# display_array.net
KiCad netlist of a schematic drawn in EAGLE
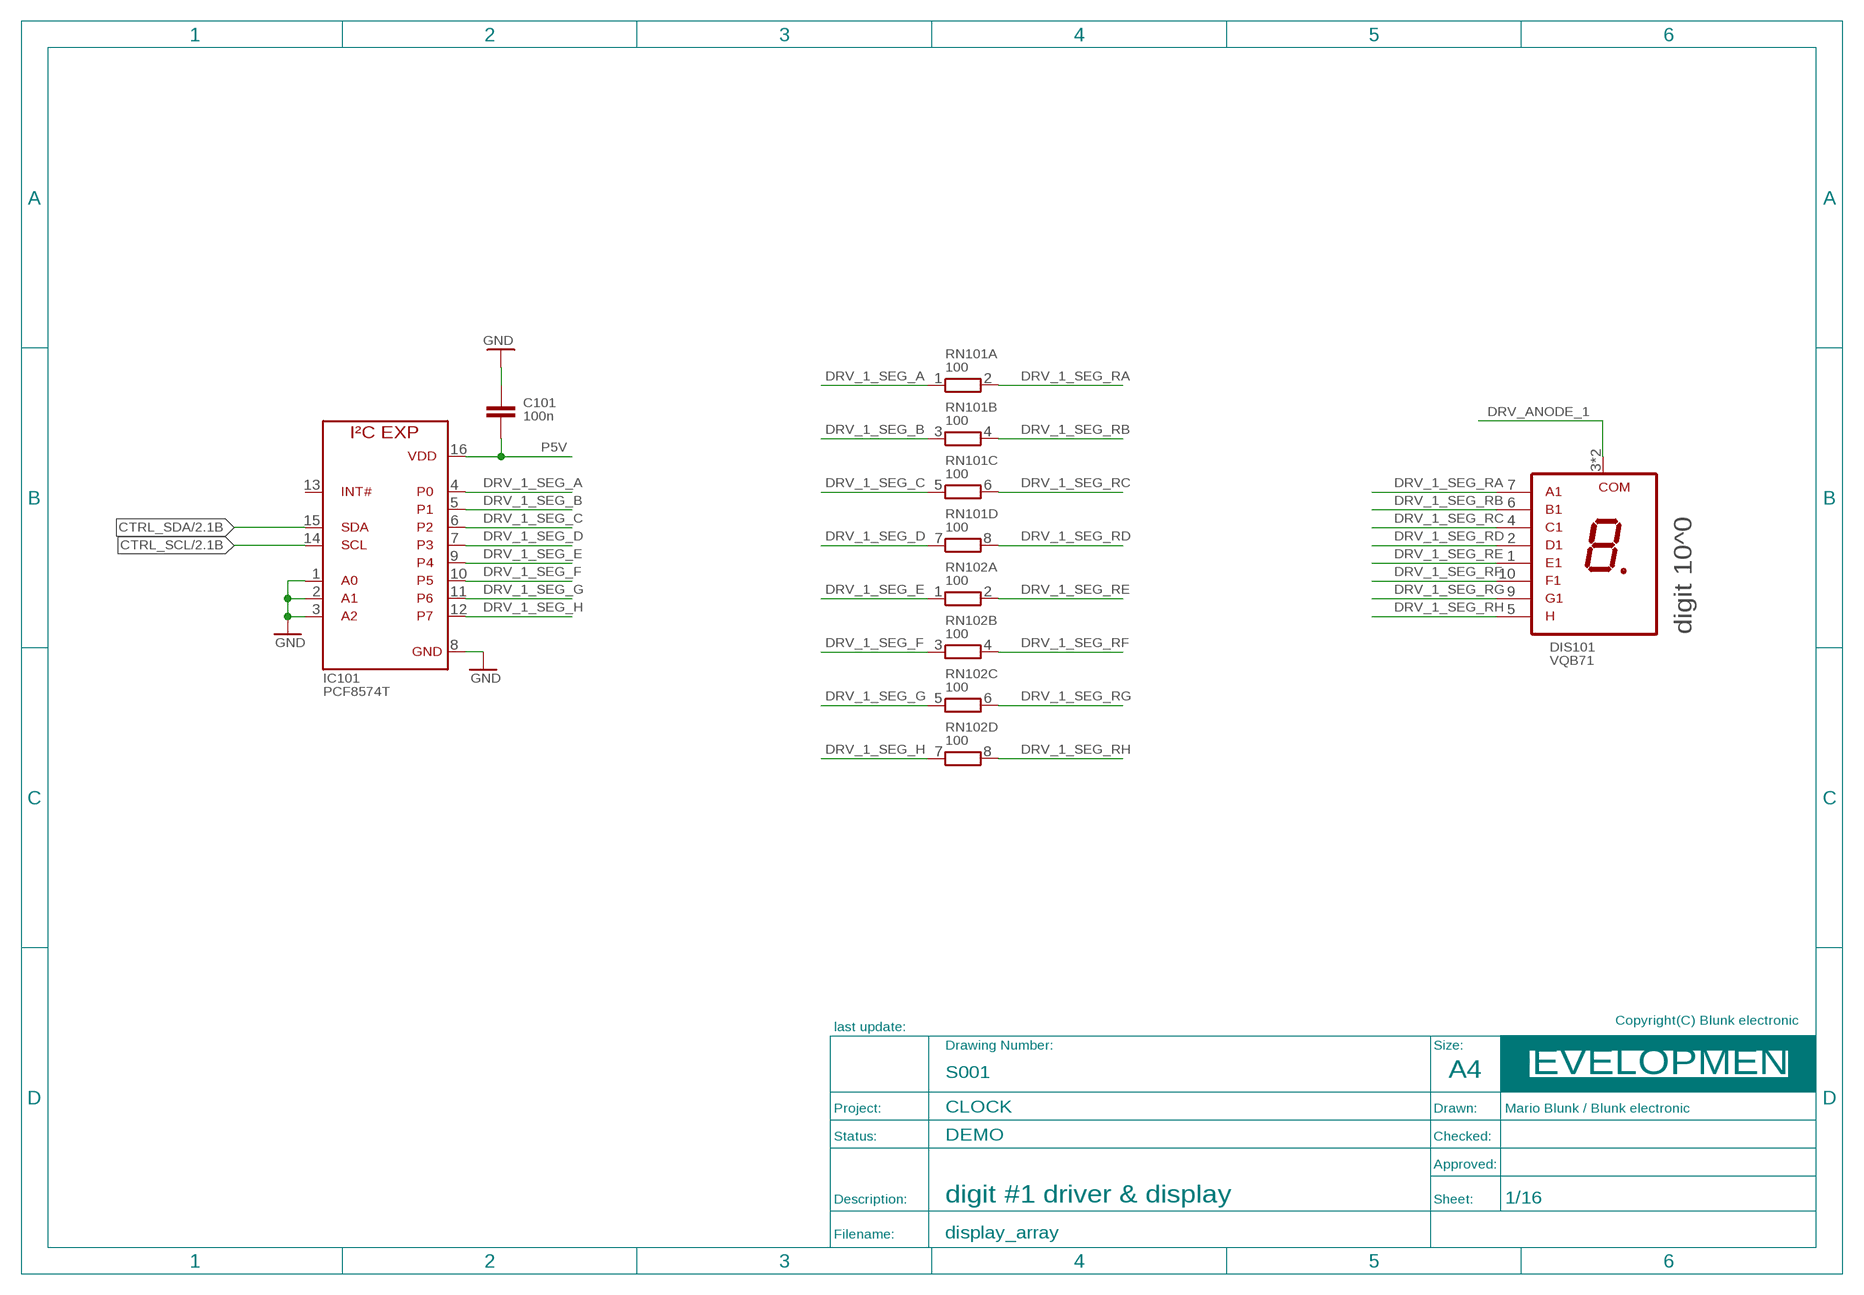
[diagram p0: schematic, sheet 1]
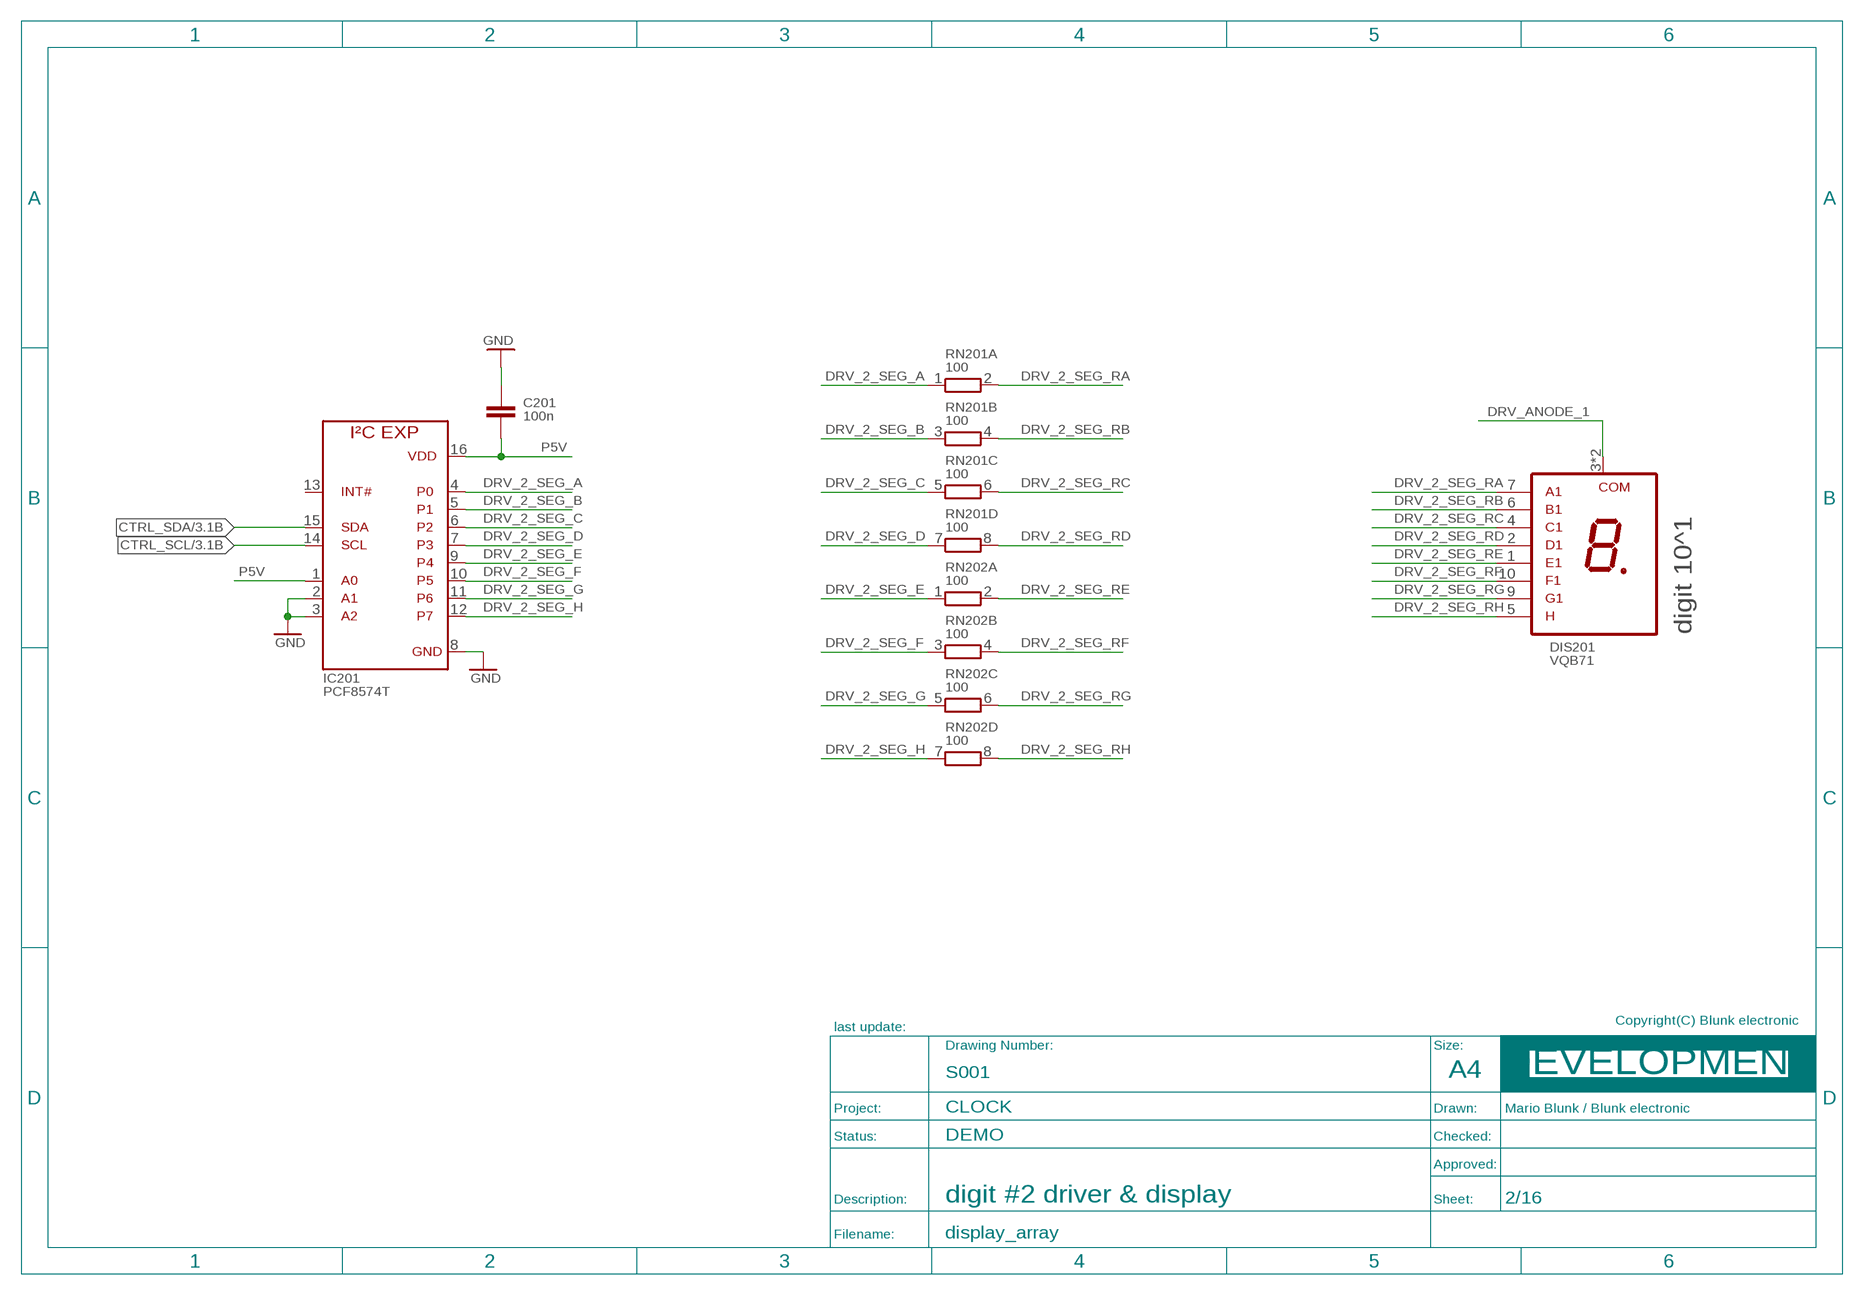
[diagram p1: schematic, sheet 2]
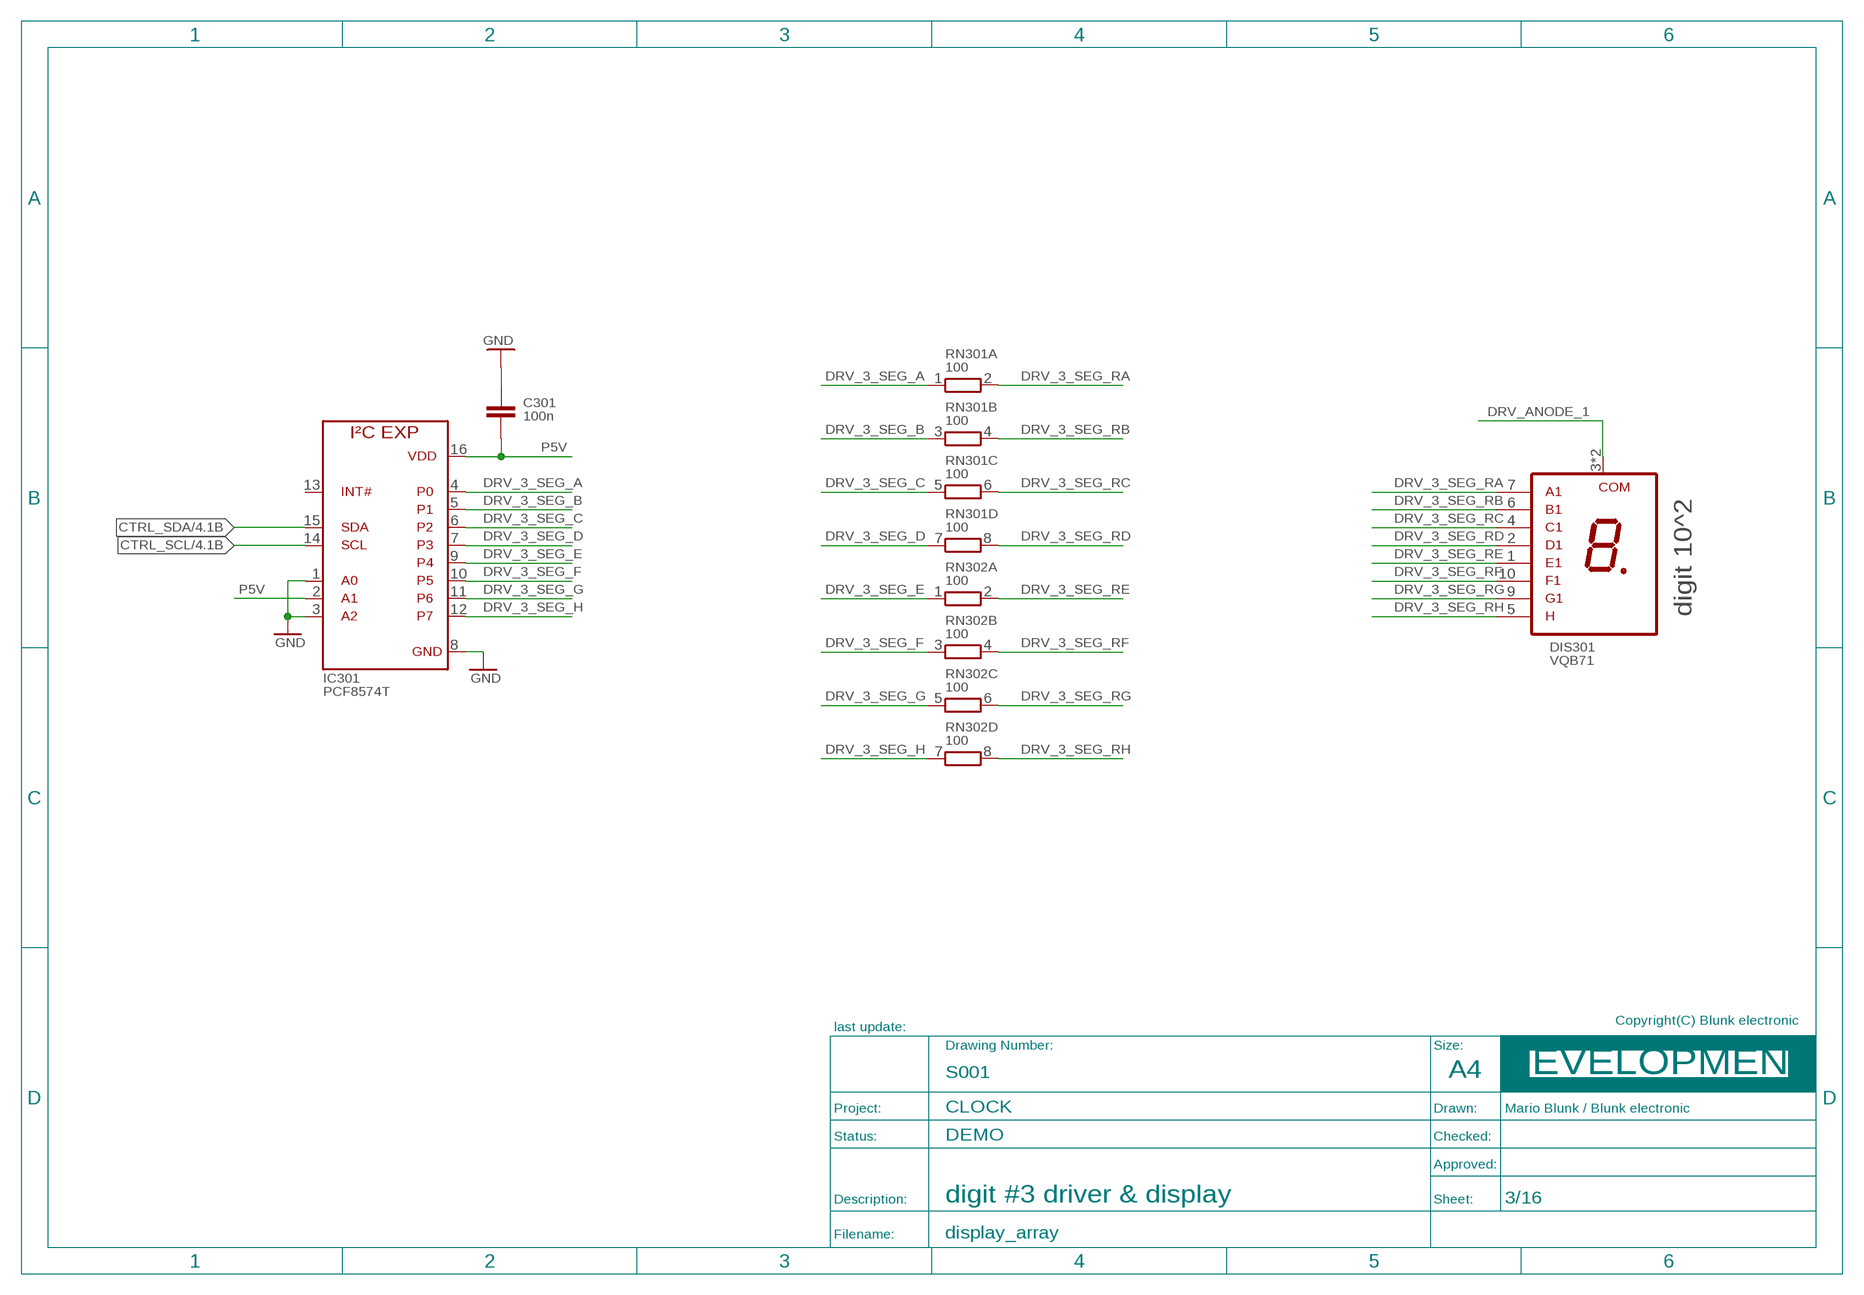
[diagram p2: schematic, sheet 3]
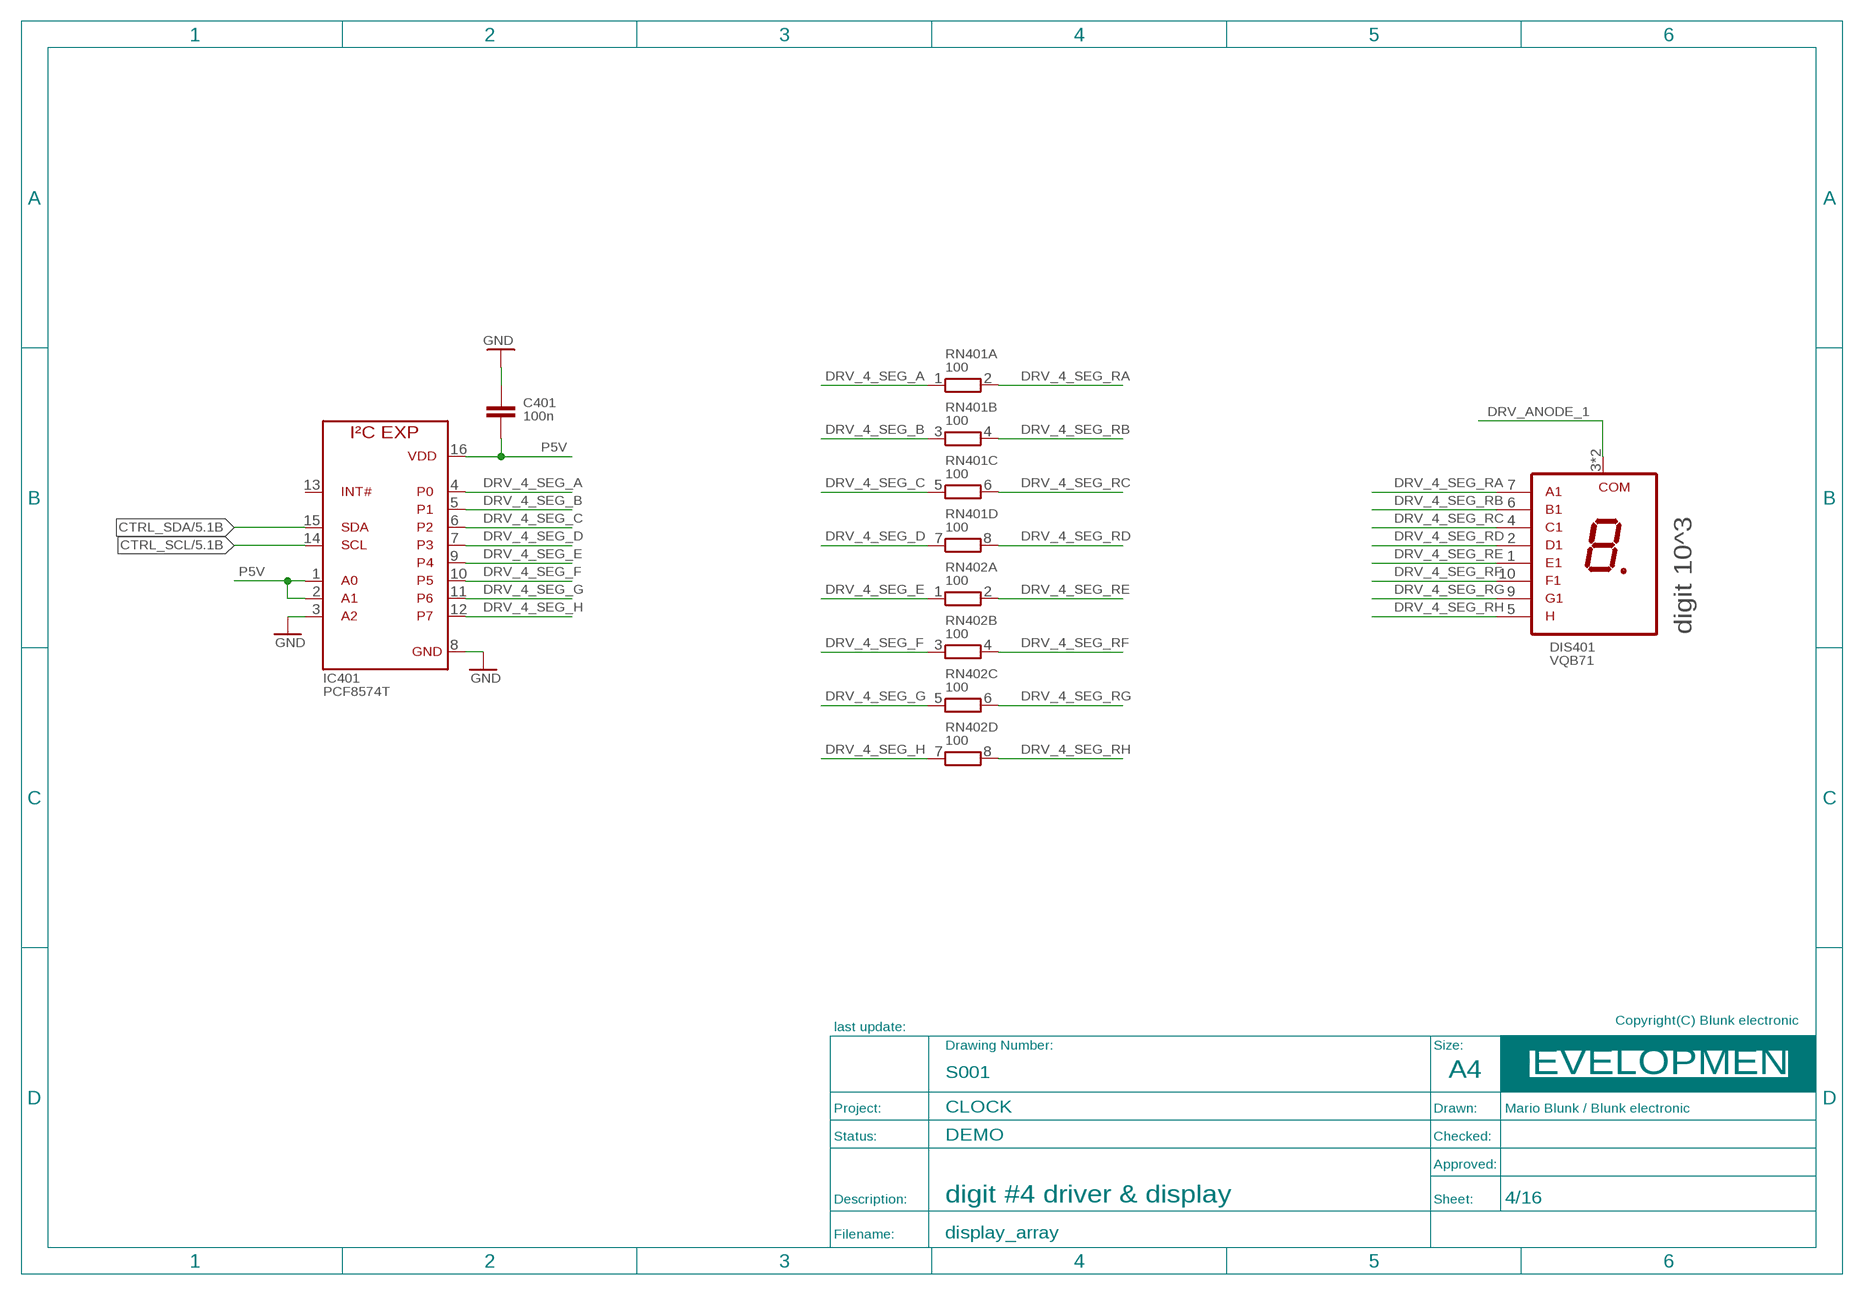
[diagram p3: schematic, sheet 4]
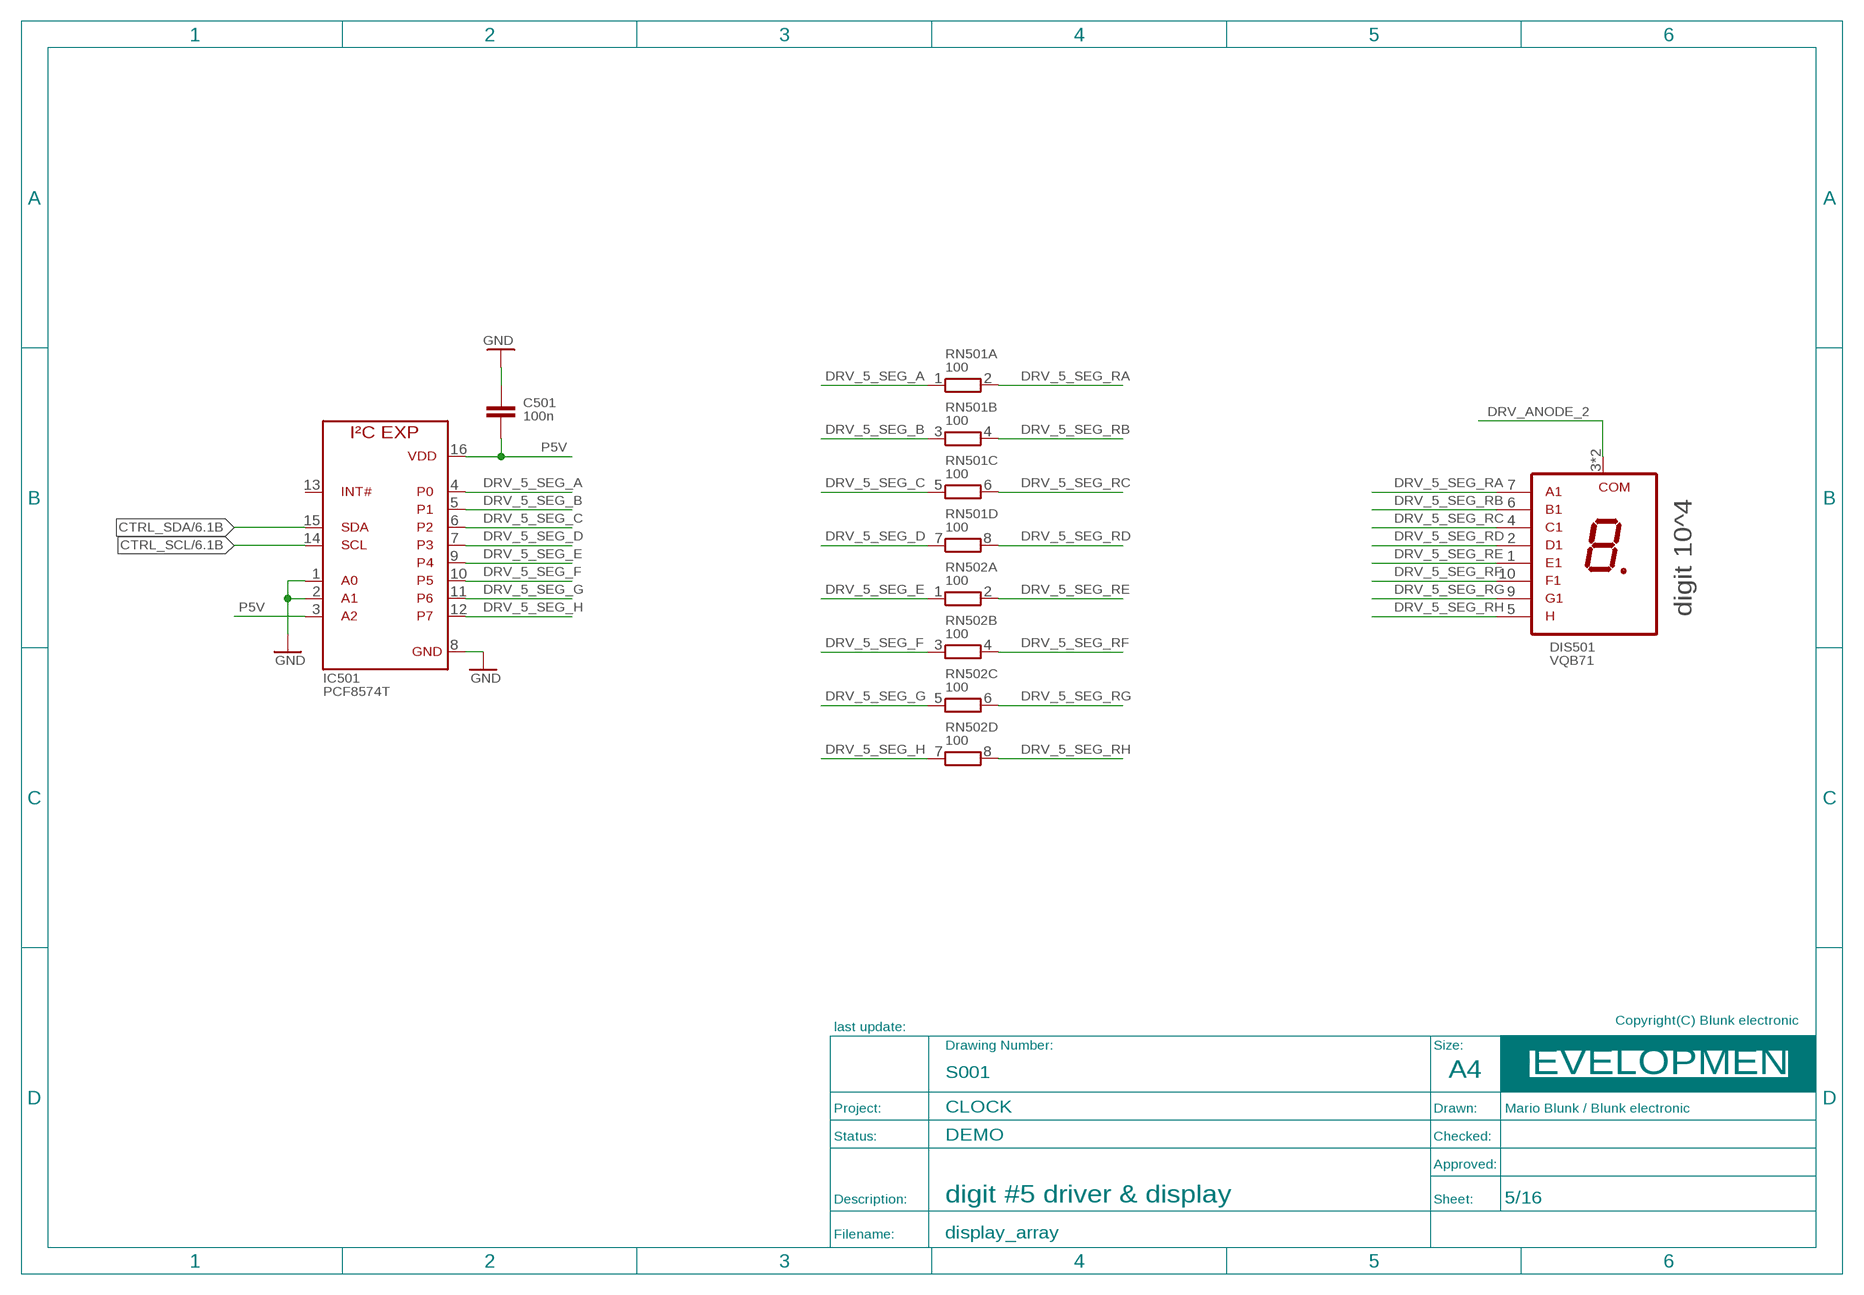
[diagram p4: schematic, sheet 5]
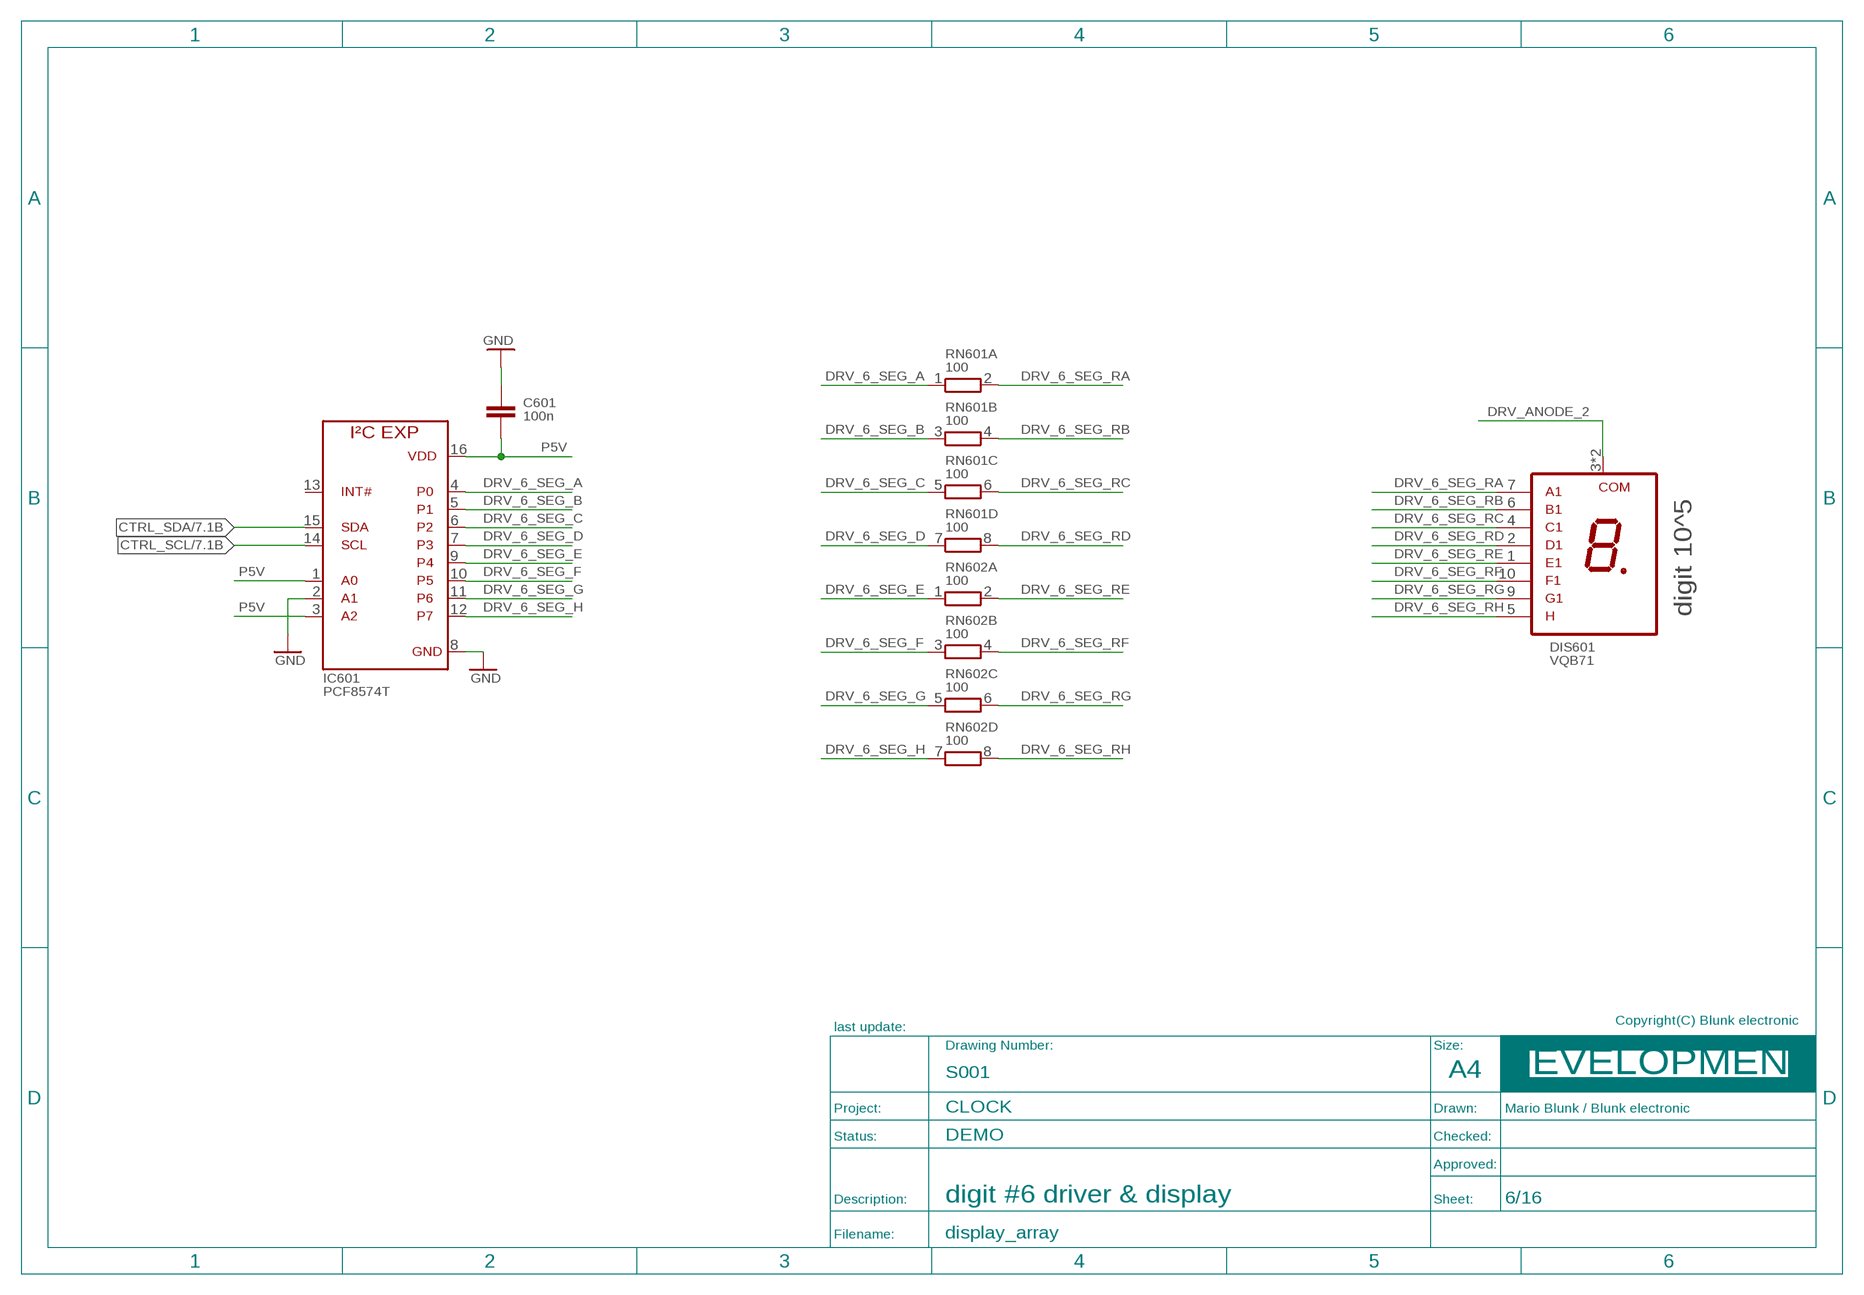
[diagram p5: schematic, sheet 6]
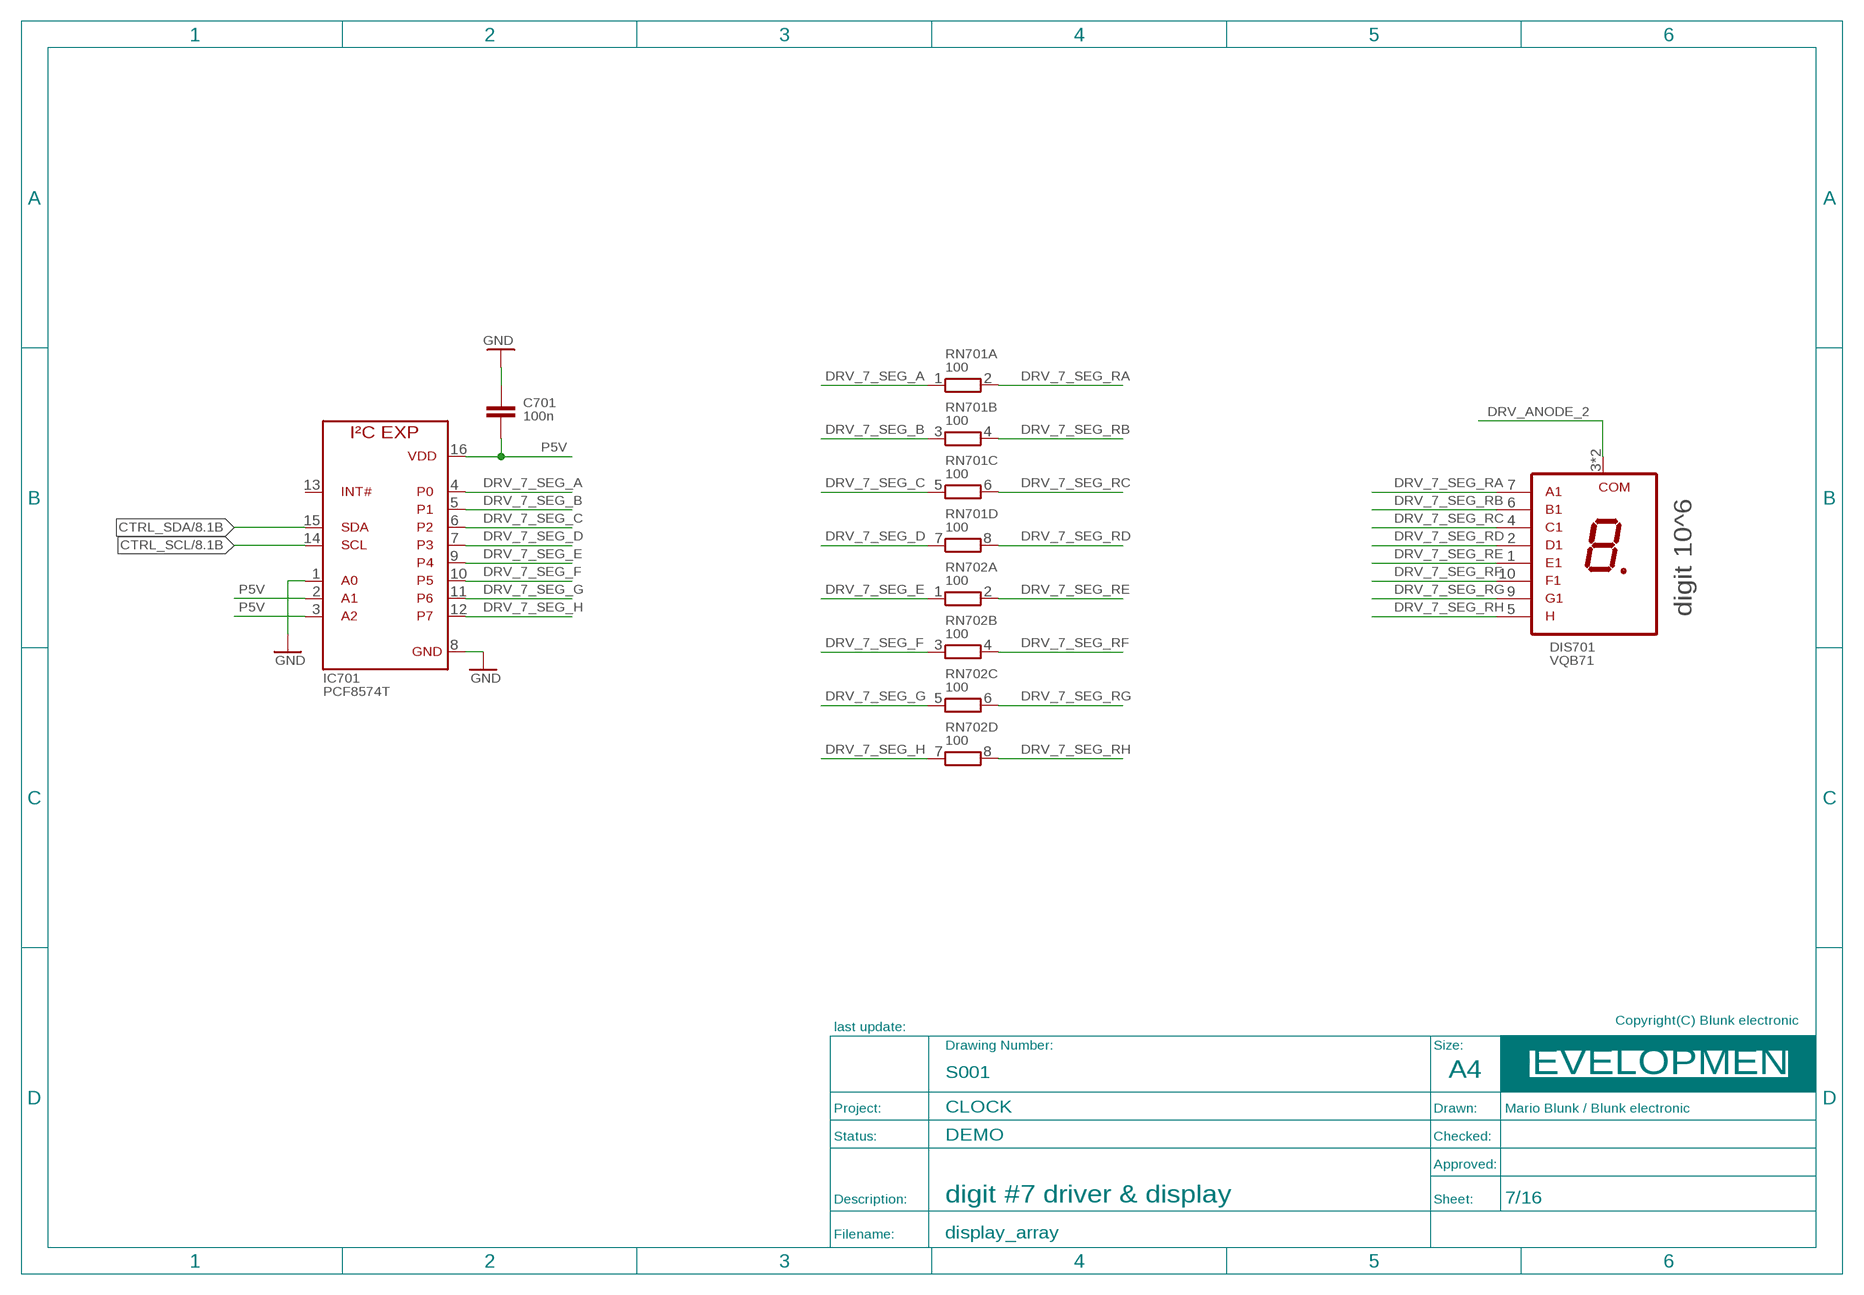
[diagram p6: schematic, sheet 7]
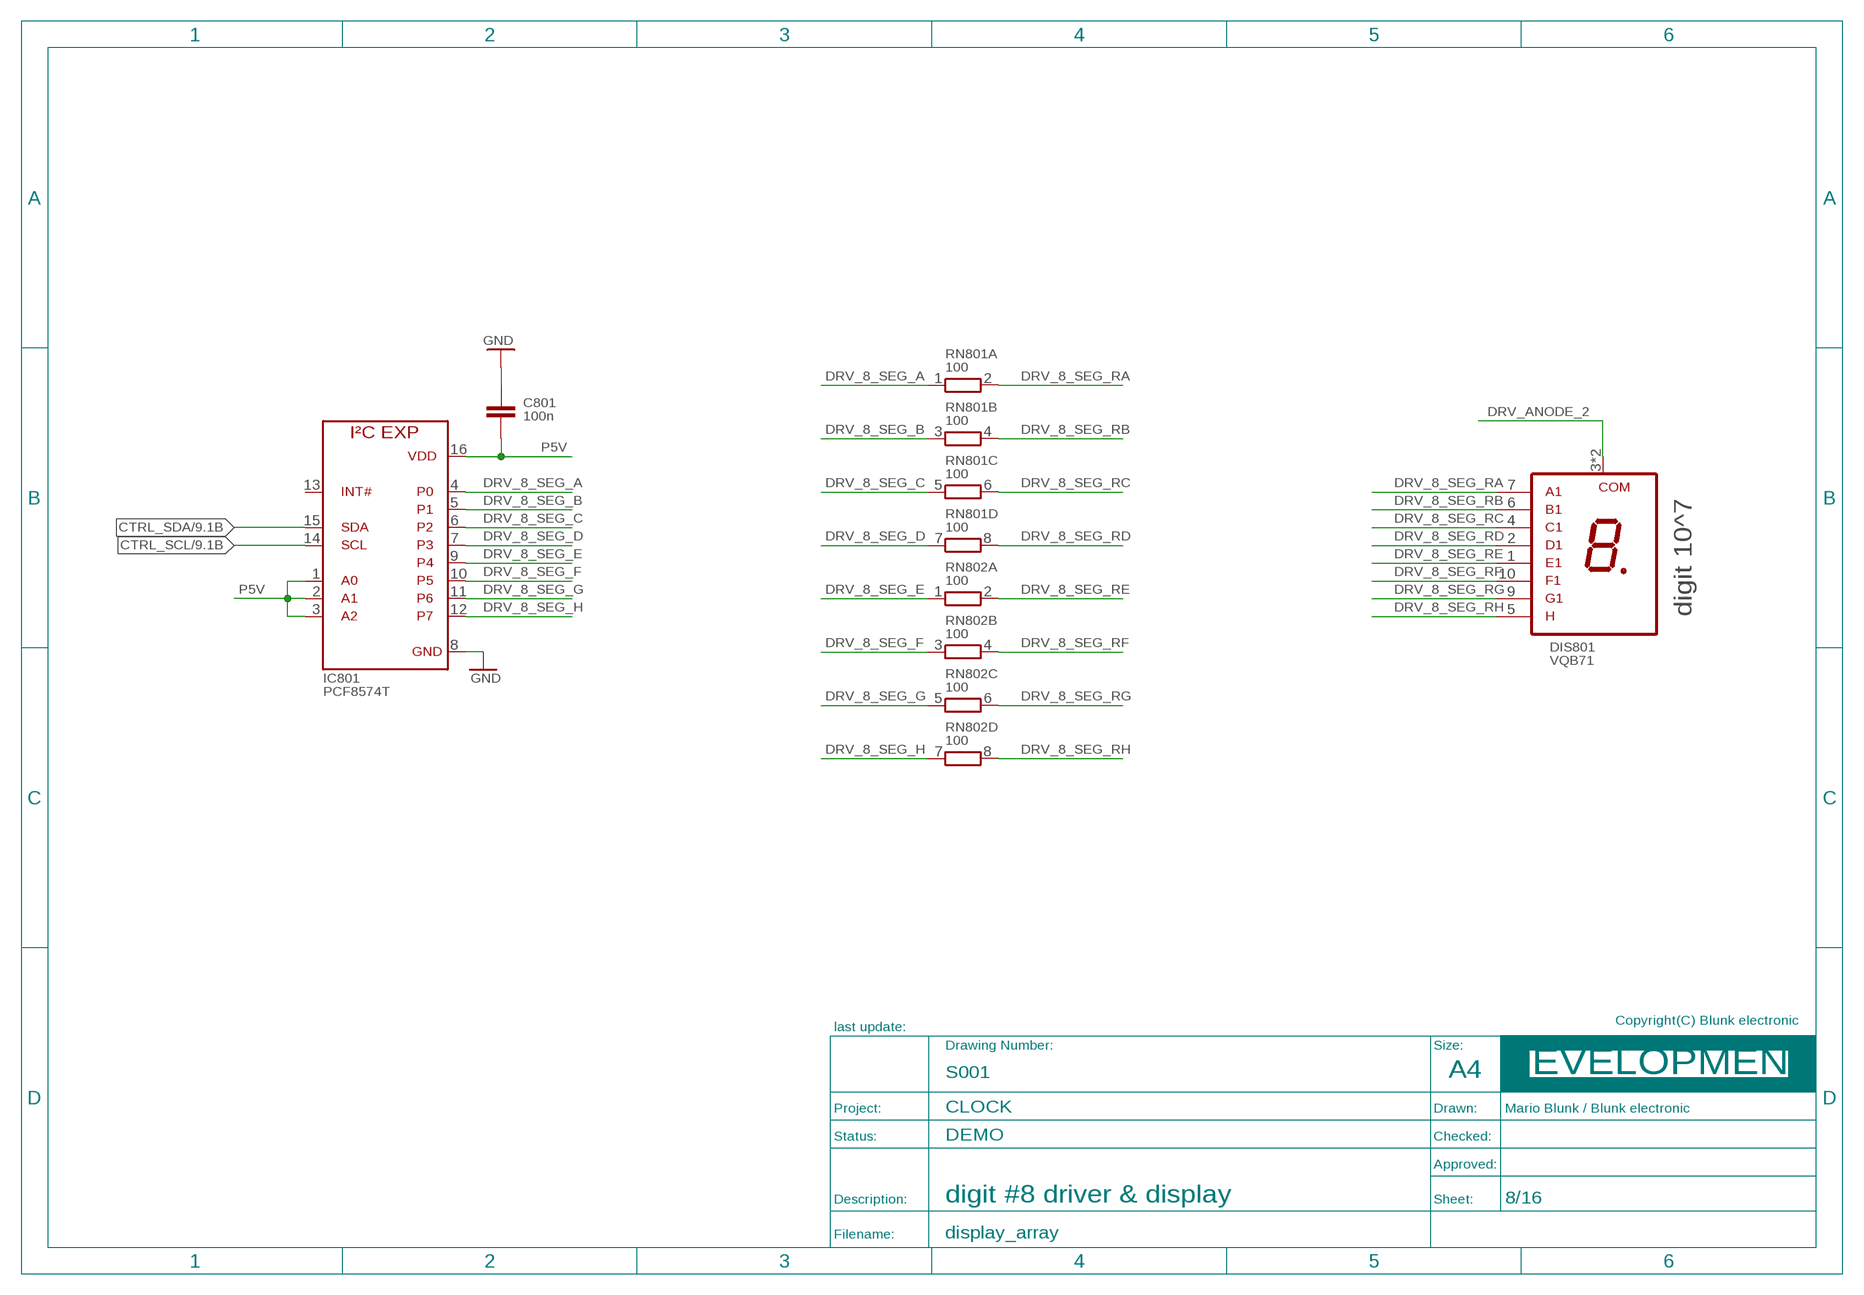
[diagram p7: schematic, sheet 8]
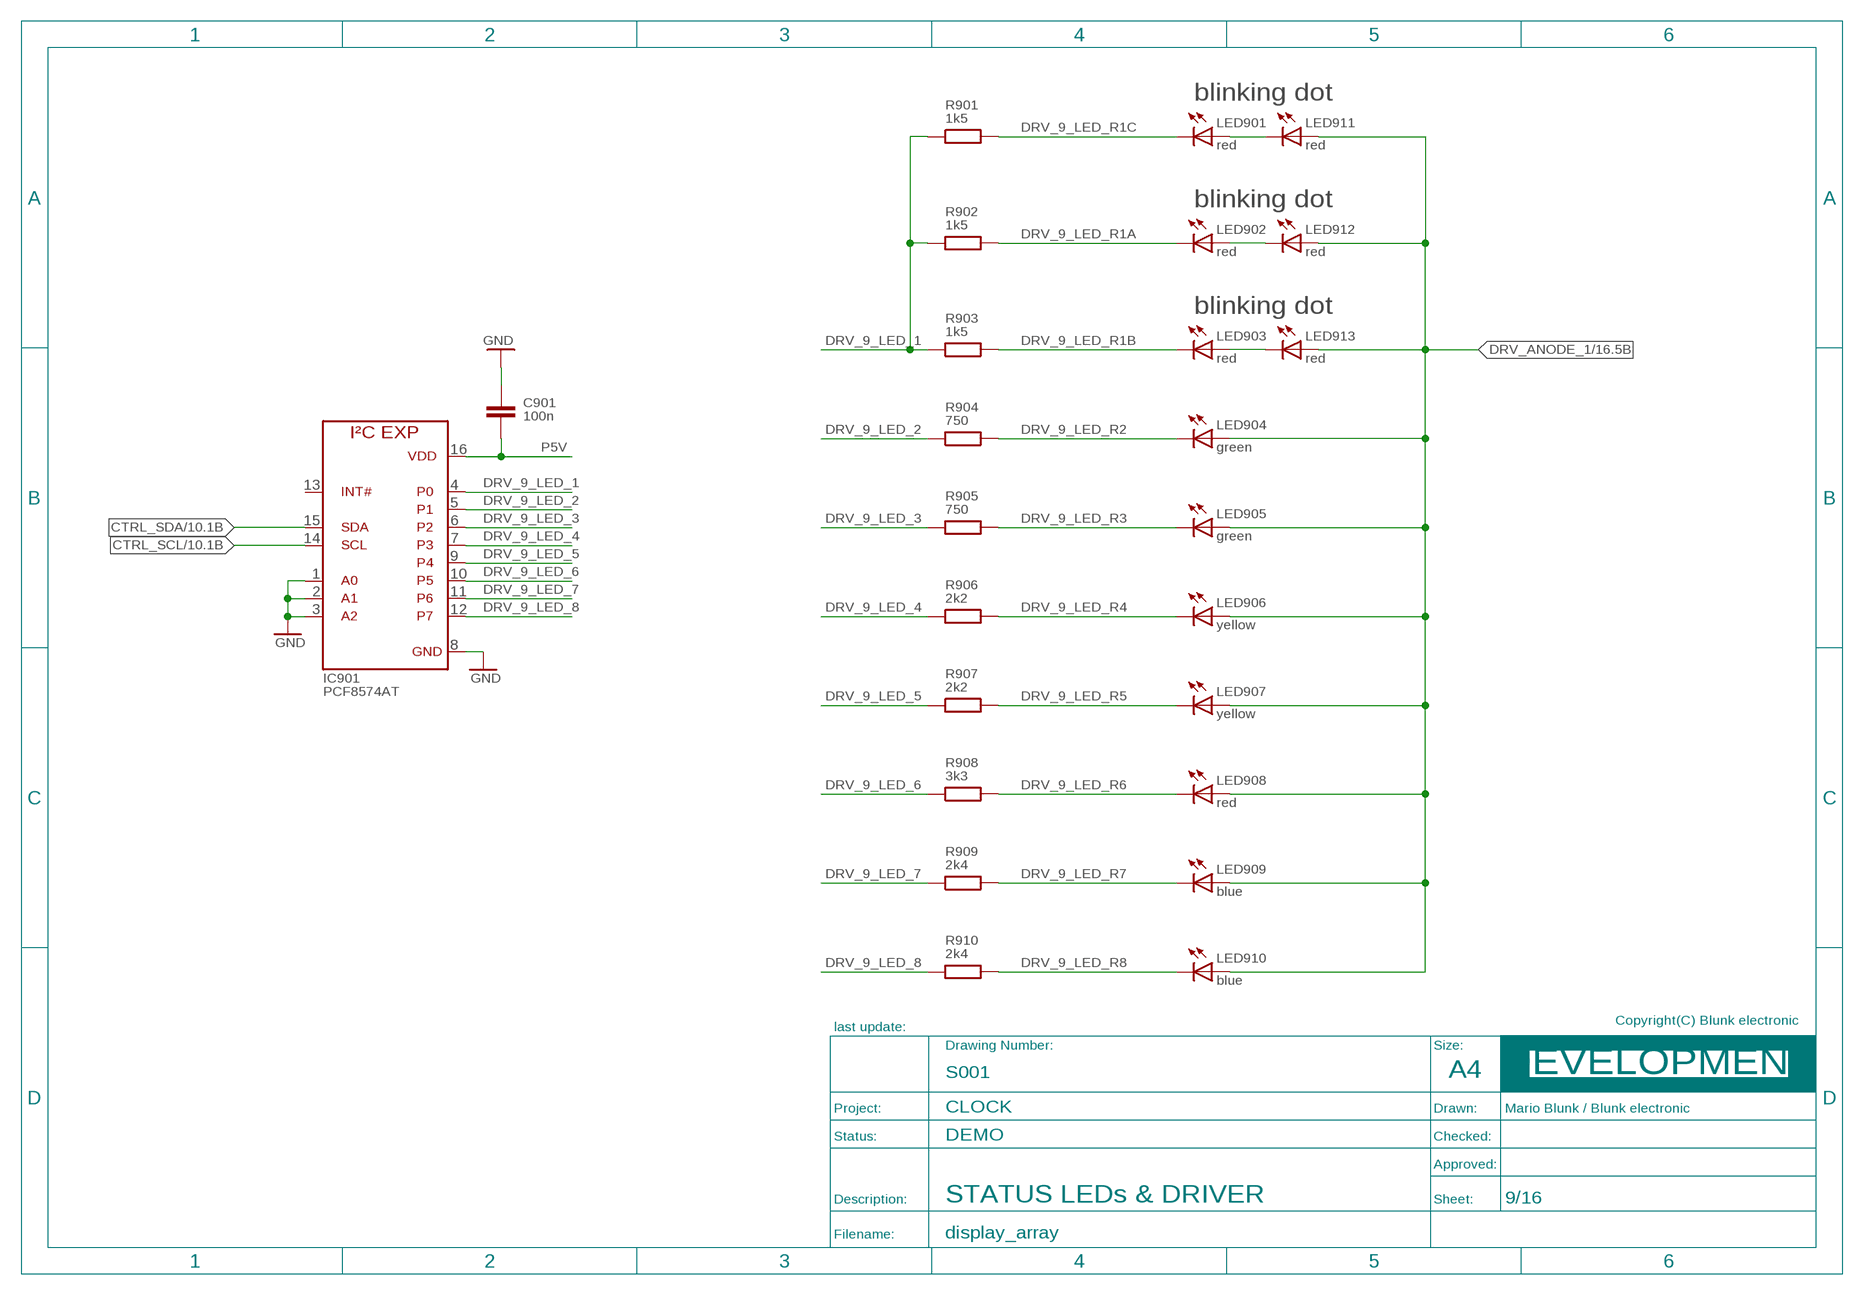
[diagram p8: schematic, sheet 9]
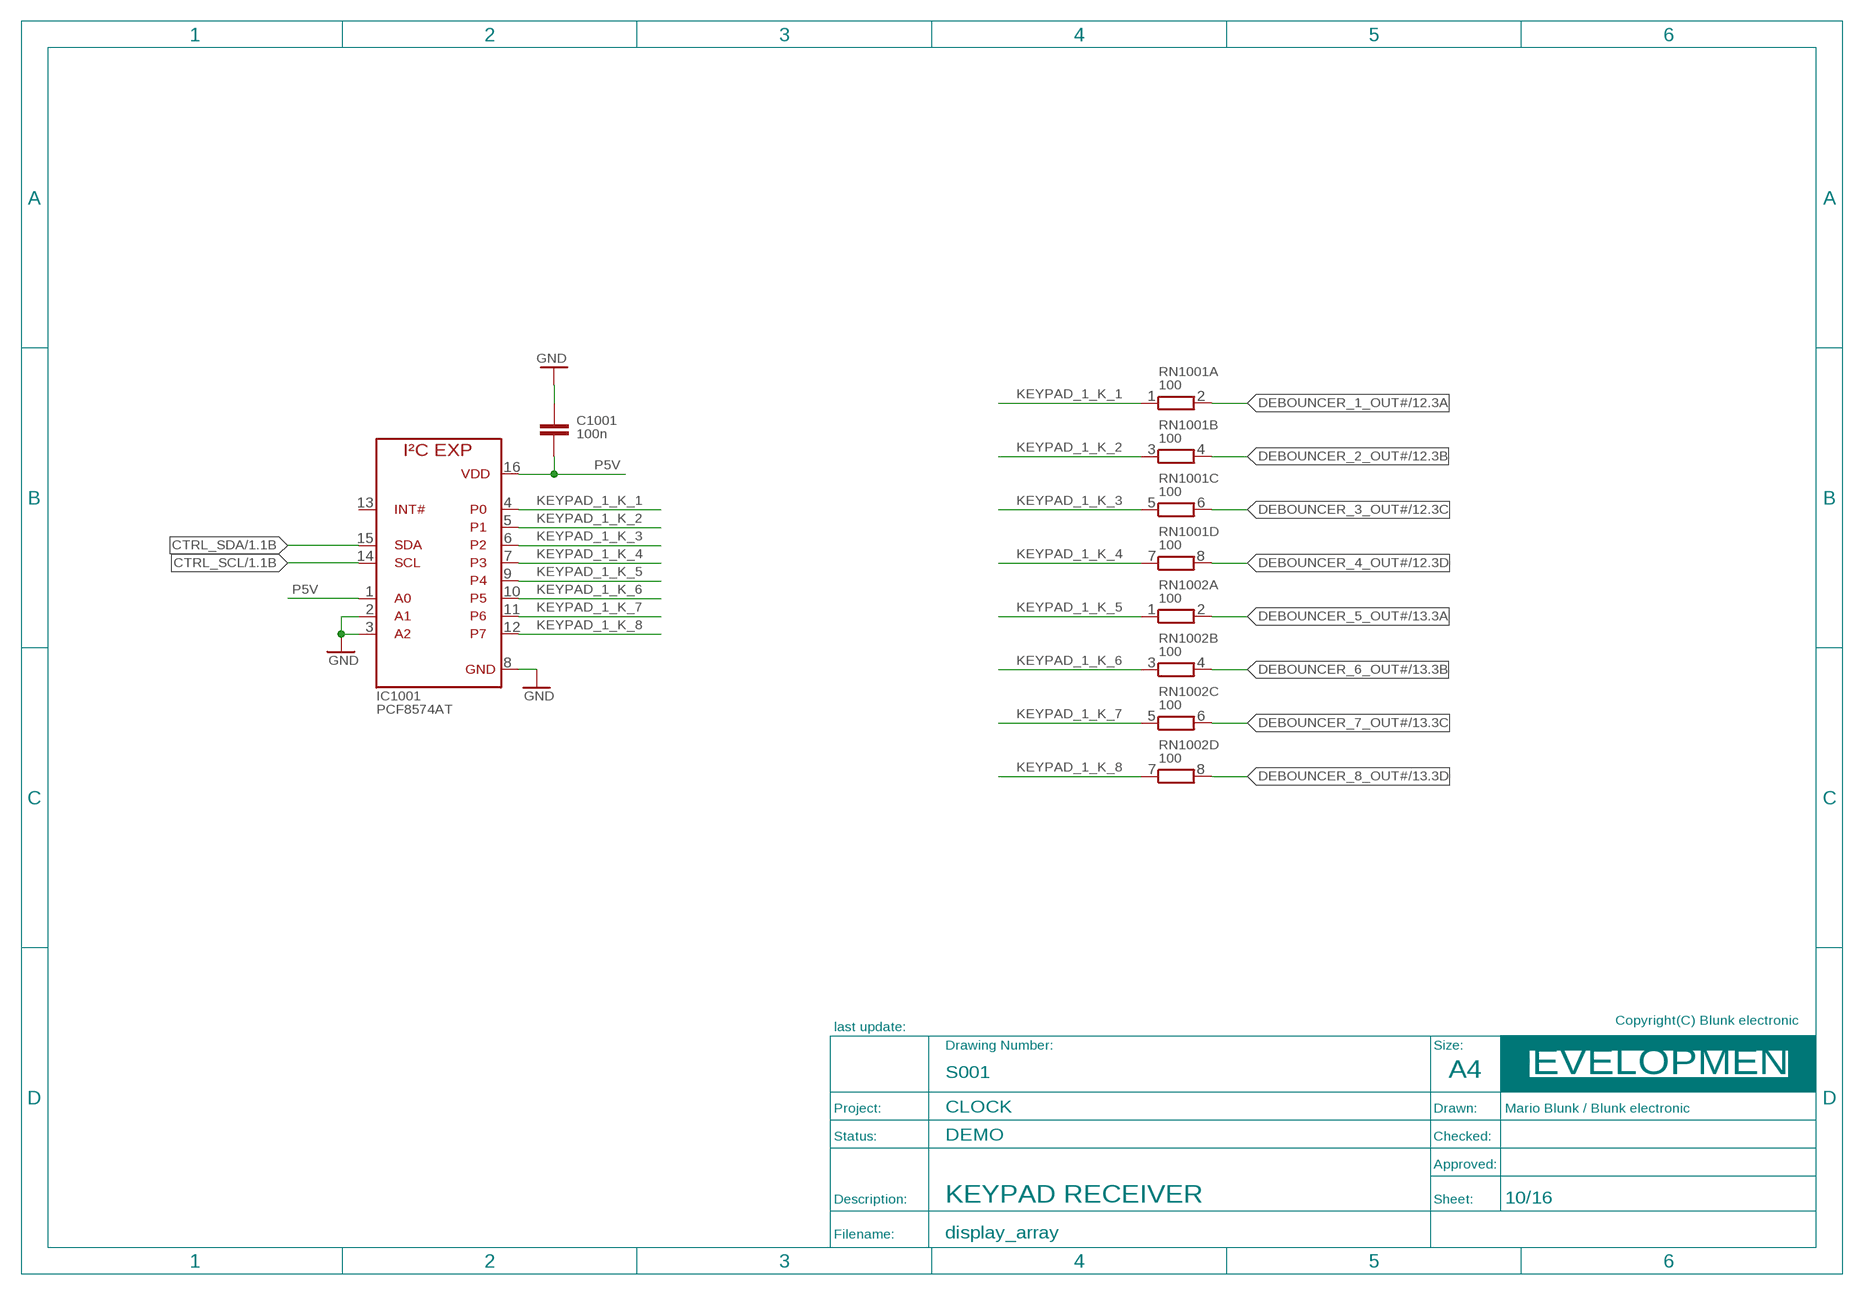
[diagram p9: schematic, sheet 10]
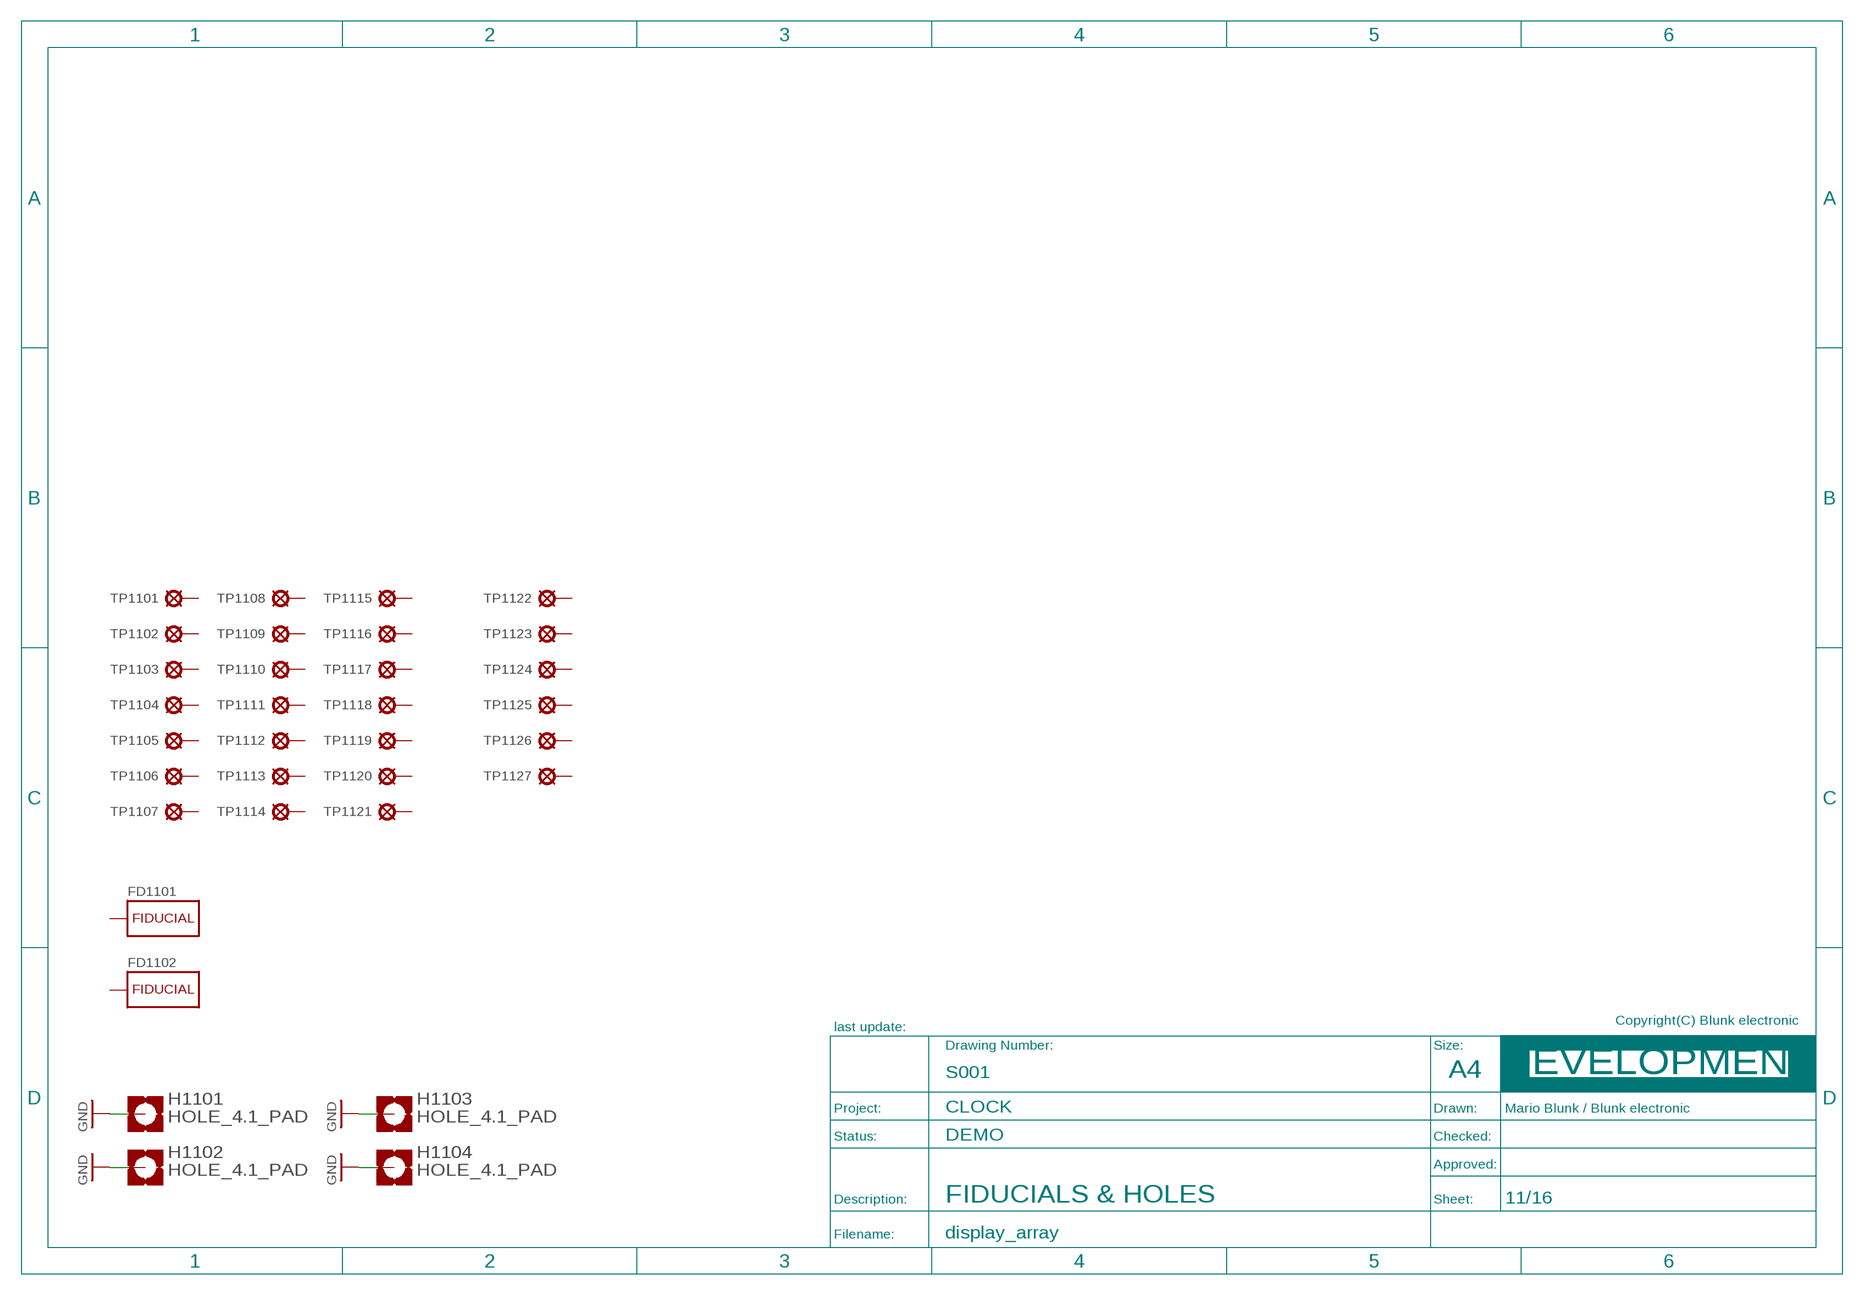
[diagram p10: schematic, sheet 11]
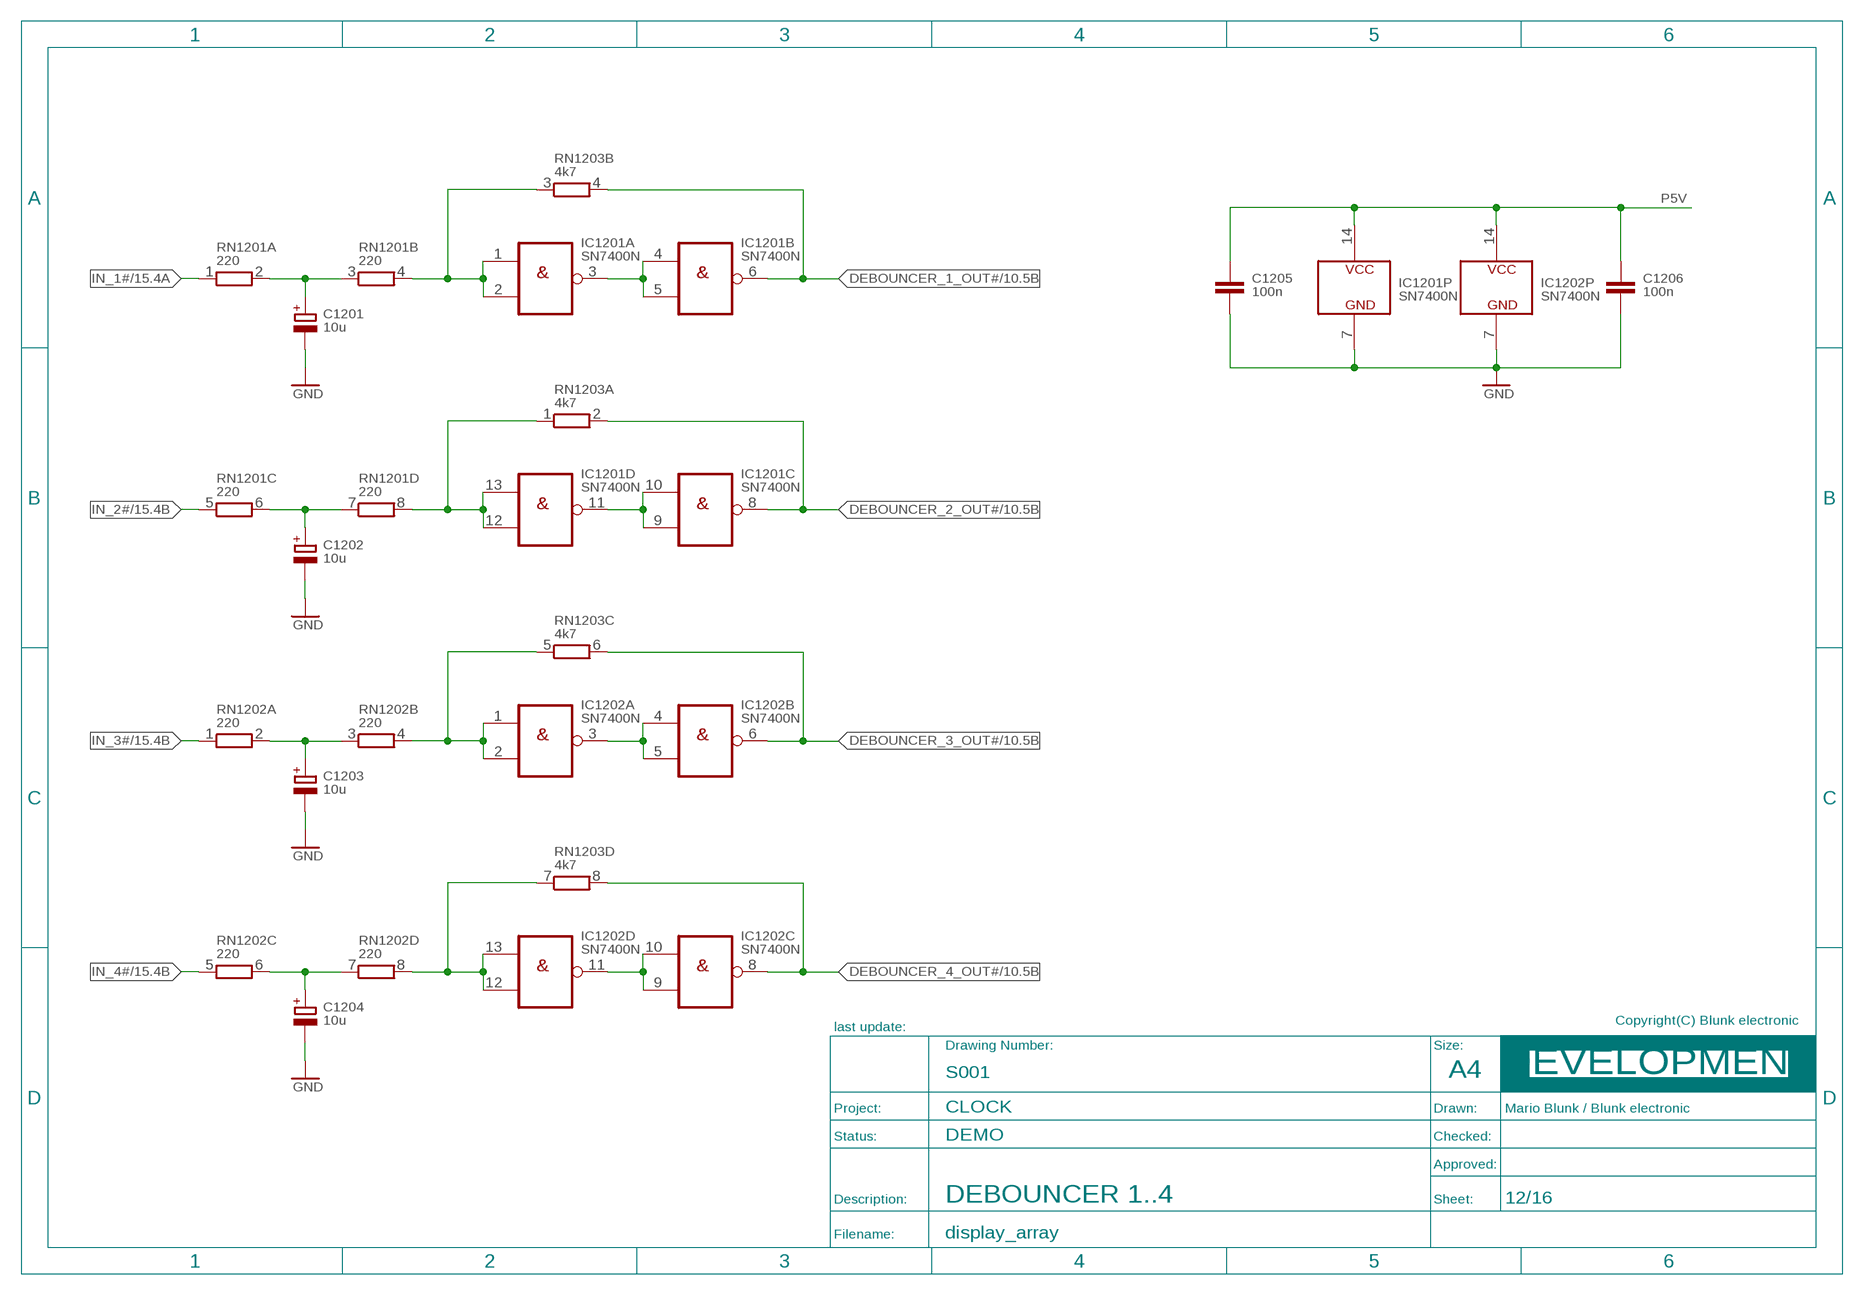
[diagram p11: schematic, sheet 12]
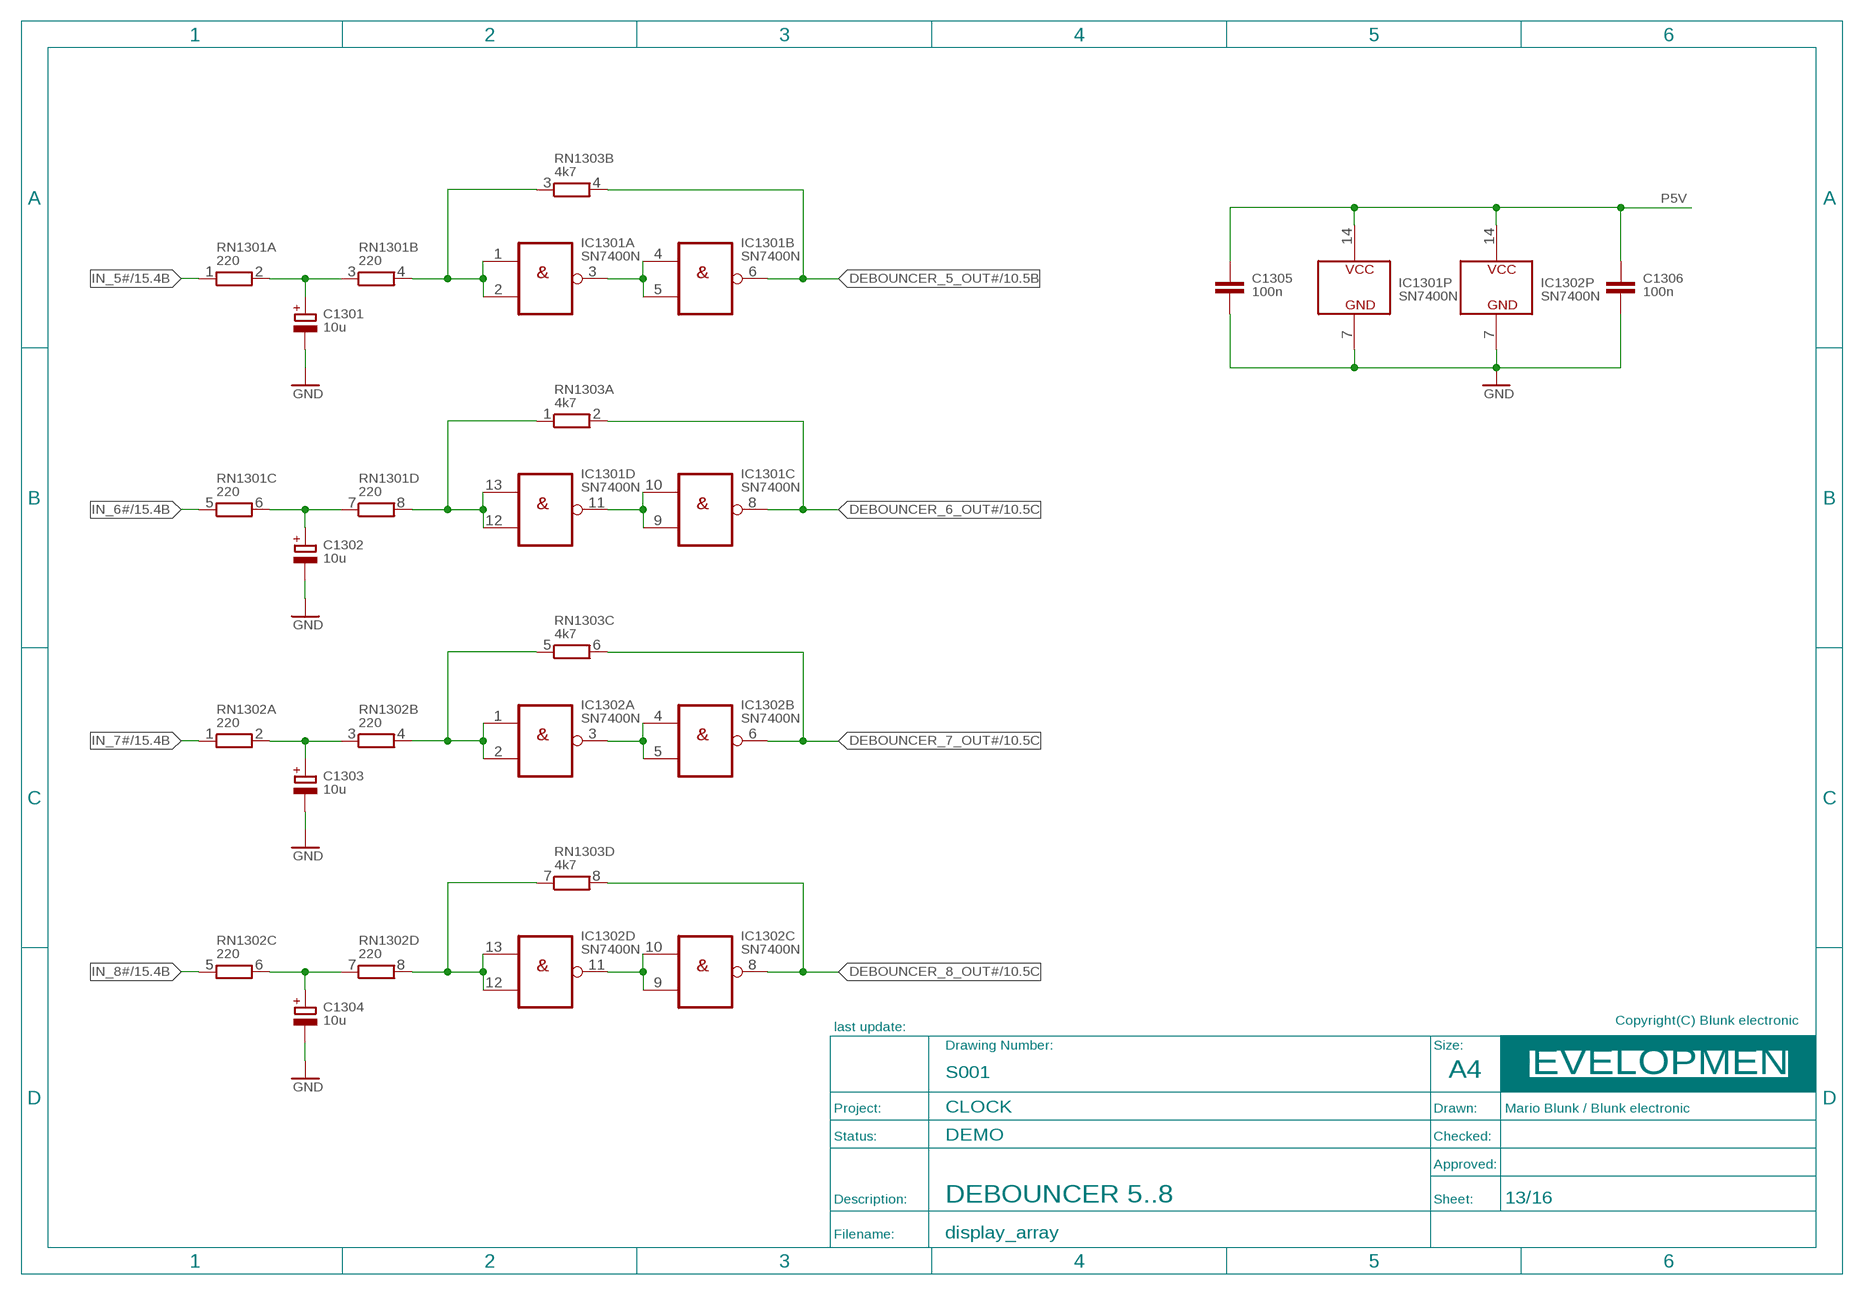
[diagram p12: schematic, sheet 13]
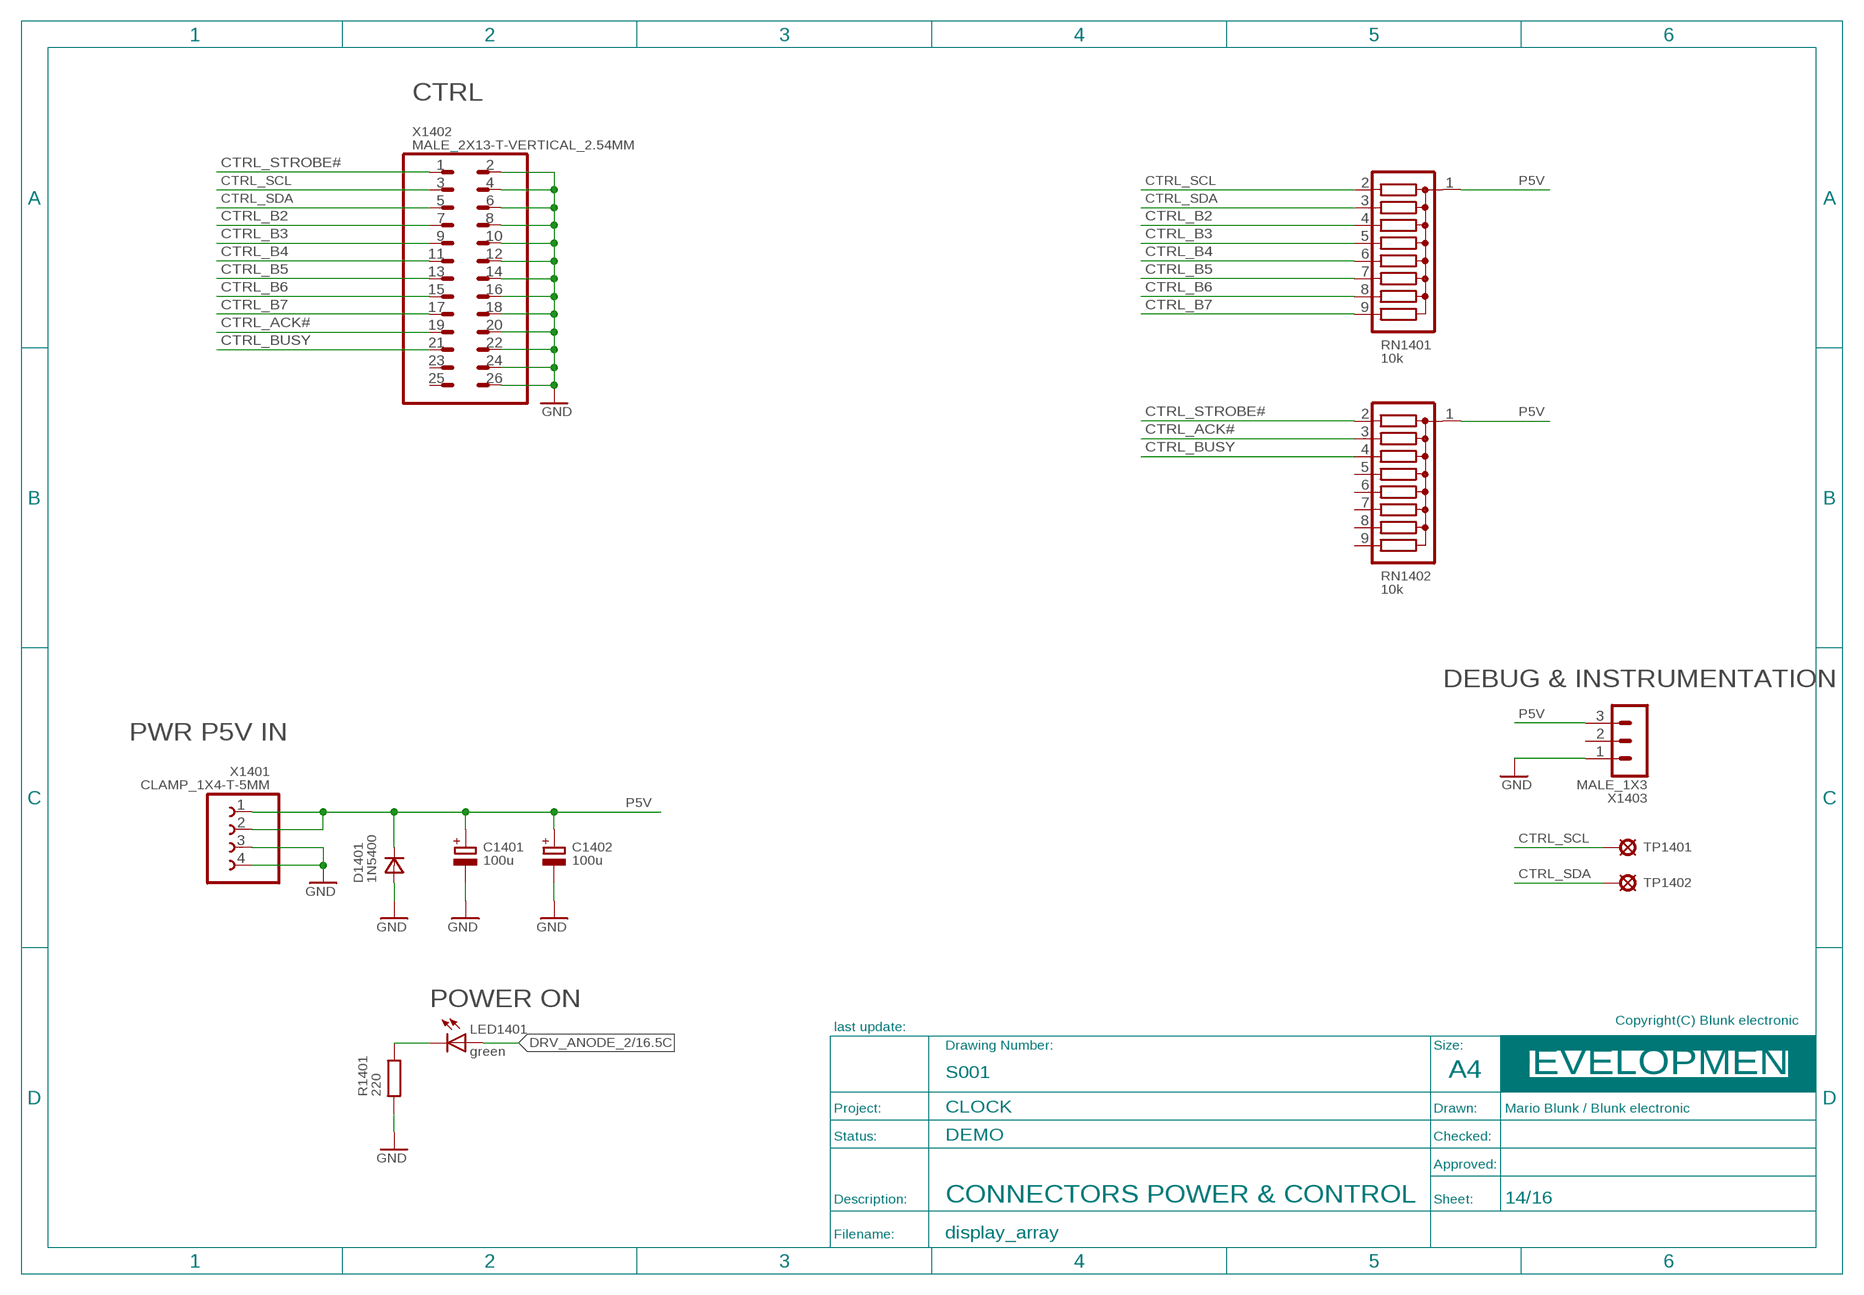
[diagram p13: schematic, sheet 14]
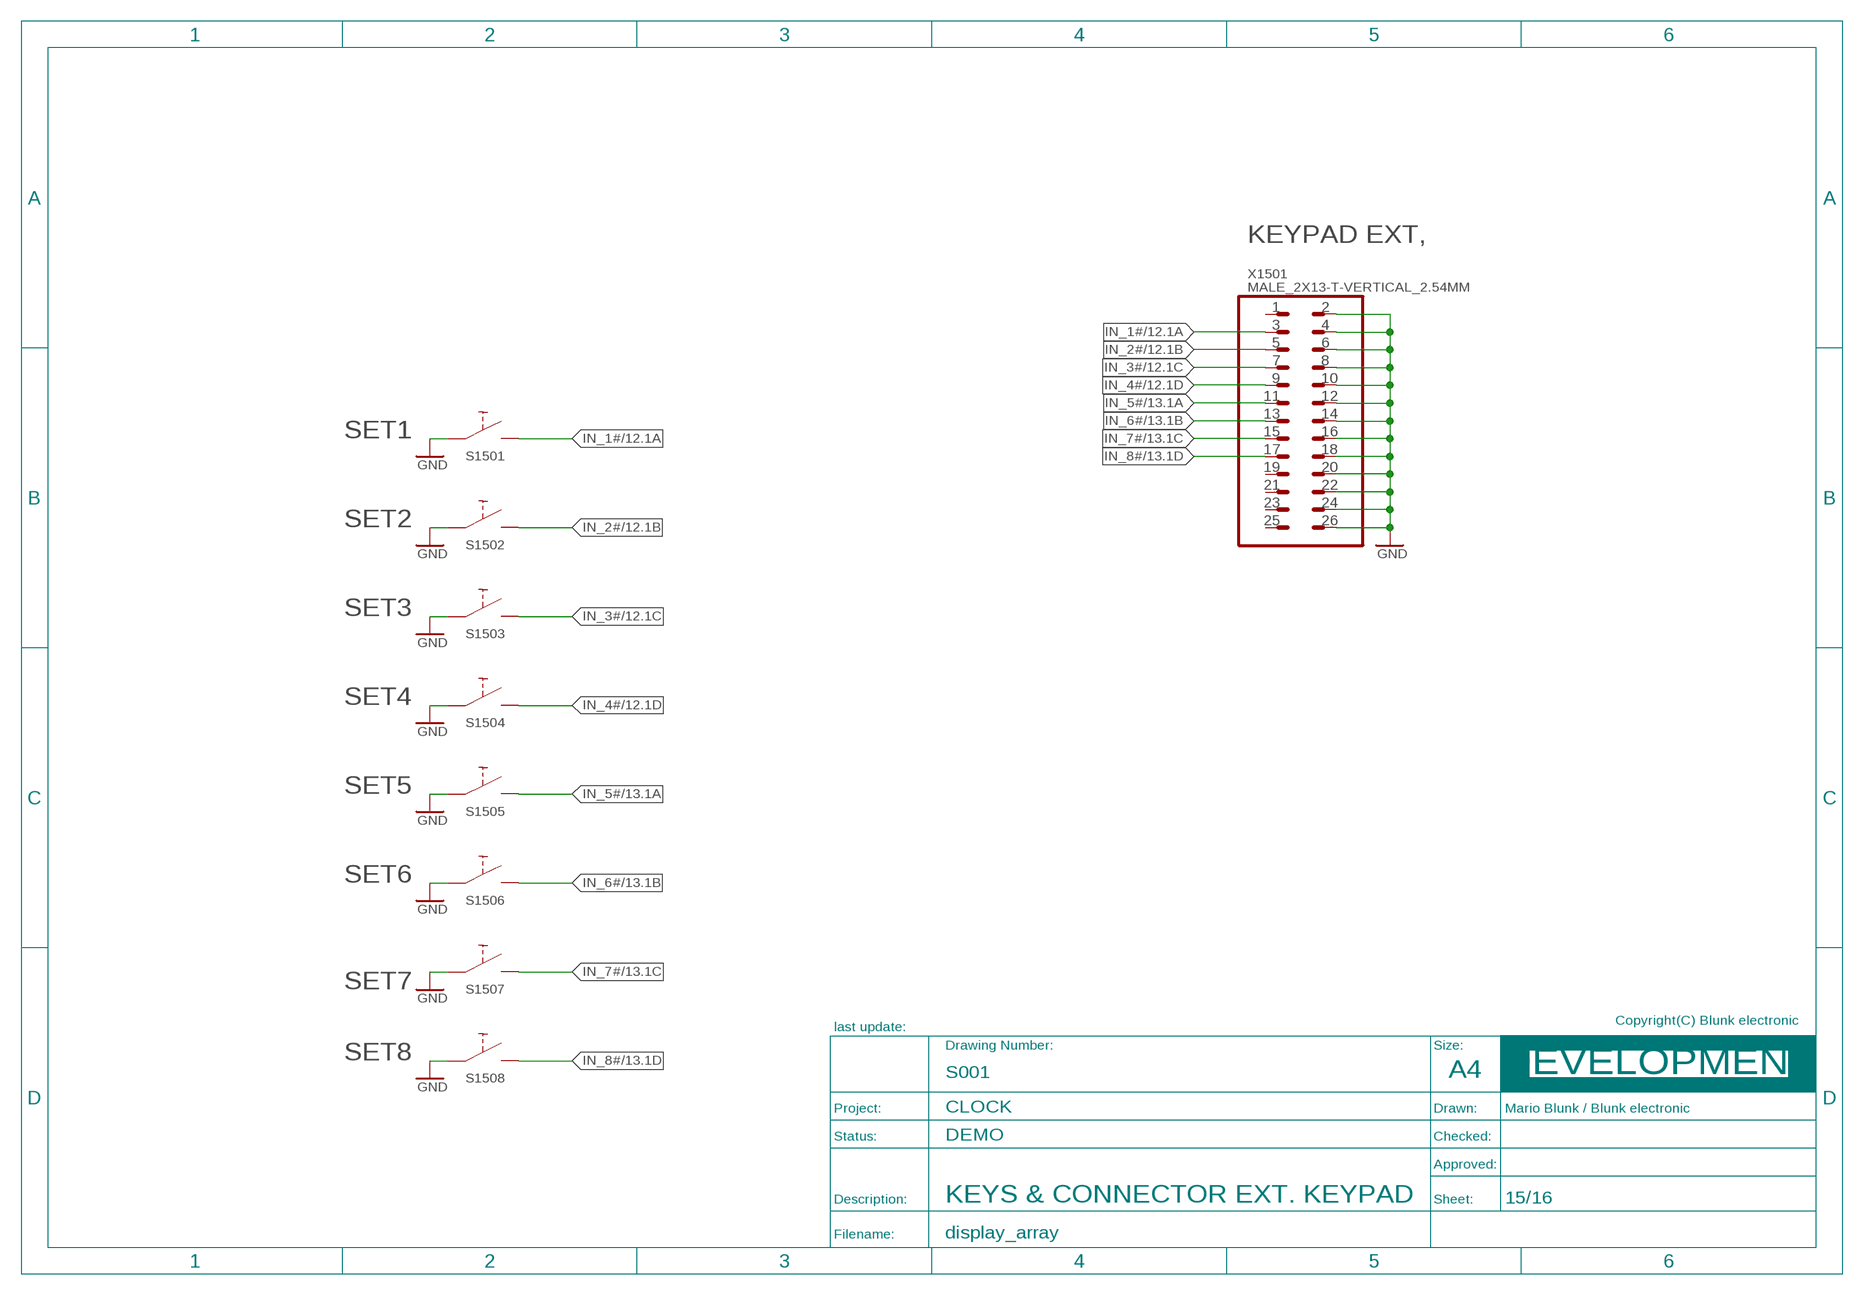
[diagram p14: schematic, sheet 15]
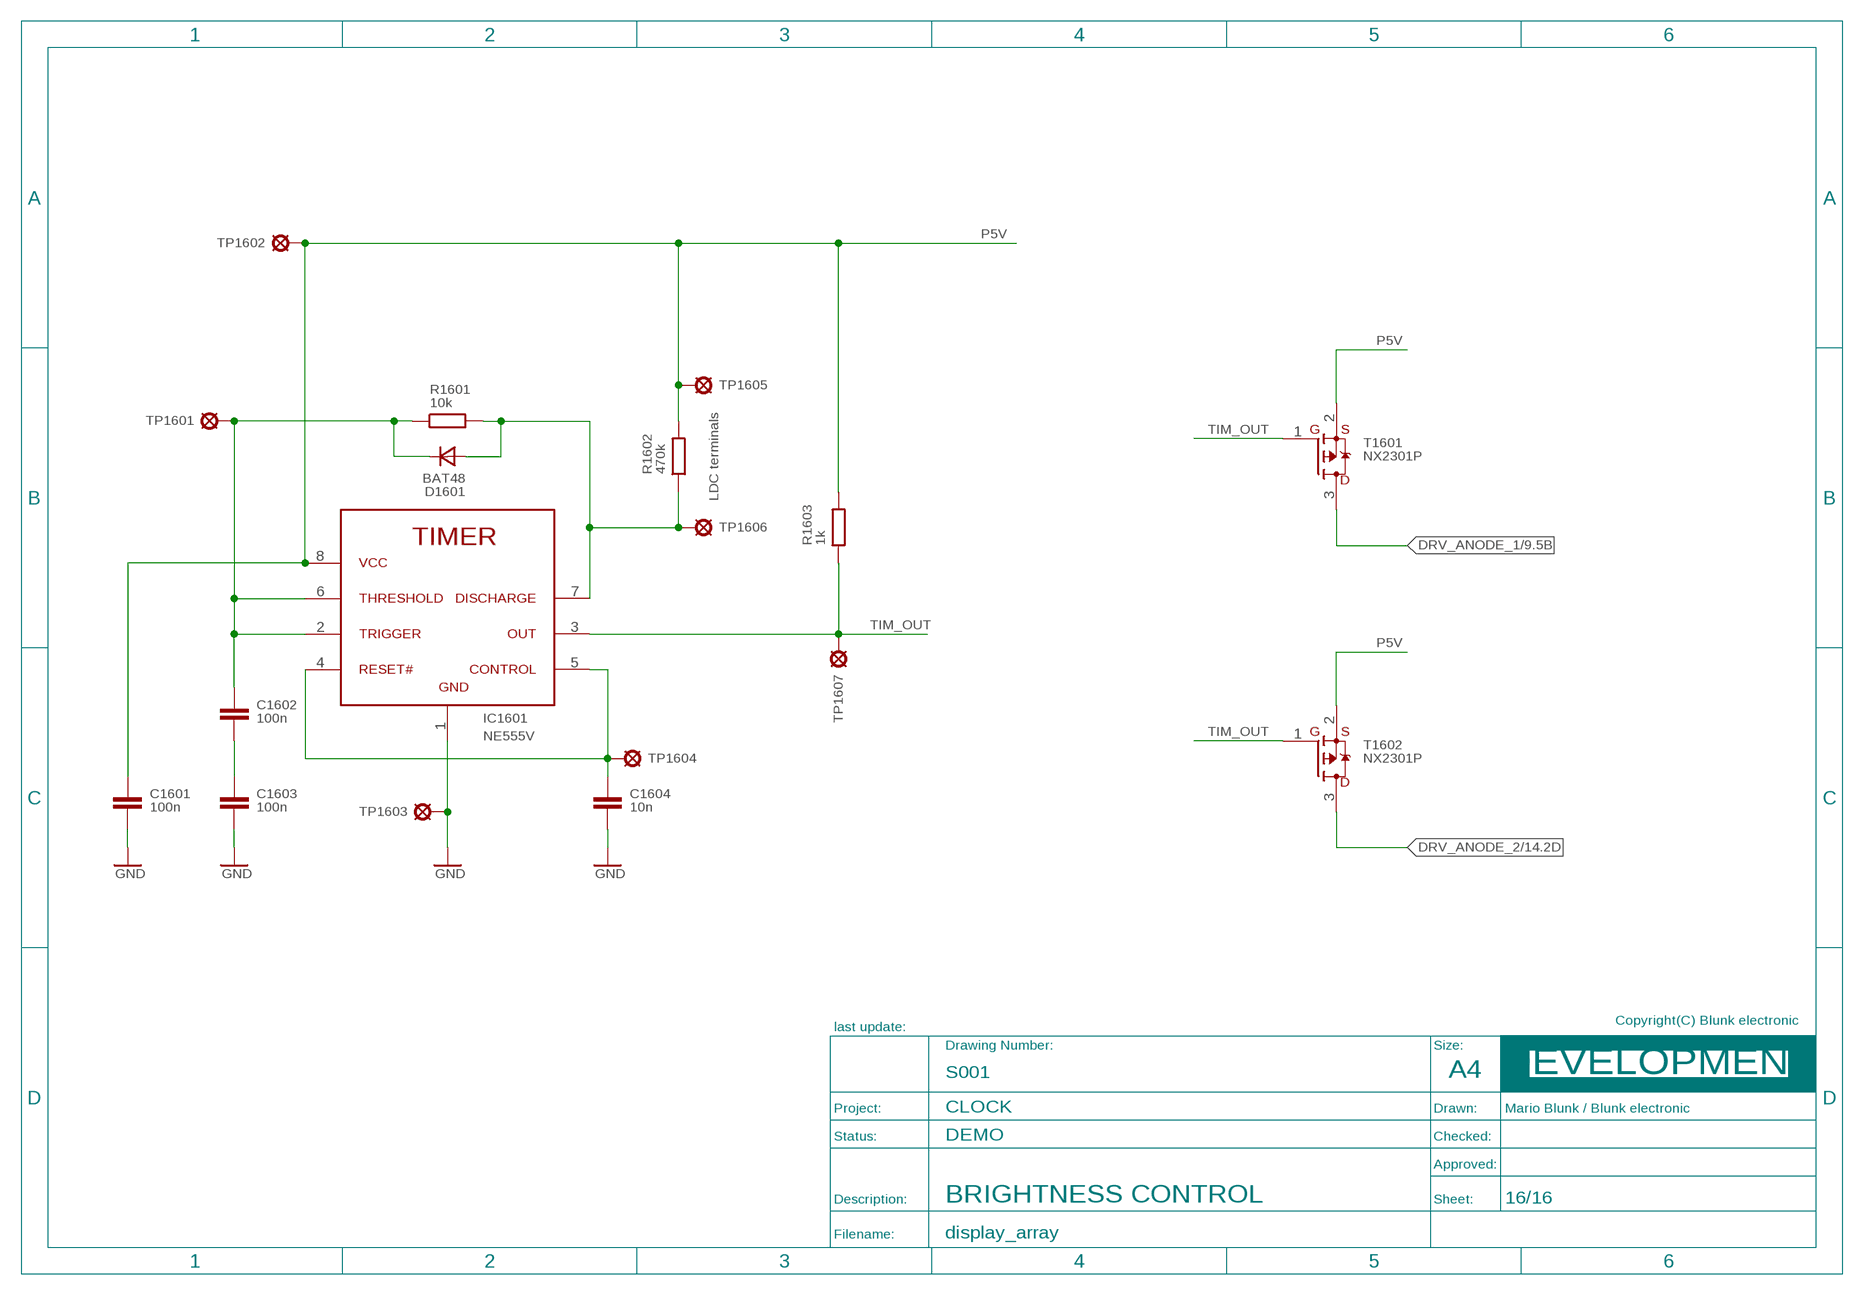
[diagram p15: schematic, sheet 16]

(export (version "E")
  (design (tool "Eeschema 10.0.6"))
  (components
    (comp (ref "C1001")
      (value "100n")
      (footprint "eagle-import:S_0805")
      (fields (field (name "PART_CODE_BEL") "C_PAC_S_0805_VAL_100n"))
      (libsource (lib "eagle-import") (part "C_EU_S_0805"))
    )
    (comp (ref "IC1001")
      (value "PCF8574AT")
      (footprint "eagle-import:S_SOIC16")
      (fields (field (name "PART_CODE_BEL") "IC_PAC_S_SOIC16_VAL_PCF8574AT"))
      (libsource (lib "eagle-import") (part "PCF8574T"))
    )
    (comp (ref "RN1001")
      (value "100")
      (footprint "eagle-import:T_SIL8")
      (fields (field (name "PART_CODE_BEL") "RN_PAC_T_SIL8_VAL_100"))
      (libsource (lib "eagle-import") (part "R_EU_ARRAY_4"))
    )
    (comp (ref "RN1002")
      (value "100")
      (footprint "eagle-import:T_SIL8")
      (fields (field (name "PART_CODE_BEL") "RN_PAC_T_SIL8_VAL_100"))
      (libsource (lib "eagle-import") (part "R_EU_ARRAY_4"))
    )
    (comp (ref "C601")
      (value "100n")
      (footprint "eagle-import:S_0805")
      (fields (field (name "PART_CODE_BEL") "C_PAC_S_0805_VAL_100n"))
      (libsource (lib "eagle-import") (part "C_EU_S_0805"))
    )
    (comp (ref "DIS601")
      (value "VQB71")
      (footprint "eagle-import:T_VQB71")
      (fields (field (name "FUNCTION") "digit 10^5"))
      (libsource (lib "eagle-import") (part "VQB71"))
    )
    (comp (ref "IC601")
      (value "PCF8574T")
      (footprint "eagle-import:S_SOIC16")
      (libsource (lib "eagle-import") (part "PCF8574T"))
    )
    (comp (ref "RN601")
      (value "100")
      (footprint "eagle-import:T_SIL8")
      (fields (field (name "PART_CODE_BEL") "RN_PAC_T_SIL8_VAL_100"))
      (libsource (lib "eagle-import") (part "R_EU_ARRAY_4"))
    )
    (comp (ref "RN602")
      (value "100")
      (footprint "eagle-import:T_SIL8")
      (fields (field (name "PART_CODE_BEL") "RN_PAC_T_SIL8_VAL_100"))
      (libsource (lib "eagle-import") (part "R_EU_ARRAY_4"))
    )
    (comp (ref "C901")
      (value "100n")
      (footprint "eagle-import:S_0805")
      (fields (field (name "PART_CODE_BEL") "C_PAC_S_0805_VAL_100n"))
      (libsource (lib "eagle-import") (part "C_EU_S_0805"))
    )
    (comp (ref "IC901")
      (value "PCF8574AT")
      (footprint "eagle-import:S_SOIC16")
      (fields (field (name "PART_CODE_BEL") "IC_PAC_S_SOIC16_VAL_PCF8574AT"))
      (libsource (lib "eagle-import") (part "PCF8574T"))
    )
    (comp (ref "LED901")
      (value "red")
      (footprint "eagle-import:S_0805")
      (fields
        (field (name "FUNCTION") "blinking dot")
        (field (name "PART_CODE_BEL") "LED_PAC_S_0805_VAL_red")
      )
      (libsource (lib "eagle-import") (part "LED_S_0805"))
    )
    (comp (ref "LED902")
      (value "red")
      (footprint "eagle-import:S_0805")
      (fields
        (field (name "FUNCTION") "blinking dot")
        (field (name "PART_CODE_BEL") "LED_PAC_S_0805_VAL_red")
      )
      (libsource (lib "eagle-import") (part "LED_S_0805"))
    )
    (comp (ref "LED903")
      (value "red")
      (footprint "eagle-import:S_0805")
      (fields
        (field (name "FUNCTION") "blinking dot")
        (field (name "PART_CODE_BEL") "LED_PAC_S_0805_VAL_red")
      )
      (libsource (lib "eagle-import") (part "LED_S_0805"))
    )
    (comp (ref "LED904")
      (value "green")
      (footprint "eagle-import:S_0805")
      (fields (field (name "FUNCTION") "status #1") (field (name "PART_CODE_BEL") "LED_PAC_S_0805_VAL_green"))
      (libsource (lib "eagle-import") (part "LED_S_0805"))
    )
    (comp (ref "LED905")
      (value "green")
      (footprint "eagle-import:S_0805")
      (fields (field (name "FUNCTION") "status #2") (field (name "PART_CODE_BEL") "LED_PAC_S_0805_VAL_green"))
      (libsource (lib "eagle-import") (part "LED_S_0805"))
    )
    (comp (ref "LED906")
      (value "yellow")
      (footprint "eagle-import:S_0805")
      (fields
        (field (name "FUNCTION") "status #3")
        (field (name "PART_CODE_BEL") "LED_PAC_S_0805_VAL_yellow")
      )
      (libsource (lib "eagle-import") (part "LED_S_0805"))
    )
    (comp (ref "LED907")
      (value "yellow")
      (footprint "eagle-import:S_0805")
      (fields
        (field (name "FUNCTION") "status #4")
        (field (name "PART_CODE_BEL") "LED_PAC_S_0805_VAL_yellow")
      )
      (libsource (lib "eagle-import") (part "LED_S_0805"))
    )
    (comp (ref "LED908")
      (value "red")
      (footprint "eagle-import:S_0805")
      (fields (field (name "FUNCTION") "status #5") (field (name "PART_CODE_BEL") "LED_PAC_S_0805_VAL_red"))
      (libsource (lib "eagle-import") (part "LED_S_0805"))
    )
    (comp (ref "LED909")
      (value "blue")
      (footprint "eagle-import:S_0805")
      (fields (field (name "FUNCTION") "status #6") (field (name "PART_CODE_BEL") "LED_PAC_S_0805_VAL_blue"))
      (libsource (lib "eagle-import") (part "LED_S_0805"))
    )
    (comp (ref "LED910")
      (value "blue")
      (footprint "eagle-import:S_0805")
      (fields (field (name "FUNCTION") "status #7") (field (name "PART_CODE_BEL") "LED_PAC_S_0805_VAL_blue"))
      (libsource (lib "eagle-import") (part "LED_S_0805"))
    )
    (comp (ref "LED911")
      (value "red")
      (footprint "eagle-import:S_0805")
      (fields
        (field (name "FUNCTION") "blinking dot")
        (field (name "PART_CODE_BEL") "LED_PAC_S_0805_VAL_red")
      )
      (libsource (lib "eagle-import") (part "LED_S_0805"))
    )
    (comp (ref "LED912")
      (value "red")
      (footprint "eagle-import:S_0805")
      (fields
        (field (name "FUNCTION") "blinking dot")
        (field (name "PART_CODE_BEL") "LED_PAC_S_0805_VAL_red")
      )
      (libsource (lib "eagle-import") (part "LED_S_0805"))
    )
    (comp (ref "LED913")
      (value "red")
      (footprint "eagle-import:S_0805")
      (fields
        (field (name "FUNCTION") "blinking dot")
        (field (name "PART_CODE_BEL") "LED_PAC_S_0805_VAL_red")
      )
      (libsource (lib "eagle-import") (part "LED_S_0805"))
    )
    (comp (ref "R901")
      (value "1k5")
      (footprint "eagle-import:S_0805")
      (fields (field (name "PART_CODE_BEL") "R_PAC_S_0805_VAL_1k5"))
      (libsource (lib "eagle-import") (part "R_EU_S_0805"))
    )
    (comp (ref "R902")
      (value "1k5")
      (footprint "eagle-import:S_0805")
      (fields (field (name "PART_CODE_BEL") "R_PAC_S_0805_VAL_1k5"))
      (libsource (lib "eagle-import") (part "R_EU_S_0805"))
    )
    (comp (ref "R903")
      (value "1k5")
      (footprint "eagle-import:S_0805")
      (fields (field (name "PART_CODE_BEL") "R_PAC_S_0805_VAL_1k5"))
      (libsource (lib "eagle-import") (part "R_EU_S_0805"))
    )
    (comp (ref "R904")
      (value "750")
      (footprint "eagle-import:S_0805")
      (fields (field (name "PART_CODE_BEL") "R_PAC_S_0805_VAL_750"))
      (libsource (lib "eagle-import") (part "R_EU_S_0805"))
    )
    (comp (ref "R905")
      (value "750")
      (footprint "eagle-import:S_0805")
      (fields (field (name "PART_CODE_BEL") "R_PAC_S_0805_VAL_750"))
      (libsource (lib "eagle-import") (part "R_EU_S_0805"))
    )
    (comp (ref "R906")
      (value "2k2")
      (footprint "eagle-import:S_0805")
      (fields (field (name "PART_CODE_BEL") "R_PAC_S_0805_VAL_2k2"))
      (libsource (lib "eagle-import") (part "R_EU_S_0805"))
    )
    (comp (ref "R907")
      (value "2k2")
      (footprint "eagle-import:S_0805")
      (fields (field (name "PART_CODE_BEL") "R_PAC_S_0805_VAL_2k2"))
      (libsource (lib "eagle-import") (part "R_EU_S_0805"))
    )
    (comp (ref "R908")
      (value "3k3")
      (footprint "eagle-import:S_0805")
      (fields (field (name "PART_CODE_BEL") "R_PAC_S_0805_VAL_3k3"))
      (libsource (lib "eagle-import") (part "R_EU_S_0805"))
    )
    (comp (ref "R909")
      (value "2k4")
      (footprint "eagle-import:S_0805")
      (fields (field (name "PART_CODE_BEL") "R_PAC_S_0805_VAL_2k4"))
      (libsource (lib "eagle-import") (part "R_EU_S_0805"))
    )
    (comp (ref "R910")
      (value "2k4")
      (footprint "eagle-import:S_0805")
      (fields (field (name "PART_CODE_BEL") "R_PAC_S_0805_VAL_2k4"))
      (libsource (lib "eagle-import") (part "R_EU_S_0805"))
    )
    (comp (ref "S1501")
      (value "set")
      (footprint "eagle-import:T_PUSH_BUTTON_6X6")
      (fields (field (name "FUNCTION") "SET1"))
      (libsource (lib "eagle-import") (part "PUSH_BUTTON_T_6X6MM"))
    )
    (comp (ref "S1502")
      (value "set")
      (footprint "eagle-import:T_PUSH_BUTTON_6X6")
      (fields (field (name "FUNCTION") "SET2"))
      (libsource (lib "eagle-import") (part "PUSH_BUTTON_T_6X6MM"))
    )
    (comp (ref "S1503")
      (value "set")
      (footprint "eagle-import:T_PUSH_BUTTON_6X6")
      (fields (field (name "FUNCTION") "SET3"))
      (libsource (lib "eagle-import") (part "PUSH_BUTTON_T_6X6MM"))
    )
    (comp (ref "S1504")
      (value "set")
      (footprint "eagle-import:T_PUSH_BUTTON_6X6")
      (fields (field (name "FUNCTION") "SET4"))
      (libsource (lib "eagle-import") (part "PUSH_BUTTON_T_6X6MM"))
    )
    (comp (ref "S1505")
      (value "set")
      (footprint "eagle-import:T_PUSH_BUTTON_6X6")
      (fields (field (name "FUNCTION") "SET5"))
      (libsource (lib "eagle-import") (part "PUSH_BUTTON_T_6X6MM"))
    )
    (comp (ref "S1506")
      (value "set")
      (footprint "eagle-import:T_PUSH_BUTTON_6X6")
      (fields (field (name "FUNCTION") "SET6"))
      (libsource (lib "eagle-import") (part "PUSH_BUTTON_T_6X6MM"))
    )
    (comp (ref "S1507")
      (value "set")
      (footprint "eagle-import:T_PUSH_BUTTON_6X6")
      (fields (field (name "FUNCTION") "SET7"))
      (libsource (lib "eagle-import") (part "PUSH_BUTTON_T_6X6MM"))
    )
    (comp (ref "S1508")
      (value "set")
      (footprint "eagle-import:T_PUSH_BUTTON_6X6")
      (fields (field (name "FUNCTION") "SET8"))
      (libsource (lib "eagle-import") (part "PUSH_BUTTON_T_6X6MM"))
    )
    (comp (ref "X1501")
      (value "MALE_2X13-T-VERTICAL_2.54MM")
      (footprint "eagle-import:T_MALE_2X13_VERTICAL_GRID_2.54MM")
      (fields (field (name "FUNCTION") "KEYPAD EXT,"))
      (libsource (lib "eagle-import") (part "MALE_2X13-T-VERTICAL_2.54MM"))
    )
    (comp (ref "C1301")
      (value "10u")
      (footprint "eagle-import:T_RADIAL_5MM_GRID_2.54MM")
      (fields (field (name "PART_CODE_BEL") "C_PAC_T_RADIAL_5mm_GRID_2.54mm_VAL_10u_Vmax_35V"))
      (libsource (lib "eagle-import") (part "C_POL_EU_T_RAD5_GRID_2.54"))
    )
    (comp (ref "C1302")
      (value "10u")
      (footprint "eagle-import:T_RADIAL_5MM_GRID_2.54MM")
      (fields (field (name "PART_CODE_BEL") "C_PAC_T_RADIAL_5mm_GRID_2.54mm_VAL_10u_Vmax_35V"))
      (libsource (lib "eagle-import") (part "C_POL_EU_T_RAD5_GRID_2.54"))
    )
    (comp (ref "C1303")
      (value "10u")
      (footprint "eagle-import:T_RADIAL_5MM_GRID_2.54MM")
      (fields (field (name "PART_CODE_BEL") "C_PAC_T_RADIAL_5mm_GRID_2.54mm_VAL_10u_Vmax_35V"))
      (libsource (lib "eagle-import") (part "C_POL_EU_T_RAD5_GRID_2.54"))
    )
    (comp (ref "C1304")
      (value "10u")
      (footprint "eagle-import:T_RADIAL_5MM_GRID_2.54MM")
      (fields (field (name "PART_CODE_BEL") "C_PAC_T_RADIAL_5mm_GRID_2.54mm_VAL_10u_Vmax_35V"))
      (libsource (lib "eagle-import") (part "C_POL_EU_T_RAD5_GRID_2.54"))
    )
    (comp (ref "C1305")
      (value "100n")
      (footprint "eagle-import:S_0805")
      (fields (field (name "PART_CODE_BEL") "C_PAC_S_0805_VAL_100n"))
      (libsource (lib "eagle-import") (part "C_EU_S_0805"))
    )
    (comp (ref "C1306")
      (value "100n")
      (footprint "eagle-import:S_0805")
      (fields (field (name "PART_CODE_BEL") "C_PAC_S_0805_VAL_100n"))
      (libsource (lib "eagle-import") (part "C_EU_S_0805"))
    )
    (comp (ref "IC1301")
      (value "SN7400N")
      (footprint "eagle-import:T_NDIP14")
      (fields (field (name "PART_CODE_BEL") "IC_PAC_T_NDIP14_VAL_SN7400N"))
      (libsource (lib "eagle-import") (part "7400N"))
    )
    (comp (ref "IC1302")
      (value "SN7400N")
      (footprint "eagle-import:T_NDIP14")
      (fields (field (name "PART_CODE_BEL") "IC_PAC_T_NDIP14_VAL_SN7400N"))
      (libsource (lib "eagle-import") (part "7400N"))
    )
    (comp (ref "RN1301")
      (value "220")
      (footprint "eagle-import:T_SIL8")
      (fields (field (name "PART_CODE_BEL") "RN_PAC_T_SIL8_VAL_220"))
      (libsource (lib "eagle-import") (part "R_EU_ARRAY_4"))
    )
    (comp (ref "RN1302")
      (value "220")
      (footprint "eagle-import:T_SIL8")
      (fields (field (name "PART_CODE_BEL") "RN_PAC_T_SIL8_VAL_220"))
      (libsource (lib "eagle-import") (part "R_EU_ARRAY_4"))
    )
    (comp (ref "RN1303")
      (value "4k7")
      (footprint "eagle-import:T_SIL8")
      (fields (field (name "PART_CODE_BEL") "RN_PAC_T_SIL8_VAL_4k7"))
      (libsource (lib "eagle-import") (part "R_EU_ARRAY_4"))
    )
    (comp (ref "C501")
      (value "100n")
      (footprint "eagle-import:S_0805")
      (fields (field (name "PART_CODE_BEL") "C_PAC_S_0805_VAL_100n"))
      (libsource (lib "eagle-import") (part "C_EU_S_0805"))
    )
    (comp (ref "DIS501")
      (value "VQB71")
      (footprint "eagle-import:T_VQB71")
      (fields (field (name "FUNCTION") "digit 10^4"))
      (libsource (lib "eagle-import") (part "VQB71"))
    )
    (comp (ref "IC501")
      (value "PCF8574T")
      (footprint "eagle-import:S_SOIC16")
      (libsource (lib "eagle-import") (part "PCF8574T"))
    )
    (comp (ref "RN501")
      (value "100")
      (footprint "eagle-import:T_SIL8")
      (fields (field (name "PART_CODE_BEL") "RN_PAC_T_SIL8_VAL_100"))
      (libsource (lib "eagle-import") (part "R_EU_ARRAY_4"))
    )
    (comp (ref "RN502")
      (value "100")
      (footprint "eagle-import:T_SIL8")
      (fields (field (name "PART_CODE_BEL") "RN_PAC_T_SIL8_VAL_100"))
      (libsource (lib "eagle-import") (part "R_EU_ARRAY_4"))
    )
    (comp (ref "C301")
      (value "100n")
      (footprint "eagle-import:S_0805")
      (fields (field (name "PART_CODE_BEL") "C_PAC_S_0805_VAL_100n"))
      (libsource (lib "eagle-import") (part "C_EU_S_0805"))
    )
    (comp (ref "DIS301")
      (value "VQB71")
      (footprint "eagle-import:T_VQB71")
      (fields (field (name "FUNCTION") "digit 10^2"))
      (libsource (lib "eagle-import") (part "VQB71"))
    )
    (comp (ref "IC301")
      (value "PCF8574T")
      (footprint "eagle-import:S_SOIC16")
      (libsource (lib "eagle-import") (part "PCF8574T"))
    )
    (comp (ref "RN301")
      (value "100")
      (footprint "eagle-import:T_SIL8")
      (fields (field (name "PART_CODE_BEL") "RN_PAC_T_SIL8_VAL_100"))
      (libsource (lib "eagle-import") (part "R_EU_ARRAY_4"))
    )
    (comp (ref "RN302")
      (value "100")
      (footprint "eagle-import:T_SIL8")
      (fields (field (name "PART_CODE_BEL") "RN_PAC_T_SIL8_VAL_100"))
      (libsource (lib "eagle-import") (part "R_EU_ARRAY_4"))
    )
    (comp (ref "C1201")
      (value "10u")
      (footprint "eagle-import:T_RADIAL_5MM_GRID_2.54MM")
      (fields (field (name "PART_CODE_BEL") "C_PAC_T_RADIAL_5mm_GRID_2.54mm_VAL_10u_Vmax_35V"))
      (libsource (lib "eagle-import") (part "C_POL_EU_T_RAD5_GRID_2.54"))
    )
    (comp (ref "C1202")
      (value "10u")
      (footprint "eagle-import:T_RADIAL_5MM_GRID_2.54MM")
      (fields (field (name "PART_CODE_BEL") "C_PAC_T_RADIAL_5mm_GRID_2.54mm_VAL_10u_Vmax_35V"))
      (libsource (lib "eagle-import") (part "C_POL_EU_T_RAD5_GRID_2.54"))
    )
    (comp (ref "C1203")
      (value "10u")
      (footprint "eagle-import:T_RADIAL_5MM_GRID_2.54MM")
      (fields (field (name "PART_CODE_BEL") "C_PAC_T_RADIAL_5mm_GRID_2.54mm_VAL_10u_Vmax_35V"))
      (libsource (lib "eagle-import") (part "C_POL_EU_T_RAD5_GRID_2.54"))
    )
    (comp (ref "C1204")
      (value "10u")
      (footprint "eagle-import:T_RADIAL_5MM_GRID_2.54MM")
      (fields (field (name "PART_CODE_BEL") "C_PAC_T_RADIAL_5mm_GRID_2.54mm_VAL_10u_Vmax_35V"))
      (libsource (lib "eagle-import") (part "C_POL_EU_T_RAD5_GRID_2.54"))
    )
    (comp (ref "C1205")
      (value "100n")
      (footprint "eagle-import:S_0805")
      (fields (field (name "PART_CODE_BEL") "C_PAC_S_0805_VAL_100n"))
      (libsource (lib "eagle-import") (part "C_EU_S_0805"))
    )
    (comp (ref "C1206")
      (value "100n")
      (footprint "eagle-import:S_0805")
      (fields (field (name "PART_CODE_BEL") "C_PAC_S_0805_VAL_100n"))
      (libsource (lib "eagle-import") (part "C_EU_S_0805"))
    )
    (comp (ref "IC1201")
      (value "SN7400N")
      (footprint "eagle-import:T_NDIP14")
      (fields (field (name "PART_CODE_BEL") "IC_PAC_T_NDIP14_VAL_SN7400N"))
      (libsource (lib "eagle-import") (part "7400N"))
    )
    (comp (ref "IC1202")
      (value "SN7400N")
      (footprint "eagle-import:T_NDIP14")
      (fields (field (name "PART_CODE_BEL") "IC_PAC_T_NDIP14_VAL_SN7400N"))
      (libsource (lib "eagle-import") (part "7400N"))
    )
    (comp (ref "RN1201")
      (value "220")
      (footprint "eagle-import:T_SIL8")
      (fields (field (name "PART_CODE_BEL") "RN_PAC_T_SIL8_VAL_220"))
      (libsource (lib "eagle-import") (part "R_EU_ARRAY_4"))
    )
    (comp (ref "RN1202")
      (value "220")
      (footprint "eagle-import:T_SIL8")
      (fields (field (name "PART_CODE_BEL") "RN_PAC_T_SIL8_VAL_220"))
      (libsource (lib "eagle-import") (part "R_EU_ARRAY_4"))
    )
    (comp (ref "RN1203")
      (value "4k7")
      (footprint "eagle-import:T_SIL8")
      (fields (field (name "PART_CODE_BEL") "RN_PAC_T_SIL8_VAL_4k7"))
      (libsource (lib "eagle-import") (part "R_EU_ARRAY_4"))
    )
    (comp (ref "FD1101")
      (value "FIDUCIAL_CROSSHAIR")
      (footprint "eagle-import:CROSSHAIR")
      (libsource (lib "eagle-import") (part "FIDUCIAL_CROSSHAIR"))
    )
    (comp (ref "FD1102")
      (value "FIDUCIAL_CROSSHAIR")
      (footprint "eagle-import:CROSSHAIR")
      (libsource (lib "eagle-import") (part "FIDUCIAL_CROSSHAIR"))
    )
    (comp (ref "H1101")
      (value "HOLE_4.1_PAD")
      (footprint "eagle-import:4.1_PAD")
      (libsource (lib "eagle-import") (part "HOLE_4.1_PAD"))
    )
    (comp (ref "H1102")
      (value "HOLE_4.1_PAD")
      (footprint "eagle-import:4.1_PAD")
      (libsource (lib "eagle-import") (part "HOLE_4.1_PAD"))
    )
    (comp (ref "H1103")
      (value "HOLE_4.1_PAD")
      (footprint "eagle-import:4.1_PAD")
      (libsource (lib "eagle-import") (part "HOLE_4.1_PAD"))
    )
    (comp (ref "H1104")
      (value "HOLE_4.1_PAD")
      (footprint "eagle-import:4.1_PAD")
      (libsource (lib "eagle-import") (part "HOLE_4.1_PAD"))
    )
    (comp (ref "TP1101")
      (value "TEST_POINT_T_SMALL")
      (footprint "eagle-import:T_TEST_POINT_SMALL")
      (libsource (lib "eagle-import") (part "TEST_POINT_T_SMALL"))
    )
    (comp (ref "TP1102")
      (value "TEST_POINT_T_SMALL")
      (footprint "eagle-import:T_TEST_POINT_SMALL")
      (libsource (lib "eagle-import") (part "TEST_POINT_T_SMALL"))
    )
    (comp (ref "TP1103")
      (value "TEST_POINT_T_SMALL")
      (footprint "eagle-import:T_TEST_POINT_SMALL")
      (libsource (lib "eagle-import") (part "TEST_POINT_T_SMALL"))
    )
    (comp (ref "TP1104")
      (value "TEST_POINT_T_SMALL")
      (footprint "eagle-import:T_TEST_POINT_SMALL")
      (libsource (lib "eagle-import") (part "TEST_POINT_T_SMALL"))
    )
    (comp (ref "TP1105")
      (value "TEST_POINT_T_SMALL")
      (footprint "eagle-import:T_TEST_POINT_SMALL")
      (libsource (lib "eagle-import") (part "TEST_POINT_T_SMALL"))
    )
    (comp (ref "TP1106")
      (value "TEST_POINT_T_SMALL")
      (footprint "eagle-import:T_TEST_POINT_SMALL")
      (libsource (lib "eagle-import") (part "TEST_POINT_T_SMALL"))
    )
    (comp (ref "TP1107")
      (value "TEST_POINT_T_SMALL")
      (footprint "eagle-import:T_TEST_POINT_SMALL")
      (libsource (lib "eagle-import") (part "TEST_POINT_T_SMALL"))
    )
    (comp (ref "TP1108")
      (value "TEST_POINT_T_SMALL")
      (footprint "eagle-import:T_TEST_POINT_SMALL")
      (libsource (lib "eagle-import") (part "TEST_POINT_T_SMALL"))
    )
    (comp (ref "TP1109")
      (value "TEST_POINT_T_SMALL")
      (footprint "eagle-import:T_TEST_POINT_SMALL")
      (libsource (lib "eagle-import") (part "TEST_POINT_T_SMALL"))
    )
    (comp (ref "TP1110")
      (value "TEST_POINT_T_SMALL")
      (footprint "eagle-import:T_TEST_POINT_SMALL")
      (libsource (lib "eagle-import") (part "TEST_POINT_T_SMALL"))
    )
    (comp (ref "TP1111")
      (value "TEST_POINT_T_SMALL")
      (footprint "eagle-import:T_TEST_POINT_SMALL")
      (libsource (lib "eagle-import") (part "TEST_POINT_T_SMALL"))
    )
    (comp (ref "TP1112")
      (value "TEST_POINT_T_SMALL")
      (footprint "eagle-import:T_TEST_POINT_SMALL")
      (libsource (lib "eagle-import") (part "TEST_POINT_T_SMALL"))
    )
    (comp (ref "TP1113")
      (value "TEST_POINT_T_SMALL")
      (footprint "eagle-import:T_TEST_POINT_SMALL")
      (libsource (lib "eagle-import") (part "TEST_POINT_T_SMALL"))
    )
    (comp (ref "TP1114")
      (value "TEST_POINT_T_SMALL")
      (footprint "eagle-import:T_TEST_POINT_SMALL")
      (libsource (lib "eagle-import") (part "TEST_POINT_T_SMALL"))
    )
    (comp (ref "TP1115")
      (value "TEST_POINT_T_SMALL")
      (footprint "eagle-import:T_TEST_POINT_SMALL")
      (libsource (lib "eagle-import") (part "TEST_POINT_T_SMALL"))
    )
    (comp (ref "TP1116")
      (value "TEST_POINT_T_SMALL")
      (footprint "eagle-import:T_TEST_POINT_SMALL")
      (libsource (lib "eagle-import") (part "TEST_POINT_T_SMALL"))
    )
    (comp (ref "TP1117")
      (value "TEST_POINT_T_SMALL")
      (footprint "eagle-import:T_TEST_POINT_SMALL")
      (libsource (lib "eagle-import") (part "TEST_POINT_T_SMALL"))
    )
    (comp (ref "TP1118")
      (value "TEST_POINT_T_SMALL")
      (footprint "eagle-import:T_TEST_POINT_SMALL")
      (libsource (lib "eagle-import") (part "TEST_POINT_T_SMALL"))
    )
    (comp (ref "TP1119")
      (value "TEST_POINT_T_SMALL")
      (footprint "eagle-import:T_TEST_POINT_SMALL")
      (libsource (lib "eagle-import") (part "TEST_POINT_T_SMALL"))
    )
    (comp (ref "TP1120")
      (value "TEST_POINT_T_SMALL")
      (footprint "eagle-import:T_TEST_POINT_SMALL")
      (libsource (lib "eagle-import") (part "TEST_POINT_T_SMALL"))
    )
    (comp (ref "TP1121")
      (value "TEST_POINT_T_SMALL")
      (footprint "eagle-import:T_TEST_POINT_SMALL")
      (libsource (lib "eagle-import") (part "TEST_POINT_T_SMALL"))
    )
    (comp (ref "TP1122")
      (value "TEST_POINT_T_SMALL")
      (footprint "eagle-import:T_TEST_POINT_SMALL")
      (libsource (lib "eagle-import") (part "TEST_POINT_T_SMALL"))
    )
    (comp (ref "TP1123")
      (value "TEST_POINT_T_SMALL")
      (footprint "eagle-import:T_TEST_POINT_SMALL")
      (libsource (lib "eagle-import") (part "TEST_POINT_T_SMALL"))
    )
    (comp (ref "TP1124")
      (value "TEST_POINT_T_SMALL")
      (footprint "eagle-import:T_TEST_POINT_SMALL")
      (libsource (lib "eagle-import") (part "TEST_POINT_T_SMALL"))
    )
    (comp (ref "TP1125")
      (value "TEST_POINT_T_SMALL")
      (footprint "eagle-import:T_TEST_POINT_SMALL")
      (libsource (lib "eagle-import") (part "TEST_POINT_T_SMALL"))
    )
    (comp (ref "TP1126")
      (value "TEST_POINT_T_SMALL")
      (footprint "eagle-import:T_TEST_POINT_SMALL")
      (libsource (lib "eagle-import") (part "TEST_POINT_T_SMALL"))
    )
    (comp (ref "TP1127")
      (value "TEST_POINT_T_SMALL")
      (footprint "eagle-import:T_TEST_POINT_SMALL")
      (libsource (lib "eagle-import") (part "TEST_POINT_T_SMALL"))
    )
    (comp (ref "C1401")
      (value "100u")
      (footprint "eagle-import:T_RADIAL_7MM_GRID_2.54MM")
      (fields (field (name "PART_CODE_BEL") "C_PAC_T_RADIAL_7mm_GRID_2.54mm_VAL_100u_Vmax_35V"))
      (libsource (lib "eagle-import") (part "C_POL_EU_T_RAD7_GRID_2.54"))
    )
    (comp (ref "C1402")
      (value "100u")
      (footprint "eagle-import:T_RADIAL_7MM_GRID_2.54MM")
      (fields (field (name "PART_CODE_BEL") "C_PAC_T_RADIAL_7mm_GRID_2.54mm_VAL_100u_Vmax_35V"))
      (libsource (lib "eagle-import") (part "C_POL_EU_T_RAD7_GRID_2.54"))
    )
    (comp (ref "D1401")
      (value "1N5400")
      (footprint "eagle-import:T_DO201_GRID_18MM")
      (fields (field (name "PART_CODE_BEL") "D_PAC_T_DO201_GRID_18MM_VAL_1N5400"))
      (libsource (lib "eagle-import") (part "SINGLE_T_DO201_GRID_18MM"))
    )
    (comp (ref "LED1401")
      (value "green")
      (footprint "eagle-import:S_0805")
      (fields (field (name "FUNCTION") "POWER ON") (field (name "PART_CODE_BEL") "LED_PAC_S_0805_VAL_green"))
      (libsource (lib "eagle-import") (part "LED_S_0805"))
    )
    (comp (ref "R1401")
      (value "220")
      (footprint "eagle-import:S_0805")
      (fields (field (name "PART_CODE_BEL") "R_PAC_S_0805_VAL_220"))
      (libsource (lib "eagle-import") (part "R_EU_S_0805"))
    )
    (comp (ref "RN1401")
      (value "10k")
      (footprint "eagle-import:T_SIL9")
      (fields (field (name "BOM") "NO"))
      (libsource (lib "eagle-import") (part "R_EU_ARRAY_1C_8_T_SIL9"))
    )
    (comp (ref "RN1402")
      (value "10k")
      (footprint "eagle-import:T_SIL9")
      (fields (field (name "BOM") "NO"))
      (libsource (lib "eagle-import") (part "R_EU_ARRAY_1C_8_T_SIL9"))
    )
    (comp (ref "TP1401")
      (value "TEST_POINT_T_SMALL")
      (footprint "eagle-import:T_TEST_POINT_SMALL")
      (fields (field (name "FUNCTION") "SCL"))
      (libsource (lib "eagle-import") (part "TEST_POINT_T_SMALL"))
    )
    (comp (ref "TP1402")
      (value "TEST_POINT_T_SMALL")
      (footprint "eagle-import:T_TEST_POINT_SMALL")
      (fields (field (name "FUNCTION") "SDA"))
      (libsource (lib "eagle-import") (part "TEST_POINT_T_SMALL"))
    )
    (comp (ref "X1401")
      (value "CLAMP_1X4-T-5MM")
      (footprint "eagle-import:T_WIRE_CLAMP_1X4_5MM")
      (fields (field (name "FUNCTION") "PWR P5V IN"))
      (libsource (lib "eagle-import") (part "CLAMP_1X4-T-5MM"))
    )
    (comp (ref "X1402")
      (value "MALE_2X13-T-VERTICAL_2.54MM")
      (footprint "eagle-import:T_MALE_2X13_VERTICAL_GRID_2.54MM")
      (fields (field (name "FUNCTION") "CTRL"))
      (libsource (lib "eagle-import") (part "MALE_2X13-T-VERTICAL_2.54MM"))
    )
    (comp (ref "X1403")
      (value "MALE_1X3")
      (footprint "eagle-import:T_MALE_3X1_VERTICAL")
      (fields (field (name "FUNCTION") "DEBUG & INSTRUMENTATION"))
      (libsource (lib "eagle-import") (part "MALE_1X3"))
    )
    (comp (ref "C1601")
      (value "100n")
      (footprint "eagle-import:S_0805")
      (fields (field (name "PART_CODE_BEL") "C_PAC_S_0805_VAL_100n"))
      (libsource (lib "eagle-import") (part "C_EU_S_0805"))
    )
    (comp (ref "C1602")
      (value "100n")
      (footprint "eagle-import:S_0805")
      (fields (field (name "PART_CODE_BEL") "C_PAC_S_0805_VAL_100n"))
      (libsource (lib "eagle-import") (part "C_EU_S_0805"))
    )
    (comp (ref "C1603")
      (value "100n")
      (footprint "eagle-import:S_0805")
      (fields (field (name "PART_CODE_BEL") "C_PAC_S_0805_VAL_100n"))
      (libsource (lib "eagle-import") (part "C_EU_S_0805"))
    )
    (comp (ref "C1604")
      (value "10n")
      (footprint "eagle-import:S_0805")
      (fields (field (name "PART_CODE_BEL") "C_PAC_S_0805_VAL_10n"))
      (libsource (lib "eagle-import") (part "C_EU_S_0805"))
    )
    (comp (ref "D1601")
      (value "BAT48")
      (footprint "eagle-import:T_DO204_GRID_10MM")
      (fields (field (name "PART_CODE_BEL") "D_PAC_T_DO204_GRID_10mm_VAL_BAT48"))
      (libsource (lib "eagle-import") (part "SINGLE_T_DO204_GRID_10MM"))
    )
    (comp (ref "IC1601")
      (value "NE555V")
      (footprint "eagle-import:T_NDIP8")
      (fields (field (name "PART_CODE_BEL") "IC_PAC_T_NDIP8_VAL_NE555V"))
      (libsource (lib "eagle-import") (part "555P"))
    )
    (comp (ref "R1601")
      (value "10k")
      (footprint "eagle-import:S_0805")
      (fields (field (name "PART_CODE_BEL") "R_PAC_S_0805_VAL_10k"))
      (libsource (lib "eagle-import") (part "R_EU_S_0805"))
    )
    (comp (ref "R1602")
      (value "470k")
      (footprint "eagle-import:S_0805")
      (fields (field (name "PART_CODE_BEL") "R_PAC_S_0805_VAL_470k"))
      (libsource (lib "eagle-import") (part "R_EU_S_0805"))
    )
    (comp (ref "R1603")
      (value "1k")
      (footprint "eagle-import:S_0805")
      (fields (field (name "PART_CODE_BEL") "R_PAC_S_0805_VAL_1k"))
      (libsource (lib "eagle-import") (part "R_EU_S_0805"))
    )
    (comp (ref "T1601")
      (value "NX2301P")
      (footprint "eagle-import:S_SOT23")
      (fields (field (name "PART_CODE_BEL") "T_PAC_S_SOT23_VAL_NX2301P"))
      (libsource (lib "eagle-import") (part "P-MOSFET"))
    )
    (comp (ref "T1602")
      (value "NX2301P")
      (footprint "eagle-import:S_SOT23")
      (fields (field (name "PART_CODE_BEL") "T_PAC_S_SOT23_VAL_NX2301P"))
      (libsource (lib "eagle-import") (part "P-MOSFET"))
    )
    (comp (ref "TP1601")
      (value "TEST_POINT_T_SMALL")
      (footprint "eagle-import:T_TEST_POINT_SMALL")
      (libsource (lib "eagle-import") (part "TEST_POINT_T_SMALL"))
    )
    (comp (ref "TP1602")
      (value "TEST_POINT_T_SMALL")
      (footprint "eagle-import:T_TEST_POINT_SMALL")
      (libsource (lib "eagle-import") (part "TEST_POINT_T_SMALL"))
    )
    (comp (ref "TP1603")
      (value "TEST_POINT_T_SMALL")
      (footprint "eagle-import:T_TEST_POINT_SMALL")
      (libsource (lib "eagle-import") (part "TEST_POINT_T_SMALL"))
    )
    (comp (ref "TP1604")
      (value "TEST_POINT_T_SMALL")
      (footprint "eagle-import:T_TEST_POINT_SMALL")
      (libsource (lib "eagle-import") (part "TEST_POINT_T_SMALL"))
    )
    (comp (ref "TP1605")
      (value "TEST_POINT_T_LARGE")
      (footprint "eagle-import:T_TEST_POINT_LARGE")
      (libsource (lib "eagle-import") (part "TEST_POINT_T_LARGE"))
    )
    (comp (ref "TP1606")
      (value "TEST_POINT_T_LARGE")
      (footprint "eagle-import:T_TEST_POINT_LARGE")
      (libsource (lib "eagle-import") (part "TEST_POINT_T_LARGE"))
    )
    (comp (ref "TP1607")
      (value "TEST_POINT_T_SMALL")
      (footprint "eagle-import:T_TEST_POINT_SMALL")
      (libsource (lib "eagle-import") (part "TEST_POINT_T_SMALL"))
    )
    (comp (ref "C401")
      (value "100n")
      (footprint "eagle-import:S_0805")
      (fields (field (name "PART_CODE_BEL") "C_PAC_S_0805_VAL_100n"))
      (libsource (lib "eagle-import") (part "C_EU_S_0805"))
    )
    (comp (ref "DIS401")
      (value "VQB71")
      (footprint "eagle-import:T_VQB71")
      (fields (field (name "FUNCTION") "digit 10^3"))
      (libsource (lib "eagle-import") (part "VQB71"))
    )
    (comp (ref "IC401")
      (value "PCF8574T")
      (footprint "eagle-import:S_SOIC16")
      (libsource (lib "eagle-import") (part "PCF8574T"))
    )
    (comp (ref "RN401")
      (value "100")
      (footprint "eagle-import:T_SIL8")
      (fields (field (name "PART_CODE_BEL") "RN_PAC_T_SIL8_VAL_100"))
      (libsource (lib "eagle-import") (part "R_EU_ARRAY_4"))
    )
    (comp (ref "RN402")
      (value "100")
      (footprint "eagle-import:T_SIL8")
      (fields (field (name "PART_CODE_BEL") "RN_PAC_T_SIL8_VAL_100"))
      (libsource (lib "eagle-import") (part "R_EU_ARRAY_4"))
    )
    (comp (ref "C701")
      (value "100n")
      (footprint "eagle-import:S_0805")
      (fields (field (name "PART_CODE_BEL") "C_PAC_S_0805_VAL_100n"))
      (libsource (lib "eagle-import") (part "C_EU_S_0805"))
    )
    (comp (ref "DIS701")
      (value "VQB71")
      (footprint "eagle-import:T_VQB71")
      (fields (field (name "FUNCTION") "digit 10^6"))
      (libsource (lib "eagle-import") (part "VQB71"))
    )
    (comp (ref "IC701")
      (value "PCF8574T")
      (footprint "eagle-import:S_SOIC16")
      (libsource (lib "eagle-import") (part "PCF8574T"))
    )
    (comp (ref "RN701")
      (value "100")
      (footprint "eagle-import:T_SIL8")
      (fields (field (name "PART_CODE_BEL") "RN_PAC_T_SIL8_VAL_100"))
      (libsource (lib "eagle-import") (part "R_EU_ARRAY_4"))
    )
    (comp (ref "RN702")
      (value "100")
      (footprint "eagle-import:T_SIL8")
      (fields (field (name "PART_CODE_BEL") "RN_PAC_T_SIL8_VAL_100"))
      (libsource (lib "eagle-import") (part "R_EU_ARRAY_4"))
    )
    (comp (ref "C101")
      (value "100n")
      (footprint "eagle-import:S_0805")
      (fields (field (name "PART_CODE_BEL") "C_PAC_S_0805_VAL_100n"))
      (libsource (lib "eagle-import") (part "C_EU_S_0805"))
    )
    (comp (ref "DIS101")
      (value "VQB71")
      (footprint "eagle-import:T_VQB71")
      (fields (field (name "FUNCTION") "digit 10^0"))
      (libsource (lib "eagle-import") (part "VQB71"))
    )
    (comp (ref "IC101")
      (value "PCF8574T")
      (footprint "eagle-import:S_SOIC16")
      (libsource (lib "eagle-import") (part "PCF8574T"))
    )
    (comp (ref "RN101")
      (value "100")
      (footprint "eagle-import:T_SIL8")
      (fields (field (name "PART_CODE_BEL") "RN_PAC_T_SIL8_VAL_100"))
      (libsource (lib "eagle-import") (part "R_EU_ARRAY_4"))
    )
    (comp (ref "RN102")
      (value "100")
      (footprint "eagle-import:T_SIL8")
      (fields (field (name "PART_CODE_BEL") "RN_PAC_T_SIL8_VAL_100"))
      (libsource (lib "eagle-import") (part "R_EU_ARRAY_4"))
    )
    (comp (ref "C801")
      (value "100n")
      (footprint "eagle-import:S_0805")
      (fields (field (name "PART_CODE_BEL") "C_PAC_S_0805_VAL_100n"))
      (libsource (lib "eagle-import") (part "C_EU_S_0805"))
    )
    (comp (ref "DIS801")
      (value "VQB71")
      (footprint "eagle-import:T_VQB71")
      (fields (field (name "FUNCTION") "digit 10^7"))
      (libsource (lib "eagle-import") (part "VQB71"))
    )
    (comp (ref "IC801")
      (value "PCF8574T")
      (footprint "eagle-import:S_SOIC16")
      (libsource (lib "eagle-import") (part "PCF8574T"))
    )
    (comp (ref "RN801")
      (value "100")
      (footprint "eagle-import:T_SIL8")
      (fields (field (name "PART_CODE_BEL") "RN_PAC_T_SIL8_VAL_100"))
      (libsource (lib "eagle-import") (part "R_EU_ARRAY_4"))
    )
    (comp (ref "RN802")
      (value "100")
      (footprint "eagle-import:T_SIL8")
      (fields (field (name "PART_CODE_BEL") "RN_PAC_T_SIL8_VAL_100"))
      (libsource (lib "eagle-import") (part "R_EU_ARRAY_4"))
    )
    (comp (ref "C201")
      (value "100n")
      (footprint "eagle-import:S_0805")
      (fields (field (name "PART_CODE_BEL") "C_PAC_S_0805_VAL_100n"))
      (libsource (lib "eagle-import") (part "C_EU_S_0805"))
    )
    (comp (ref "DIS201")
      (value "VQB71")
      (footprint "eagle-import:T_VQB71")
      (fields (field (name "FUNCTION") "digit 10^1"))
      (libsource (lib "eagle-import") (part "VQB71"))
    )
    (comp (ref "IC201")
      (value "PCF8574T")
      (footprint "eagle-import:S_SOIC16")
      (libsource (lib "eagle-import") (part "PCF8574T"))
    )
    (comp (ref "RN201")
      (value "100")
      (footprint "eagle-import:T_SIL8")
      (fields (field (name "PART_CODE_BEL") "RN_PAC_T_SIL8_VAL_100"))
      (libsource (lib "eagle-import") (part "R_EU_ARRAY_4"))
    )
    (comp (ref "RN202")
      (value "100")
      (footprint "eagle-import:T_SIL8")
      (fields (field (name "PART_CODE_BEL") "RN_PAC_T_SIL8_VAL_100"))
      (libsource (lib "eagle-import") (part "R_EU_ARRAY_4"))
    )
  )
  (nets
    (net (code "1") (name "CTRL_ACK#") (class "Default")
      (node (ref "RN1402") (pin "3") (pinfunction "3_3") (pintype "passive"))
      (node (ref "X1402") (pin "19") (pinfunction "19_19") (pintype "passive"))
    )
    (net (code "2") (name "CTRL_B2") (class "Default")
      (node (ref "RN1401") (pin "4") (pinfunction "4_4") (pintype "passive"))
      (node (ref "X1402") (pin "7") (pinfunction "7_7") (pintype "passive"))
    )
    (net (code "3") (name "CTRL_B3") (class "Default")
      (node (ref "RN1401") (pin "5") (pinfunction "5_5") (pintype "passive"))
      (node (ref "X1402") (pin "9") (pinfunction "9_9") (pintype "passive"))
    )
    (net (code "4") (name "CTRL_B4") (class "Default")
      (node (ref "RN1401") (pin "6") (pinfunction "6_6") (pintype "passive"))
      (node (ref "X1402") (pin "11") (pinfunction "11_11") (pintype "passive"))
    )
    (net (code "5") (name "CTRL_B5") (class "Default")
      (node (ref "RN1401") (pin "7") (pinfunction "7_7") (pintype "passive"))
      (node (ref "X1402") (pin "13") (pinfunction "13_13") (pintype "passive"))
    )
    (net (code "6") (name "CTRL_B6") (class "Default")
      (node (ref "RN1401") (pin "8") (pinfunction "8_8") (pintype "passive"))
      (node (ref "X1402") (pin "15") (pinfunction "15_15") (pintype "passive"))
    )
    (net (code "7") (name "CTRL_B7") (class "Default")
      (node (ref "RN1401") (pin "9") (pinfunction "9_9") (pintype "passive"))
      (node (ref "X1402") (pin "17") (pinfunction "17_17") (pintype "passive"))
    )
    (net (code "8") (name "CTRL_BUSY") (class "Default")
      (node (ref "RN1402") (pin "4") (pinfunction "4_4") (pintype "passive"))
      (node (ref "X1402") (pin "21") (pinfunction "21_21") (pintype "passive"))
    )
    (net (code "9") (name "CTRL_SCL") (class "Default")
      (node (ref "IC1001") (pin "14") (pinfunction "SCL_14") (pintype "input"))
      (node (ref "IC101") (pin "14") (pinfunction "SCL_14") (pintype "input"))
      (node (ref "IC201") (pin "14") (pinfunction "SCL_14") (pintype "input"))
      (node (ref "IC301") (pin "14") (pinfunction "SCL_14") (pintype "input"))
      (node (ref "IC401") (pin "14") (pinfunction "SCL_14") (pintype "input"))
      (node (ref "IC501") (pin "14") (pinfunction "SCL_14") (pintype "input"))
      (node (ref "IC601") (pin "14") (pinfunction "SCL_14") (pintype "input"))
      (node (ref "IC701") (pin "14") (pinfunction "SCL_14") (pintype "input"))
      (node (ref "IC801") (pin "14") (pinfunction "SCL_14") (pintype "input"))
      (node (ref "IC901") (pin "14") (pinfunction "SCL_14") (pintype "input"))
      (node (ref "RN1401") (pin "2") (pinfunction "2_2") (pintype "passive"))
      (node (ref "TP1401") (pin "1") (pinfunction "TP_1") (pintype "passive"))
      (node (ref "X1402") (pin "3") (pinfunction "3_3") (pintype "passive"))
    )
    (net (code "10") (name "CTRL_SDA") (class "Default")
      (node (ref "IC1001") (pin "15") (pinfunction "SDA_15") (pintype "bidirectional"))
      (node (ref "IC101") (pin "15") (pinfunction "SDA_15") (pintype "bidirectional"))
      (node (ref "IC201") (pin "15") (pinfunction "SDA_15") (pintype "bidirectional"))
      (node (ref "IC301") (pin "15") (pinfunction "SDA_15") (pintype "bidirectional"))
      (node (ref "IC401") (pin "15") (pinfunction "SDA_15") (pintype "bidirectional"))
      (node (ref "IC501") (pin "15") (pinfunction "SDA_15") (pintype "bidirectional"))
      (node (ref "IC601") (pin "15") (pinfunction "SDA_15") (pintype "bidirectional"))
      (node (ref "IC701") (pin "15") (pinfunction "SDA_15") (pintype "bidirectional"))
      (node (ref "IC801") (pin "15") (pinfunction "SDA_15") (pintype "bidirectional"))
      (node (ref "IC901") (pin "15") (pinfunction "SDA_15") (pintype "bidirectional"))
      (node (ref "RN1401") (pin "3") (pinfunction "3_3") (pintype "passive"))
      (node (ref "TP1402") (pin "1") (pinfunction "TP_1") (pintype "passive"))
      (node (ref "X1402") (pin "5") (pinfunction "5_5") (pintype "passive"))
    )
    (net (code "11") (name "CTRL_STROBE#") (class "Default")
      (node (ref "RN1402") (pin "2") (pinfunction "2_2") (pintype "passive"))
      (node (ref "X1402") (pin "1") (pinfunction "1_1") (pintype "passive"))
    )
    (net (code "12") (name "DEBOUNCER_1_OUT#") (class "Default")
      (node (ref "IC1201") (pin "6") (pinfunction "O_6") (pintype "output"))
      (node (ref "RN1001") (pin "2") (pinfunction "2_2") (pintype "passive"))
      (node (ref "RN1203") (pin "4") (pinfunction "2_4") (pintype "passive"))
    )
    (net (code "13") (name "DEBOUNCER_2_OUT#") (class "Default")
      (node (ref "IC1201") (pin "8") (pinfunction "O_8") (pintype "output"))
      (node (ref "RN1001") (pin "4") (pinfunction "2_4") (pintype "passive"))
      (node (ref "RN1203") (pin "2") (pinfunction "2_2") (pintype "passive"))
    )
    (net (code "14") (name "DEBOUNCER_3_OUT#") (class "Default")
      (node (ref "IC1202") (pin "6") (pinfunction "O_6") (pintype "output"))
      (node (ref "RN1001") (pin "6") (pinfunction "2_6") (pintype "passive"))
      (node (ref "RN1203") (pin "6") (pinfunction "2_6") (pintype "passive"))
    )
    (net (code "15") (name "DEBOUNCER_4_OUT#") (class "Default")
      (node (ref "IC1202") (pin "8") (pinfunction "O_8") (pintype "output"))
      (node (ref "RN1001") (pin "8") (pinfunction "2_8") (pintype "passive"))
      (node (ref "RN1203") (pin "8") (pinfunction "2_8") (pintype "passive"))
    )
    (net (code "16") (name "DEBOUNCER_5_OUT#") (class "Default")
      (node (ref "IC1301") (pin "6") (pinfunction "O_6") (pintype "output"))
      (node (ref "RN1002") (pin "2") (pinfunction "2_2") (pintype "passive"))
      (node (ref "RN1303") (pin "4") (pinfunction "2_4") (pintype "passive"))
    )
    (net (code "17") (name "DEBOUNCER_6_OUT#") (class "Default")
      (node (ref "IC1301") (pin "8") (pinfunction "O_8") (pintype "output"))
      (node (ref "RN1002") (pin "4") (pinfunction "2_4") (pintype "passive"))
      (node (ref "RN1303") (pin "2") (pinfunction "2_2") (pintype "passive"))
    )
    (net (code "18") (name "DEBOUNCER_7_OUT#") (class "Default")
      (node (ref "IC1302") (pin "6") (pinfunction "O_6") (pintype "output"))
      (node (ref "RN1002") (pin "6") (pinfunction "2_6") (pintype "passive"))
      (node (ref "RN1303") (pin "6") (pinfunction "2_6") (pintype "passive"))
    )
    (net (code "19") (name "DEBOUNCER_8_OUT#") (class "Default")
      (node (ref "IC1302") (pin "8") (pinfunction "O_8") (pintype "output"))
      (node (ref "RN1002") (pin "8") (pinfunction "2_8") (pintype "passive"))
      (node (ref "RN1303") (pin "8") (pinfunction "2_8") (pintype "passive"))
    )
    (net (code "20") (name "DRV_1_SEG_A") (class "Default")
      (node (ref "IC101") (pin "4") (pinfunction "P0_4") (pintype "bidirectional"))
      (node (ref "RN101") (pin "1") (pinfunction "1_1") (pintype "passive"))
    )
    (net (code "21") (name "DRV_1_SEG_B") (class "Default")
      (node (ref "IC101") (pin "5") (pinfunction "P1_5") (pintype "bidirectional"))
      (node (ref "RN101") (pin "3") (pinfunction "1_3") (pintype "passive"))
    )
    (net (code "22") (name "DRV_1_SEG_C") (class "Default")
      (node (ref "IC101") (pin "6") (pinfunction "P2_6") (pintype "bidirectional"))
      (node (ref "RN101") (pin "5") (pinfunction "1_5") (pintype "passive"))
    )
    (net (code "23") (name "DRV_1_SEG_D") (class "Default")
      (node (ref "IC101") (pin "7") (pinfunction "P3_7") (pintype "bidirectional"))
      (node (ref "RN101") (pin "7") (pinfunction "1_7") (pintype "passive"))
    )
    (net (code "24") (name "DRV_1_SEG_E") (class "Default")
      (node (ref "IC101") (pin "9") (pinfunction "P4_9") (pintype "bidirectional"))
      (node (ref "RN102") (pin "1") (pinfunction "1_1") (pintype "passive"))
    )
    (net (code "25") (name "DRV_1_SEG_F") (class "Default")
      (node (ref "IC101") (pin "10") (pinfunction "P5_10") (pintype "bidirectional"))
      (node (ref "RN102") (pin "3") (pinfunction "1_3") (pintype "passive"))
    )
    (net (code "26") (name "DRV_1_SEG_G") (class "Default")
      (node (ref "IC101") (pin "11") (pinfunction "P6_11") (pintype "bidirectional"))
      (node (ref "RN102") (pin "5") (pinfunction "1_5") (pintype "passive"))
    )
    (net (code "27") (name "DRV_1_SEG_H") (class "Default")
      (node (ref "IC101") (pin "12") (pinfunction "P7_12") (pintype "bidirectional"))
      (node (ref "RN102") (pin "7") (pinfunction "1_7") (pintype "passive"))
    )
    (net (code "28") (name "DRV_1_SEG_RA") (class "Default")
      (node (ref "DIS101") (pin "7") (pinfunction "A1_7") (pintype "passive"))
      (node (ref "RN101") (pin "2") (pinfunction "2_2") (pintype "passive"))
    )
    (net (code "29") (name "DRV_1_SEG_RB") (class "Default")
      (node (ref "DIS101") (pin "6") (pinfunction "B1_6") (pintype "passive"))
      (node (ref "RN101") (pin "4") (pinfunction "2_4") (pintype "passive"))
    )
    (net (code "30") (name "DRV_1_SEG_RC") (class "Default")
      (node (ref "DIS101") (pin "4") (pinfunction "C1_4") (pintype "passive"))
      (node (ref "RN101") (pin "6") (pinfunction "2_6") (pintype "passive"))
    )
    (net (code "31") (name "DRV_1_SEG_RD") (class "Default")
      (node (ref "DIS101") (pin "2") (pinfunction "D1_2") (pintype "passive"))
      (node (ref "RN101") (pin "8") (pinfunction "2_8") (pintype "passive"))
    )
    (net (code "32") (name "DRV_1_SEG_RE") (class "Default")
      (node (ref "DIS101") (pin "1") (pinfunction "E1_1") (pintype "passive"))
      (node (ref "RN102") (pin "2") (pinfunction "2_2") (pintype "passive"))
    )
    (net (code "33") (name "DRV_1_SEG_RF") (class "Default")
      (node (ref "DIS101") (pin "10") (pinfunction "F1_10") (pintype "passive"))
      (node (ref "RN102") (pin "4") (pinfunction "2_4") (pintype "passive"))
    )
    (net (code "34") (name "DRV_1_SEG_RG") (class "Default")
      (node (ref "DIS101") (pin "9") (pinfunction "G1_9") (pintype "passive"))
      (node (ref "RN102") (pin "6") (pinfunction "2_6") (pintype "passive"))
    )
    (net (code "35") (name "DRV_1_SEG_RH") (class "Default")
      (node (ref "DIS101") (pin "5") (pinfunction "DP1_5") (pintype "passive"))
      (node (ref "RN102") (pin "8") (pinfunction "2_8") (pintype "passive"))
    )
    (net (code "36") (name "DRV_2_SEG_A") (class "Default")
      (node (ref "IC201") (pin "4") (pinfunction "P0_4") (pintype "bidirectional"))
      (node (ref "RN201") (pin "1") (pinfunction "1_1") (pintype "passive"))
    )
    (net (code "37") (name "DRV_2_SEG_B") (class "Default")
      (node (ref "IC201") (pin "5") (pinfunction "P1_5") (pintype "bidirectional"))
      (node (ref "RN201") (pin "3") (pinfunction "1_3") (pintype "passive"))
    )
    (net (code "38") (name "DRV_2_SEG_C") (class "Default")
      (node (ref "IC201") (pin "6") (pinfunction "P2_6") (pintype "bidirectional"))
      (node (ref "RN201") (pin "5") (pinfunction "1_5") (pintype "passive"))
    )
    (net (code "39") (name "DRV_2_SEG_D") (class "Default")
      (node (ref "IC201") (pin "7") (pinfunction "P3_7") (pintype "bidirectional"))
      (node (ref "RN201") (pin "7") (pinfunction "1_7") (pintype "passive"))
    )
    (net (code "40") (name "DRV_2_SEG_E") (class "Default")
      (node (ref "IC201") (pin "9") (pinfunction "P4_9") (pintype "bidirectional"))
      (node (ref "RN202") (pin "1") (pinfunction "1_1") (pintype "passive"))
    )
    (net (code "41") (name "DRV_2_SEG_F") (class "Default")
      (node (ref "IC201") (pin "10") (pinfunction "P5_10") (pintype "bidirectional"))
      (node (ref "RN202") (pin "3") (pinfunction "1_3") (pintype "passive"))
    )
    (net (code "42") (name "DRV_2_SEG_G") (class "Default")
      (node (ref "IC201") (pin "11") (pinfunction "P6_11") (pintype "bidirectional"))
      (node (ref "RN202") (pin "5") (pinfunction "1_5") (pintype "passive"))
    )
    (net (code "43") (name "DRV_2_SEG_H") (class "Default")
      (node (ref "IC201") (pin "12") (pinfunction "P7_12") (pintype "bidirectional"))
      (node (ref "RN202") (pin "7") (pinfunction "1_7") (pintype "passive"))
    )
    (net (code "44") (name "DRV_2_SEG_RA") (class "Default")
      (node (ref "DIS201") (pin "7") (pinfunction "A1_7") (pintype "passive"))
      (node (ref "RN201") (pin "2") (pinfunction "2_2") (pintype "passive"))
    )
    (net (code "45") (name "DRV_2_SEG_RB") (class "Default")
      (node (ref "DIS201") (pin "6") (pinfunction "B1_6") (pintype "passive"))
      (node (ref "RN201") (pin "4") (pinfunction "2_4") (pintype "passive"))
    )
    (net (code "46") (name "DRV_2_SEG_RC") (class "Default")
      (node (ref "DIS201") (pin "4") (pinfunction "C1_4") (pintype "passive"))
      (node (ref "RN201") (pin "6") (pinfunction "2_6") (pintype "passive"))
    )
    (net (code "47") (name "DRV_2_SEG_RD") (class "Default")
      (node (ref "DIS201") (pin "2") (pinfunction "D1_2") (pintype "passive"))
      (node (ref "RN201") (pin "8") (pinfunction "2_8") (pintype "passive"))
    )
    (net (code "48") (name "DRV_2_SEG_RE") (class "Default")
      (node (ref "DIS201") (pin "1") (pinfunction "E1_1") (pintype "passive"))
      (node (ref "RN202") (pin "2") (pinfunction "2_2") (pintype "passive"))
    )
    (net (code "49") (name "DRV_2_SEG_RF") (class "Default")
      (node (ref "DIS201") (pin "10") (pinfunction "F1_10") (pintype "passive"))
      (node (ref "RN202") (pin "4") (pinfunction "2_4") (pintype "passive"))
    )
    (net (code "50") (name "DRV_2_SEG_RG") (class "Default")
      (node (ref "DIS201") (pin "9") (pinfunction "G1_9") (pintype "passive"))
      (node (ref "RN202") (pin "6") (pinfunction "2_6") (pintype "passive"))
    )
    (net (code "51") (name "DRV_2_SEG_RH") (class "Default")
      (node (ref "DIS201") (pin "5") (pinfunction "DP1_5") (pintype "passive"))
      (node (ref "RN202") (pin "8") (pinfunction "2_8") (pintype "passive"))
    )
    (net (code "52") (name "DRV_3_SEG_A") (class "Default")
      (node (ref "IC301") (pin "4") (pinfunction "P0_4") (pintype "bidirectional"))
      (node (ref "RN301") (pin "1") (pinfunction "1_1") (pintype "passive"))
    )
    (net (code "53") (name "DRV_3_SEG_B") (class "Default")
      (node (ref "IC301") (pin "5") (pinfunction "P1_5") (pintype "bidirectional"))
      (node (ref "RN301") (pin "3") (pinfunction "1_3") (pintype "passive"))
    )
    (net (code "54") (name "DRV_3_SEG_C") (class "Default")
      (node (ref "IC301") (pin "6") (pinfunction "P2_6") (pintype "bidirectional"))
      (node (ref "RN301") (pin "5") (pinfunction "1_5") (pintype "passive"))
    )
    (net (code "55") (name "DRV_3_SEG_D") (class "Default")
      (node (ref "IC301") (pin "7") (pinfunction "P3_7") (pintype "bidirectional"))
      (node (ref "RN301") (pin "7") (pinfunction "1_7") (pintype "passive"))
    )
    (net (code "56") (name "DRV_3_SEG_E") (class "Default")
      (node (ref "IC301") (pin "9") (pinfunction "P4_9") (pintype "bidirectional"))
      (node (ref "RN302") (pin "1") (pinfunction "1_1") (pintype "passive"))
    )
    (net (code "57") (name "DRV_3_SEG_F") (class "Default")
      (node (ref "IC301") (pin "10") (pinfunction "P5_10") (pintype "bidirectional"))
      (node (ref "RN302") (pin "3") (pinfunction "1_3") (pintype "passive"))
    )
    (net (code "58") (name "DRV_3_SEG_G") (class "Default")
      (node (ref "IC301") (pin "11") (pinfunction "P6_11") (pintype "bidirectional"))
      (node (ref "RN302") (pin "5") (pinfunction "1_5") (pintype "passive"))
    )
    (net (code "59") (name "DRV_3_SEG_H") (class "Default")
      (node (ref "IC301") (pin "12") (pinfunction "P7_12") (pintype "bidirectional"))
      (node (ref "RN302") (pin "7") (pinfunction "1_7") (pintype "passive"))
    )
    (net (code "60") (name "DRV_3_SEG_RA") (class "Default")
      (node (ref "DIS301") (pin "7") (pinfunction "A1_7") (pintype "passive"))
      (node (ref "RN301") (pin "2") (pinfunction "2_2") (pintype "passive"))
    )
    (net (code "61") (name "DRV_3_SEG_RB") (class "Default")
      (node (ref "DIS301") (pin "6") (pinfunction "B1_6") (pintype "passive"))
      (node (ref "RN301") (pin "4") (pinfunction "2_4") (pintype "passive"))
    )
    (net (code "62") (name "DRV_3_SEG_RC") (class "Default")
      (node (ref "DIS301") (pin "4") (pinfunction "C1_4") (pintype "passive"))
      (node (ref "RN301") (pin "6") (pinfunction "2_6") (pintype "passive"))
    )
    (net (code "63") (name "DRV_3_SEG_RD") (class "Default")
      (node (ref "DIS301") (pin "2") (pinfunction "D1_2") (pintype "passive"))
      (node (ref "RN301") (pin "8") (pinfunction "2_8") (pintype "passive"))
    )
    (net (code "64") (name "DRV_3_SEG_RE") (class "Default")
      (node (ref "DIS301") (pin "1") (pinfunction "E1_1") (pintype "passive"))
      (node (ref "RN302") (pin "2") (pinfunction "2_2") (pintype "passive"))
    )
    (net (code "65") (name "DRV_3_SEG_RF") (class "Default")
      (node (ref "DIS301") (pin "10") (pinfunction "F1_10") (pintype "passive"))
      (node (ref "RN302") (pin "4") (pinfunction "2_4") (pintype "passive"))
    )
    (net (code "66") (name "DRV_3_SEG_RG") (class "Default")
      (node (ref "DIS301") (pin "9") (pinfunction "G1_9") (pintype "passive"))
      (node (ref "RN302") (pin "6") (pinfunction "2_6") (pintype "passive"))
    )
    (net (code "67") (name "DRV_3_SEG_RH") (class "Default")
      (node (ref "DIS301") (pin "5") (pinfunction "DP1_5") (pintype "passive"))
      (node (ref "RN302") (pin "8") (pinfunction "2_8") (pintype "passive"))
    )
    (net (code "68") (name "DRV_4_SEG_A") (class "Default")
      (node (ref "IC401") (pin "4") (pinfunction "P0_4") (pintype "bidirectional"))
      (node (ref "RN401") (pin "1") (pinfunction "1_1") (pintype "passive"))
    )
    (net (code "69") (name "DRV_4_SEG_B") (class "Default")
      (node (ref "IC401") (pin "5") (pinfunction "P1_5") (pintype "bidirectional"))
      (node (ref "RN401") (pin "3") (pinfunction "1_3") (pintype "passive"))
    )
    (net (code "70") (name "DRV_4_SEG_C") (class "Default")
      (node (ref "IC401") (pin "6") (pinfunction "P2_6") (pintype "bidirectional"))
      (node (ref "RN401") (pin "5") (pinfunction "1_5") (pintype "passive"))
    )
    (net (code "71") (name "DRV_4_SEG_D") (class "Default")
      (node (ref "IC401") (pin "7") (pinfunction "P3_7") (pintype "bidirectional"))
      (node (ref "RN401") (pin "7") (pinfunction "1_7") (pintype "passive"))
    )
    (net (code "72") (name "DRV_4_SEG_E") (class "Default")
      (node (ref "IC401") (pin "9") (pinfunction "P4_9") (pintype "bidirectional"))
      (node (ref "RN402") (pin "1") (pinfunction "1_1") (pintype "passive"))
    )
    (net (code "73") (name "DRV_4_SEG_F") (class "Default")
      (node (ref "IC401") (pin "10") (pinfunction "P5_10") (pintype "bidirectional"))
      (node (ref "RN402") (pin "3") (pinfunction "1_3") (pintype "passive"))
    )
    (net (code "74") (name "DRV_4_SEG_G") (class "Default")
      (node (ref "IC401") (pin "11") (pinfunction "P6_11") (pintype "bidirectional"))
      (node (ref "RN402") (pin "5") (pinfunction "1_5") (pintype "passive"))
    )
    (net (code "75") (name "DRV_4_SEG_H") (class "Default")
      (node (ref "IC401") (pin "12") (pinfunction "P7_12") (pintype "bidirectional"))
      (node (ref "RN402") (pin "7") (pinfunction "1_7") (pintype "passive"))
    )
    (net (code "76") (name "DRV_4_SEG_RA") (class "Default")
      (node (ref "DIS401") (pin "7") (pinfunction "A1_7") (pintype "passive"))
      (node (ref "RN401") (pin "2") (pinfunction "2_2") (pintype "passive"))
    )
    (net (code "77") (name "DRV_4_SEG_RB") (class "Default")
      (node (ref "DIS401") (pin "6") (pinfunction "B1_6") (pintype "passive"))
      (node (ref "RN401") (pin "4") (pinfunction "2_4") (pintype "passive"))
    )
    (net (code "78") (name "DRV_4_SEG_RC") (class "Default")
      (node (ref "DIS401") (pin "4") (pinfunction "C1_4") (pintype "passive"))
      (node (ref "RN401") (pin "6") (pinfunction "2_6") (pintype "passive"))
    )
    (net (code "79") (name "DRV_4_SEG_RD") (class "Default")
      (node (ref "DIS401") (pin "2") (pinfunction "D1_2") (pintype "passive"))
      (node (ref "RN401") (pin "8") (pinfunction "2_8") (pintype "passive"))
    )
    (net (code "80") (name "DRV_4_SEG_RE") (class "Default")
      (node (ref "DIS401") (pin "1") (pinfunction "E1_1") (pintype "passive"))
      (node (ref "RN402") (pin "2") (pinfunction "2_2") (pintype "passive"))
    )
    (net (code "81") (name "DRV_4_SEG_RF") (class "Default")
      (node (ref "DIS401") (pin "10") (pinfunction "F1_10") (pintype "passive"))
      (node (ref "RN402") (pin "4") (pinfunction "2_4") (pintype "passive"))
    )
    (net (code "82") (name "DRV_4_SEG_RG") (class "Default")
      (node (ref "DIS401") (pin "9") (pinfunction "G1_9") (pintype "passive"))
      (node (ref "RN402") (pin "6") (pinfunction "2_6") (pintype "passive"))
    )
    (net (code "83") (name "DRV_4_SEG_RH") (class "Default")
      (node (ref "DIS401") (pin "5") (pinfunction "DP1_5") (pintype "passive"))
      (node (ref "RN402") (pin "8") (pinfunction "2_8") (pintype "passive"))
    )
    (net (code "84") (name "DRV_5_SEG_A") (class "Default")
      (node (ref "IC501") (pin "4") (pinfunction "P0_4") (pintype "bidirectional"))
      (node (ref "RN501") (pin "1") (pinfunction "1_1") (pintype "passive"))
    )
    (net (code "85") (name "DRV_5_SEG_B") (class "Default")
      (node (ref "IC501") (pin "5") (pinfunction "P1_5") (pintype "bidirectional"))
      (node (ref "RN501") (pin "3") (pinfunction "1_3") (pintype "passive"))
    )
    (net (code "86") (name "DRV_5_SEG_C") (class "Default")
      (node (ref "IC501") (pin "6") (pinfunction "P2_6") (pintype "bidirectional"))
      (node (ref "RN501") (pin "5") (pinfunction "1_5") (pintype "passive"))
    )
    (net (code "87") (name "DRV_5_SEG_D") (class "Default")
      (node (ref "IC501") (pin "7") (pinfunction "P3_7") (pintype "bidirectional"))
      (node (ref "RN501") (pin "7") (pinfunction "1_7") (pintype "passive"))
    )
    (net (code "88") (name "DRV_5_SEG_E") (class "Default")
      (node (ref "IC501") (pin "9") (pinfunction "P4_9") (pintype "bidirectional"))
      (node (ref "RN502") (pin "1") (pinfunction "1_1") (pintype "passive"))
    )
    (net (code "89") (name "DRV_5_SEG_F") (class "Default")
      (node (ref "IC501") (pin "10") (pinfunction "P5_10") (pintype "bidirectional"))
      (node (ref "RN502") (pin "3") (pinfunction "1_3") (pintype "passive"))
    )
    (net (code "90") (name "DRV_5_SEG_G") (class "Default")
      (node (ref "IC501") (pin "11") (pinfunction "P6_11") (pintype "bidirectional"))
      (node (ref "RN502") (pin "5") (pinfunction "1_5") (pintype "passive"))
    )
    (net (code "91") (name "DRV_5_SEG_H") (class "Default")
      (node (ref "IC501") (pin "12") (pinfunction "P7_12") (pintype "bidirectional"))
      (node (ref "RN502") (pin "7") (pinfunction "1_7") (pintype "passive"))
    )
    (net (code "92") (name "DRV_5_SEG_RA") (class "Default")
      (node (ref "DIS501") (pin "7") (pinfunction "A1_7") (pintype "passive"))
      (node (ref "RN501") (pin "2") (pinfunction "2_2") (pintype "passive"))
    )
    (net (code "93") (name "DRV_5_SEG_RB") (class "Default")
      (node (ref "DIS501") (pin "6") (pinfunction "B1_6") (pintype "passive"))
      (node (ref "RN501") (pin "4") (pinfunction "2_4") (pintype "passive"))
    )
    (net (code "94") (name "DRV_5_SEG_RC") (class "Default")
      (node (ref "DIS501") (pin "4") (pinfunction "C1_4") (pintype "passive"))
      (node (ref "RN501") (pin "6") (pinfunction "2_6") (pintype "passive"))
    )
    (net (code "95") (name "DRV_5_SEG_RD") (class "Default")
      (node (ref "DIS501") (pin "2") (pinfunction "D1_2") (pintype "passive"))
      (node (ref "RN501") (pin "8") (pinfunction "2_8") (pintype "passive"))
    )
    (net (code "96") (name "DRV_5_SEG_RE") (class "Default")
      (node (ref "DIS501") (pin "1") (pinfunction "E1_1") (pintype "passive"))
      (node (ref "RN502") (pin "2") (pinfunction "2_2") (pintype "passive"))
    )
    (net (code "97") (name "DRV_5_SEG_RF") (class "Default")
      (node (ref "DIS501") (pin "10") (pinfunction "F1_10") (pintype "passive"))
      (node (ref "RN502") (pin "4") (pinfunction "2_4") (pintype "passive"))
    )
    (net (code "98") (name "DRV_5_SEG_RG") (class "Default")
      (node (ref "DIS501") (pin "9") (pinfunction "G1_9") (pintype "passive"))
      (node (ref "RN502") (pin "6") (pinfunction "2_6") (pintype "passive"))
    )
    (net (code "99") (name "DRV_5_SEG_RH") (class "Default")
      (node (ref "DIS501") (pin "5") (pinfunction "DP1_5") (pintype "passive"))
      (node (ref "RN502") (pin "8") (pinfunction "2_8") (pintype "passive"))
    )
    (net (code "100") (name "DRV_6_SEG_A") (class "Default")
      (node (ref "IC601") (pin "4") (pinfunction "P0_4") (pintype "bidirectional"))
      (node (ref "RN601") (pin "1") (pinfunction "1_1") (pintype "passive"))
    )
    (net (code "101") (name "DRV_6_SEG_B") (class "Default")
      (node (ref "IC601") (pin "5") (pinfunction "P1_5") (pintype "bidirectional"))
      (node (ref "RN601") (pin "3") (pinfunction "1_3") (pintype "passive"))
    )
    (net (code "102") (name "DRV_6_SEG_C") (class "Default")
      (node (ref "IC601") (pin "6") (pinfunction "P2_6") (pintype "bidirectional"))
      (node (ref "RN601") (pin "5") (pinfunction "1_5") (pintype "passive"))
    )
    (net (code "103") (name "DRV_6_SEG_D") (class "Default")
      (node (ref "IC601") (pin "7") (pinfunction "P3_7") (pintype "bidirectional"))
      (node (ref "RN601") (pin "7") (pinfunction "1_7") (pintype "passive"))
    )
    (net (code "104") (name "DRV_6_SEG_E") (class "Default")
      (node (ref "IC601") (pin "9") (pinfunction "P4_9") (pintype "bidirectional"))
      (node (ref "RN602") (pin "1") (pinfunction "1_1") (pintype "passive"))
    )
    (net (code "105") (name "DRV_6_SEG_F") (class "Default")
      (node (ref "IC601") (pin "10") (pinfunction "P5_10") (pintype "bidirectional"))
      (node (ref "RN602") (pin "3") (pinfunction "1_3") (pintype "passive"))
    )
    (net (code "106") (name "DRV_6_SEG_G") (class "Default")
      (node (ref "IC601") (pin "11") (pinfunction "P6_11") (pintype "bidirectional"))
      (node (ref "RN602") (pin "5") (pinfunction "1_5") (pintype "passive"))
    )
    (net (code "107") (name "DRV_6_SEG_H") (class "Default")
      (node (ref "IC601") (pin "12") (pinfunction "P7_12") (pintype "bidirectional"))
      (node (ref "RN602") (pin "7") (pinfunction "1_7") (pintype "passive"))
    )
    (net (code "108") (name "DRV_6_SEG_RA") (class "Default")
      (node (ref "DIS601") (pin "7") (pinfunction "A1_7") (pintype "passive"))
      (node (ref "RN601") (pin "2") (pinfunction "2_2") (pintype "passive"))
    )
    (net (code "109") (name "DRV_6_SEG_RB") (class "Default")
      (node (ref "DIS601") (pin "6") (pinfunction "B1_6") (pintype "passive"))
      (node (ref "RN601") (pin "4") (pinfunction "2_4") (pintype "passive"))
    )
    (net (code "110") (name "DRV_6_SEG_RC") (class "Default")
      (node (ref "DIS601") (pin "4") (pinfunction "C1_4") (pintype "passive"))
      (node (ref "RN601") (pin "6") (pinfunction "2_6") (pintype "passive"))
    )
    (net (code "111") (name "DRV_6_SEG_RD") (class "Default")
      (node (ref "DIS601") (pin "2") (pinfunction "D1_2") (pintype "passive"))
      (node (ref "RN601") (pin "8") (pinfunction "2_8") (pintype "passive"))
    )
    (net (code "112") (name "DRV_6_SEG_RE") (class "Default")
      (node (ref "DIS601") (pin "1") (pinfunction "E1_1") (pintype "passive"))
      (node (ref "RN602") (pin "2") (pinfunction "2_2") (pintype "passive"))
    )
    (net (code "113") (name "DRV_6_SEG_RF") (class "Default")
      (node (ref "DIS601") (pin "10") (pinfunction "F1_10") (pintype "passive"))
      (node (ref "RN602") (pin "4") (pinfunction "2_4") (pintype "passive"))
    )
    (net (code "114") (name "DRV_6_SEG_RG") (class "Default")
      (node (ref "DIS601") (pin "9") (pinfunction "G1_9") (pintype "passive"))
      (node (ref "RN602") (pin "6") (pinfunction "2_6") (pintype "passive"))
    )
    (net (code "115") (name "DRV_6_SEG_RH") (class "Default")
      (node (ref "DIS601") (pin "5") (pinfunction "DP1_5") (pintype "passive"))
      (node (ref "RN602") (pin "8") (pinfunction "2_8") (pintype "passive"))
    )
    (net (code "116") (name "DRV_7_SEG_A") (class "Default")
      (node (ref "IC701") (pin "4") (pinfunction "P0_4") (pintype "bidirectional"))
      (node (ref "RN701") (pin "1") (pinfunction "1_1") (pintype "passive"))
    )
    (net (code "117") (name "DRV_7_SEG_B") (class "Default")
      (node (ref "IC701") (pin "5") (pinfunction "P1_5") (pintype "bidirectional"))
      (node (ref "RN701") (pin "3") (pinfunction "1_3") (pintype "passive"))
    )
    (net (code "118") (name "DRV_7_SEG_C") (class "Default")
      (node (ref "IC701") (pin "6") (pinfunction "P2_6") (pintype "bidirectional"))
      (node (ref "RN701") (pin "5") (pinfunction "1_5") (pintype "passive"))
    )
    (net (code "119") (name "DRV_7_SEG_D") (class "Default")
      (node (ref "IC701") (pin "7") (pinfunction "P3_7") (pintype "bidirectional"))
      (node (ref "RN701") (pin "7") (pinfunction "1_7") (pintype "passive"))
    )
    (net (code "120") (name "DRV_7_SEG_E") (class "Default")
      (node (ref "IC701") (pin "9") (pinfunction "P4_9") (pintype "bidirectional"))
      (node (ref "RN702") (pin "1") (pinfunction "1_1") (pintype "passive"))
    )
    (net (code "121") (name "DRV_7_SEG_F") (class "Default")
      (node (ref "IC701") (pin "10") (pinfunction "P5_10") (pintype "bidirectional"))
      (node (ref "RN702") (pin "3") (pinfunction "1_3") (pintype "passive"))
    )
    (net (code "122") (name "DRV_7_SEG_G") (class "Default")
      (node (ref "IC701") (pin "11") (pinfunction "P6_11") (pintype "bidirectional"))
      (node (ref "RN702") (pin "5") (pinfunction "1_5") (pintype "passive"))
    )
    (net (code "123") (name "DRV_7_SEG_H") (class "Default")
      (node (ref "IC701") (pin "12") (pinfunction "P7_12") (pintype "bidirectional"))
      (node (ref "RN702") (pin "7") (pinfunction "1_7") (pintype "passive"))
    )
    (net (code "124") (name "DRV_7_SEG_RA") (class "Default")
      (node (ref "DIS701") (pin "7") (pinfunction "A1_7") (pintype "passive"))
      (node (ref "RN701") (pin "2") (pinfunction "2_2") (pintype "passive"))
    )
    (net (code "125") (name "DRV_7_SEG_RB") (class "Default")
      (node (ref "DIS701") (pin "6") (pinfunction "B1_6") (pintype "passive"))
      (node (ref "RN701") (pin "4") (pinfunction "2_4") (pintype "passive"))
    )
    (net (code "126") (name "DRV_7_SEG_RC") (class "Default")
      (node (ref "DIS701") (pin "4") (pinfunction "C1_4") (pintype "passive"))
      (node (ref "RN701") (pin "6") (pinfunction "2_6") (pintype "passive"))
    )
    (net (code "127") (name "DRV_7_SEG_RD") (class "Default")
      (node (ref "DIS701") (pin "2") (pinfunction "D1_2") (pintype "passive"))
      (node (ref "RN701") (pin "8") (pinfunction "2_8") (pintype "passive"))
    )
    (net (code "128") (name "DRV_7_SEG_RE") (class "Default")
      (node (ref "DIS701") (pin "1") (pinfunction "E1_1") (pintype "passive"))
      (node (ref "RN702") (pin "2") (pinfunction "2_2") (pintype "passive"))
    )
    (net (code "129") (name "DRV_7_SEG_RF") (class "Default")
      (node (ref "DIS701") (pin "10") (pinfunction "F1_10") (pintype "passive"))
      (node (ref "RN702") (pin "4") (pinfunction "2_4") (pintype "passive"))
    )
    (net (code "130") (name "DRV_7_SEG_RG") (class "Default")
      (node (ref "DIS701") (pin "9") (pinfunction "G1_9") (pintype "passive"))
      (node (ref "RN702") (pin "6") (pinfunction "2_6") (pintype "passive"))
    )
    (net (code "131") (name "DRV_7_SEG_RH") (class "Default")
      (node (ref "DIS701") (pin "5") (pinfunction "DP1_5") (pintype "passive"))
      (node (ref "RN702") (pin "8") (pinfunction "2_8") (pintype "passive"))
    )
    (net (code "132") (name "DRV_8_SEG_A") (class "Default")
      (node (ref "IC801") (pin "4") (pinfunction "P0_4") (pintype "bidirectional"))
      (node (ref "RN801") (pin "1") (pinfunction "1_1") (pintype "passive"))
    )
    (net (code "133") (name "DRV_8_SEG_B") (class "Default")
      (node (ref "IC801") (pin "5") (pinfunction "P1_5") (pintype "bidirectional"))
      (node (ref "RN801") (pin "3") (pinfunction "1_3") (pintype "passive"))
    )
    (net (code "134") (name "DRV_8_SEG_C") (class "Default")
      (node (ref "IC801") (pin "6") (pinfunction "P2_6") (pintype "bidirectional"))
      (node (ref "RN801") (pin "5") (pinfunction "1_5") (pintype "passive"))
    )
    (net (code "135") (name "DRV_8_SEG_D") (class "Default")
      (node (ref "IC801") (pin "7") (pinfunction "P3_7") (pintype "bidirectional"))
      (node (ref "RN801") (pin "7") (pinfunction "1_7") (pintype "passive"))
    )
    (net (code "136") (name "DRV_8_SEG_E") (class "Default")
      (node (ref "IC801") (pin "9") (pinfunction "P4_9") (pintype "bidirectional"))
      (node (ref "RN802") (pin "1") (pinfunction "1_1") (pintype "passive"))
    )
    (net (code "137") (name "DRV_8_SEG_F") (class "Default")
      (node (ref "IC801") (pin "10") (pinfunction "P5_10") (pintype "bidirectional"))
      (node (ref "RN802") (pin "3") (pinfunction "1_3") (pintype "passive"))
    )
    (net (code "138") (name "DRV_8_SEG_G") (class "Default")
      (node (ref "IC801") (pin "11") (pinfunction "P6_11") (pintype "bidirectional"))
      (node (ref "RN802") (pin "5") (pinfunction "1_5") (pintype "passive"))
    )
    (net (code "139") (name "DRV_8_SEG_H") (class "Default")
      (node (ref "IC801") (pin "12") (pinfunction "P7_12") (pintype "bidirectional"))
      (node (ref "RN802") (pin "7") (pinfunction "1_7") (pintype "passive"))
    )
    (net (code "140") (name "DRV_8_SEG_RA") (class "Default")
      (node (ref "DIS801") (pin "7") (pinfunction "A1_7") (pintype "passive"))
      (node (ref "RN801") (pin "2") (pinfunction "2_2") (pintype "passive"))
    )
    (net (code "141") (name "DRV_8_SEG_RB") (class "Default")
      (node (ref "DIS801") (pin "6") (pinfunction "B1_6") (pintype "passive"))
      (node (ref "RN801") (pin "4") (pinfunction "2_4") (pintype "passive"))
    )
    (net (code "142") (name "DRV_8_SEG_RC") (class "Default")
      (node (ref "DIS801") (pin "4") (pinfunction "C1_4") (pintype "passive"))
      (node (ref "RN801") (pin "6") (pinfunction "2_6") (pintype "passive"))
    )
    (net (code "143") (name "DRV_8_SEG_RD") (class "Default")
      (node (ref "DIS801") (pin "2") (pinfunction "D1_2") (pintype "passive"))
      (node (ref "RN801") (pin "8") (pinfunction "2_8") (pintype "passive"))
    )
    (net (code "144") (name "DRV_8_SEG_RE") (class "Default")
      (node (ref "DIS801") (pin "1") (pinfunction "E1_1") (pintype "passive"))
      (node (ref "RN802") (pin "2") (pinfunction "2_2") (pintype "passive"))
    )
    (net (code "145") (name "DRV_8_SEG_RF") (class "Default")
      (node (ref "DIS801") (pin "10") (pinfunction "F1_10") (pintype "passive"))
      (node (ref "RN802") (pin "4") (pinfunction "2_4") (pintype "passive"))
    )
    (net (code "146") (name "DRV_8_SEG_RG") (class "Default")
      (node (ref "DIS801") (pin "9") (pinfunction "G1_9") (pintype "passive"))
      (node (ref "RN802") (pin "6") (pinfunction "2_6") (pintype "passive"))
    )
    (net (code "147") (name "DRV_8_SEG_RH") (class "Default")
      (node (ref "DIS801") (pin "5") (pinfunction "DP1_5") (pintype "passive"))
      (node (ref "RN802") (pin "8") (pinfunction "2_8") (pintype "passive"))
    )
    (net (code "148") (name "DRV_9_LED_1") (class "Default")
      (node (ref "IC901") (pin "4") (pinfunction "P0_4") (pintype "bidirectional"))
      (node (ref "R901") (pin "1") (pinfunction "1_1") (pintype "passive"))
      (node (ref "R902") (pin "1") (pinfunction "1_1") (pintype "passive"))
      (node (ref "R903") (pin "1") (pinfunction "1_1") (pintype "passive"))
    )
    (net (code "149") (name "DRV_9_LED_2") (class "Default")
      (node (ref "IC901") (pin "5") (pinfunction "P1_5") (pintype "bidirectional"))
      (node (ref "R904") (pin "1") (pinfunction "1_1") (pintype "passive"))
    )
    (net (code "150") (name "DRV_9_LED_3") (class "Default")
      (node (ref "IC901") (pin "6") (pinfunction "P2_6") (pintype "bidirectional"))
      (node (ref "R905") (pin "1") (pinfunction "1_1") (pintype "passive"))
    )
    (net (code "151") (name "DRV_9_LED_4") (class "Default")
      (node (ref "IC901") (pin "7") (pinfunction "P3_7") (pintype "bidirectional"))
      (node (ref "R906") (pin "1") (pinfunction "1_1") (pintype "passive"))
    )
    (net (code "152") (name "DRV_9_LED_5") (class "Default")
      (node (ref "IC901") (pin "9") (pinfunction "P4_9") (pintype "bidirectional"))
      (node (ref "R907") (pin "1") (pinfunction "1_1") (pintype "passive"))
    )
    (net (code "153") (name "DRV_9_LED_6") (class "Default")
      (node (ref "IC901") (pin "10") (pinfunction "P5_10") (pintype "bidirectional"))
      (node (ref "R908") (pin "1") (pinfunction "1_1") (pintype "passive"))
    )
    (net (code "154") (name "DRV_9_LED_7") (class "Default")
      (node (ref "IC901") (pin "11") (pinfunction "P6_11") (pintype "bidirectional"))
      (node (ref "R909") (pin "1") (pinfunction "1_1") (pintype "passive"))
    )
    (net (code "155") (name "DRV_9_LED_8") (class "Default")
      (node (ref "IC901") (pin "12") (pinfunction "P7_12") (pintype "bidirectional"))
      (node (ref "R910") (pin "1") (pinfunction "1_1") (pintype "passive"))
    )
    (net (code "156") (name "DRV_9_LED_R1A") (class "Default")
      (node (ref "LED902") (pin "C") (pinfunction "C_C") (pintype "passive"))
      (node (ref "R902") (pin "2") (pinfunction "2_2") (pintype "passive"))
    )
    (net (code "157") (name "DRV_9_LED_R1B") (class "Default")
      (node (ref "LED903") (pin "C") (pinfunction "C_C") (pintype "passive"))
      (node (ref "R903") (pin "2") (pinfunction "2_2") (pintype "passive"))
    )
    (net (code "158") (name "DRV_9_LED_R1C") (class "Default")
      (node (ref "LED901") (pin "C") (pinfunction "C_C") (pintype "passive"))
      (node (ref "R901") (pin "2") (pinfunction "2_2") (pintype "passive"))
    )
    (net (code "159") (name "DRV_9_LED_R2") (class "Default")
      (node (ref "LED904") (pin "C") (pinfunction "C_C") (pintype "passive"))
      (node (ref "R904") (pin "2") (pinfunction "2_2") (pintype "passive"))
    )
    (net (code "160") (name "DRV_9_LED_R3") (class "Default")
      (node (ref "LED905") (pin "C") (pinfunction "C_C") (pintype "passive"))
      (node (ref "R905") (pin "2") (pinfunction "2_2") (pintype "passive"))
    )
    (net (code "161") (name "DRV_9_LED_R4") (class "Default")
      (node (ref "LED906") (pin "C") (pinfunction "C_C") (pintype "passive"))
      (node (ref "R906") (pin "2") (pinfunction "2_2") (pintype "passive"))
    )
    (net (code "162") (name "DRV_9_LED_R5") (class "Default")
      (node (ref "LED907") (pin "C") (pinfunction "C_C") (pintype "passive"))
      (node (ref "R907") (pin "2") (pinfunction "2_2") (pintype "passive"))
    )
    (net (code "163") (name "DRV_9_LED_R6") (class "Default")
      (node (ref "LED908") (pin "C") (pinfunction "C_C") (pintype "passive"))
      (node (ref "R908") (pin "2") (pinfunction "2_2") (pintype "passive"))
    )
    (net (code "164") (name "DRV_9_LED_R7") (class "Default")
      (node (ref "LED909") (pin "C") (pinfunction "C_C") (pintype "passive"))
      (node (ref "R909") (pin "2") (pinfunction "2_2") (pintype "passive"))
    )
    (net (code "165") (name "DRV_9_LED_R8") (class "Default")
      (node (ref "LED910") (pin "C") (pinfunction "C_C") (pintype "passive"))
      (node (ref "R910") (pin "2") (pinfunction "2_2") (pintype "passive"))
    )
    (net (code "166") (name "DRV_ANODE_1") (class "Default")
      (node (ref "DIS101") (pin "3") (pinfunction "COM1_3") (pintype "passive"))
      (node (ref "DIS101") (pin "8") (pinfunction "COM1_8") (pintype "passive"))
      (node (ref "DIS201") (pin "3") (pinfunction "COM1_3") (pintype "passive"))
      (node (ref "DIS201") (pin "8") (pinfunction "COM1_8") (pintype "passive"))
      (node (ref "DIS301") (pin "3") (pinfunction "COM1_3") (pintype "passive"))
      (node (ref "DIS301") (pin "8") (pinfunction "COM1_8") (pintype "passive"))
      (node (ref "DIS401") (pin "3") (pinfunction "COM1_3") (pintype "passive"))
      (node (ref "DIS401") (pin "8") (pinfunction "COM1_8") (pintype "passive"))
      (node (ref "LED904") (pin "A") (pinfunction "A_A") (pintype "passive"))
      (node (ref "LED905") (pin "A") (pinfunction "A_A") (pintype "passive"))
      (node (ref "LED906") (pin "A") (pinfunction "A_A") (pintype "passive"))
      (node (ref "LED907") (pin "A") (pinfunction "A_A") (pintype "passive"))
      (node (ref "LED908") (pin "A") (pinfunction "A_A") (pintype "passive"))
      (node (ref "LED909") (pin "A") (pinfunction "A_A") (pintype "passive"))
      (node (ref "LED910") (pin "A") (pinfunction "A_A") (pintype "passive"))
      (node (ref "LED911") (pin "A") (pinfunction "A_A") (pintype "passive"))
      (node (ref "LED912") (pin "A") (pinfunction "A_A") (pintype "passive"))
      (node (ref "LED913") (pin "A") (pinfunction "A_A") (pintype "passive"))
      (node (ref "T1601") (pin "3") (pinfunction "D_3") (pintype "passive"))
    )
    (net (code "167") (name "DRV_ANODE_2") (class "Default")
      (node (ref "DIS501") (pin "3") (pinfunction "COM1_3") (pintype "passive"))
      (node (ref "DIS501") (pin "8") (pinfunction "COM1_8") (pintype "passive"))
      (node (ref "DIS601") (pin "3") (pinfunction "COM1_3") (pintype "passive"))
      (node (ref "DIS601") (pin "8") (pinfunction "COM1_8") (pintype "passive"))
      (node (ref "DIS701") (pin "3") (pinfunction "COM1_3") (pintype "passive"))
      (node (ref "DIS701") (pin "8") (pinfunction "COM1_8") (pintype "passive"))
      (node (ref "DIS801") (pin "3") (pinfunction "COM1_3") (pintype "passive"))
      (node (ref "DIS801") (pin "8") (pinfunction "COM1_8") (pintype "passive"))
      (node (ref "LED1401") (pin "A") (pinfunction "A_A") (pintype "passive"))
      (node (ref "T1602") (pin "3") (pinfunction "D_3") (pintype "passive"))
    )
    (net (code "168") (name "GND") (class "Default")
      (node (ref "C1001") (pin "1") (pinfunction "1_1") (pintype "passive"))
      (node (ref "C101") (pin "1") (pinfunction "1_1") (pintype "passive"))
      (node (ref "C1201") (pin "-") (pinfunction "-_-") (pintype "passive"))
      (node (ref "C1202") (pin "-") (pinfunction "-_-") (pintype "passive"))
      (node (ref "C1203") (pin "-") (pinfunction "-_-") (pintype "passive"))
      (node (ref "C1204") (pin "-") (pinfunction "-_-") (pintype "passive"))
      (node (ref "C1205") (pin "2") (pinfunction "2_2") (pintype "passive"))
      (node (ref "C1206") (pin "2") (pinfunction "2_2") (pintype "passive"))
      (node (ref "C1301") (pin "-") (pinfunction "-_-") (pintype "passive"))
      (node (ref "C1302") (pin "-") (pinfunction "-_-") (pintype "passive"))
      (node (ref "C1303") (pin "-") (pinfunction "-_-") (pintype "passive"))
      (node (ref "C1304") (pin "-") (pinfunction "-_-") (pintype "passive"))
      (node (ref "C1305") (pin "2") (pinfunction "2_2") (pintype "passive"))
      (node (ref "C1306") (pin "2") (pinfunction "2_2") (pintype "passive"))
      (node (ref "C1401") (pin "-") (pinfunction "-_-") (pintype "passive"))
      (node (ref "C1402") (pin "-") (pinfunction "-_-") (pintype "passive"))
      (node (ref "C1601") (pin "2") (pinfunction "2_2") (pintype "passive"))
      (node (ref "C1603") (pin "2") (pinfunction "2_2") (pintype "passive"))
      (node (ref "C1604") (pin "2") (pinfunction "2_2") (pintype "passive"))
      (node (ref "C201") (pin "1") (pinfunction "1_1") (pintype "passive"))
      (node (ref "C301") (pin "1") (pinfunction "1_1") (pintype "passive"))
      (node (ref "C401") (pin "1") (pinfunction "1_1") (pintype "passive"))
      (node (ref "C501") (pin "1") (pinfunction "1_1") (pintype "passive"))
      (node (ref "C601") (pin "1") (pinfunction "1_1") (pintype "passive"))
      (node (ref "C701") (pin "1") (pinfunction "1_1") (pintype "passive"))
      (node (ref "C801") (pin "1") (pinfunction "1_1") (pintype "passive"))
      (node (ref "C901") (pin "1") (pinfunction "1_1") (pintype "passive"))
      (node (ref "D1401") (pin "A") (pinfunction "A_A") (pintype "passive"))
      (node (ref "H1101") (pin "H1") (pinfunction "MOUNT_H1") (pintype "passive"))
      (node (ref "H1102") (pin "H1") (pinfunction "MOUNT_H1") (pintype "passive"))
      (node (ref "H1103") (pin "H1") (pinfunction "MOUNT_H1") (pintype "passive"))
      (node (ref "H1104") (pin "H1") (pinfunction "MOUNT_H1") (pintype "passive"))
      (node (ref "IC1001") (pin "2") (pinfunction "A1_2") (pintype "input"))
      (node (ref "IC1001") (pin "3") (pinfunction "A2_3") (pintype "input"))
      (node (ref "IC1001") (pin "8") (pinfunction "GND_8") (pintype "power_in"))
      (node (ref "IC101") (pin "1") (pinfunction "A0_1") (pintype "input"))
      (node (ref "IC101") (pin "2") (pinfunction "A1_2") (pintype "input"))
      (node (ref "IC101") (pin "3") (pinfunction "A2_3") (pintype "input"))
      (node (ref "IC101") (pin "8") (pinfunction "GND_8") (pintype "power_in"))
      (node (ref "IC1201") (pin "7") (pinfunction "GND_7") (pintype "power_in"))
      (node (ref "IC1202") (pin "7") (pinfunction "GND_7") (pintype "power_in"))
      (node (ref "IC1301") (pin "7") (pinfunction "GND_7") (pintype "power_in"))
      (node (ref "IC1302") (pin "7") (pinfunction "GND_7") (pintype "power_in"))
      (node (ref "IC1601") (pin "1") (pinfunction "GND_1") (pintype "power_in"))
      (node (ref "IC201") (pin "2") (pinfunction "A1_2") (pintype "input"))
      (node (ref "IC201") (pin "3") (pinfunction "A2_3") (pintype "input"))
      (node (ref "IC201") (pin "8") (pinfunction "GND_8") (pintype "power_in"))
      (node (ref "IC301") (pin "1") (pinfunction "A0_1") (pintype "input"))
      (node (ref "IC301") (pin "3") (pinfunction "A2_3") (pintype "input"))
      (node (ref "IC301") (pin "8") (pinfunction "GND_8") (pintype "power_in"))
      (node (ref "IC401") (pin "3") (pinfunction "A2_3") (pintype "input"))
      (node (ref "IC401") (pin "8") (pinfunction "GND_8") (pintype "power_in"))
      (node (ref "IC501") (pin "1") (pinfunction "A0_1") (pintype "input"))
      (node (ref "IC501") (pin "2") (pinfunction "A1_2") (pintype "input"))
      (node (ref "IC501") (pin "8") (pinfunction "GND_8") (pintype "power_in"))
      (node (ref "IC601") (pin "2") (pinfunction "A1_2") (pintype "input"))
      (node (ref "IC601") (pin "8") (pinfunction "GND_8") (pintype "power_in"))
      (node (ref "IC701") (pin "1") (pinfunction "A0_1") (pintype "input"))
      (node (ref "IC701") (pin "8") (pinfunction "GND_8") (pintype "power_in"))
      (node (ref "IC801") (pin "8") (pinfunction "GND_8") (pintype "power_in"))
      (node (ref "IC901") (pin "1") (pinfunction "A0_1") (pintype "input"))
      (node (ref "IC901") (pin "2") (pinfunction "A1_2") (pintype "input"))
      (node (ref "IC901") (pin "3") (pinfunction "A2_3") (pintype "input"))
      (node (ref "IC901") (pin "8") (pinfunction "GND_8") (pintype "power_in"))
      (node (ref "R1401") (pin "1") (pinfunction "1_1") (pintype "passive"))
      (node (ref "S1501") (pin "1") (pinfunction "A1_1") (pintype "passive"))
      (node (ref "S1501") (pin "3") (pinfunction "A1_3") (pintype "passive"))
      (node (ref "S1502") (pin "1") (pinfunction "A1_1") (pintype "passive"))
      (node (ref "S1502") (pin "3") (pinfunction "A1_3") (pintype "passive"))
      (node (ref "S1503") (pin "1") (pinfunction "A1_1") (pintype "passive"))
      (node (ref "S1503") (pin "3") (pinfunction "A1_3") (pintype "passive"))
      (node (ref "S1504") (pin "1") (pinfunction "A1_1") (pintype "passive"))
      (node (ref "S1504") (pin "3") (pinfunction "A1_3") (pintype "passive"))
      (node (ref "S1505") (pin "1") (pinfunction "A1_1") (pintype "passive"))
      (node (ref "S1505") (pin "3") (pinfunction "A1_3") (pintype "passive"))
      (node (ref "S1506") (pin "1") (pinfunction "A1_1") (pintype "passive"))
      (node (ref "S1506") (pin "3") (pinfunction "A1_3") (pintype "passive"))
      (node (ref "S1507") (pin "1") (pinfunction "A1_1") (pintype "passive"))
      (node (ref "S1507") (pin "3") (pinfunction "A1_3") (pintype "passive"))
      (node (ref "S1508") (pin "1") (pinfunction "A1_1") (pintype "passive"))
      (node (ref "S1508") (pin "3") (pinfunction "A1_3") (pintype "passive"))
      (node (ref "TP1603") (pin "1") (pinfunction "TP_1") (pintype "passive"))
      (node (ref "X1401") (pin "3") (pinfunction "3_3") (pintype "passive"))
      (node (ref "X1401") (pin "4") (pinfunction "4_4") (pintype "passive"))
      (node (ref "X1402") (pin "10") (pinfunction "10_10") (pintype "passive"))
      (node (ref "X1402") (pin "12") (pinfunction "12_12") (pintype "passive"))
      (node (ref "X1402") (pin "14") (pinfunction "14_14") (pintype "passive"))
      (node (ref "X1402") (pin "16") (pinfunction "16_16") (pintype "passive"))
      (node (ref "X1402") (pin "18") (pinfunction "18_18") (pintype "passive"))
      (node (ref "X1402") (pin "2") (pinfunction "2_2") (pintype "passive"))
      (node (ref "X1402") (pin "20") (pinfunction "20_20") (pintype "passive"))
      (node (ref "X1402") (pin "22") (pinfunction "22_22") (pintype "passive"))
      (node (ref "X1402") (pin "24") (pinfunction "24_24") (pintype "passive"))
      (node (ref "X1402") (pin "26") (pinfunction "26_26") (pintype "passive"))
      (node (ref "X1402") (pin "4") (pinfunction "4_4") (pintype "passive"))
      (node (ref "X1402") (pin "6") (pinfunction "6_6") (pintype "passive"))
      (node (ref "X1402") (pin "8") (pinfunction "8_8") (pintype "passive"))
      (node (ref "X1403") (pin "1") (pinfunction "1_1") (pintype "passive"))
      (node (ref "X1501") (pin "10") (pinfunction "10_10") (pintype "passive"))
      (node (ref "X1501") (pin "12") (pinfunction "12_12") (pintype "passive"))
      (node (ref "X1501") (pin "14") (pinfunction "14_14") (pintype "passive"))
      (node (ref "X1501") (pin "16") (pinfunction "16_16") (pintype "passive"))
      (node (ref "X1501") (pin "18") (pinfunction "18_18") (pintype "passive"))
      (node (ref "X1501") (pin "2") (pinfunction "2_2") (pintype "passive"))
      (node (ref "X1501") (pin "20") (pinfunction "20_20") (pintype "passive"))
      (node (ref "X1501") (pin "22") (pinfunction "22_22") (pintype "passive"))
      (node (ref "X1501") (pin "24") (pinfunction "24_24") (pintype "passive"))
      (node (ref "X1501") (pin "26") (pinfunction "26_26") (pintype "passive"))
      (node (ref "X1501") (pin "4") (pinfunction "4_4") (pintype "passive"))
      (node (ref "X1501") (pin "6") (pinfunction "6_6") (pintype "passive"))
      (node (ref "X1501") (pin "8") (pinfunction "8_8") (pintype "passive"))
    )
    (net (code "169") (name "IN_1#") (class "Default")
      (node (ref "RN1201") (pin "1") (pinfunction "1_1") (pintype "passive"))
      (node (ref "S1501") (pin "2") (pinfunction "B1_2") (pintype "passive"))
      (node (ref "S1501") (pin "4") (pinfunction "B1_4") (pintype "passive"))
      (node (ref "X1501") (pin "3") (pinfunction "3_3") (pintype "passive"))
    )
    (net (code "170") (name "IN_2#") (class "Default")
      (node (ref "RN1201") (pin "5") (pinfunction "1_5") (pintype "passive"))
      (node (ref "S1502") (pin "2") (pinfunction "B1_2") (pintype "passive"))
      (node (ref "S1502") (pin "4") (pinfunction "B1_4") (pintype "passive"))
      (node (ref "X1501") (pin "5") (pinfunction "5_5") (pintype "passive"))
    )
    (net (code "171") (name "IN_3#") (class "Default")
      (node (ref "RN1202") (pin "1") (pinfunction "1_1") (pintype "passive"))
      (node (ref "S1503") (pin "2") (pinfunction "B1_2") (pintype "passive"))
      (node (ref "S1503") (pin "4") (pinfunction "B1_4") (pintype "passive"))
      (node (ref "X1501") (pin "7") (pinfunction "7_7") (pintype "passive"))
    )
    (net (code "172") (name "IN_4#") (class "Default")
      (node (ref "RN1202") (pin "5") (pinfunction "1_5") (pintype "passive"))
      (node (ref "S1504") (pin "2") (pinfunction "B1_2") (pintype "passive"))
      (node (ref "S1504") (pin "4") (pinfunction "B1_4") (pintype "passive"))
      (node (ref "X1501") (pin "9") (pinfunction "9_9") (pintype "passive"))
    )
    (net (code "173") (name "IN_5#") (class "Default")
      (node (ref "RN1301") (pin "1") (pinfunction "1_1") (pintype "passive"))
      (node (ref "S1505") (pin "2") (pinfunction "B1_2") (pintype "passive"))
      (node (ref "S1505") (pin "4") (pinfunction "B1_4") (pintype "passive"))
      (node (ref "X1501") (pin "11") (pinfunction "11_11") (pintype "passive"))
    )
    (net (code "174") (name "IN_6#") (class "Default")
      (node (ref "RN1301") (pin "5") (pinfunction "1_5") (pintype "passive"))
      (node (ref "S1506") (pin "2") (pinfunction "B1_2") (pintype "passive"))
      (node (ref "S1506") (pin "4") (pinfunction "B1_4") (pintype "passive"))
      (node (ref "X1501") (pin "13") (pinfunction "13_13") (pintype "passive"))
    )
    (net (code "175") (name "IN_7#") (class "Default")
      (node (ref "RN1302") (pin "1") (pinfunction "1_1") (pintype "passive"))
      (node (ref "S1507") (pin "2") (pinfunction "B1_2") (pintype "passive"))
      (node (ref "S1507") (pin "4") (pinfunction "B1_4") (pintype "passive"))
      (node (ref "X1501") (pin "15") (pinfunction "15_15") (pintype "passive"))
    )
    (net (code "176") (name "IN_8#") (class "Default")
      (node (ref "RN1302") (pin "5") (pinfunction "1_5") (pintype "passive"))
      (node (ref "S1508") (pin "2") (pinfunction "B1_2") (pintype "passive"))
      (node (ref "S1508") (pin "4") (pinfunction "B1_4") (pintype "passive"))
      (node (ref "X1501") (pin "17") (pinfunction "17_17") (pintype "passive"))
    )
    (net (code "177") (name "KEYPAD_1_K_1") (class "Default")
      (node (ref "IC1001") (pin "4") (pinfunction "P0_4") (pintype "bidirectional"))
      (node (ref "RN1001") (pin "1") (pinfunction "1_1") (pintype "passive"))
    )
    (net (code "178") (name "KEYPAD_1_K_2") (class "Default")
      (node (ref "IC1001") (pin "5") (pinfunction "P1_5") (pintype "bidirectional"))
      (node (ref "RN1001") (pin "3") (pinfunction "1_3") (pintype "passive"))
    )
    (net (code "179") (name "KEYPAD_1_K_3") (class "Default")
      (node (ref "IC1001") (pin "6") (pinfunction "P2_6") (pintype "bidirectional"))
      (node (ref "RN1001") (pin "5") (pinfunction "1_5") (pintype "passive"))
    )
    (net (code "180") (name "KEYPAD_1_K_4") (class "Default")
      (node (ref "IC1001") (pin "7") (pinfunction "P3_7") (pintype "bidirectional"))
      (node (ref "RN1001") (pin "7") (pinfunction "1_7") (pintype "passive"))
    )
    (net (code "181") (name "KEYPAD_1_K_5") (class "Default")
      (node (ref "IC1001") (pin "9") (pinfunction "P4_9") (pintype "bidirectional"))
      (node (ref "RN1002") (pin "1") (pinfunction "1_1") (pintype "passive"))
    )
    (net (code "182") (name "KEYPAD_1_K_6") (class "Default")
      (node (ref "IC1001") (pin "10") (pinfunction "P5_10") (pintype "bidirectional"))
      (node (ref "RN1002") (pin "3") (pinfunction "1_3") (pintype "passive"))
    )
    (net (code "183") (name "KEYPAD_1_K_7") (class "Default")
      (node (ref "IC1001") (pin "11") (pinfunction "P6_11") (pintype "bidirectional"))
      (node (ref "RN1002") (pin "5") (pinfunction "1_5") (pintype "passive"))
    )
    (net (code "184") (name "KEYPAD_1_K_8") (class "Default")
      (node (ref "IC1001") (pin "12") (pinfunction "P7_12") (pintype "bidirectional"))
      (node (ref "RN1002") (pin "7") (pinfunction "1_7") (pintype "passive"))
    )
    (net (code "185") (name "Net-(C1602-Pad2)") (class "Default")
      (node (ref "C1602") (pin "2") (pinfunction "2_2") (pintype "passive"))
      (node (ref "C1603") (pin "1") (pinfunction "1_1") (pintype "passive"))
    )
    (net (code "186") (name "Net-(IC1201A-I0)") (class "Default")
      (node (ref "IC1201") (pin "1") (pinfunction "I0_1") (pintype "input"))
      (node (ref "IC1201") (pin "2") (pinfunction "I1_2") (pintype "input"))
      (node (ref "RN1201") (pin "4") (pinfunction "2_4") (pintype "passive"))
      (node (ref "RN1203") (pin "3") (pinfunction "1_3") (pintype "passive"))
    )
    (net (code "187") (name "Net-(IC1201A-O)") (class "Default")
      (node (ref "IC1201") (pin "3") (pinfunction "O_3") (pintype "output"))
      (node (ref "IC1201") (pin "4") (pinfunction "I0_4") (pintype "input"))
      (node (ref "IC1201") (pin "5") (pinfunction "I1_5") (pintype "input"))
    )
    (net (code "188") (name "Net-(IC1201C-I0)") (class "Default")
      (node (ref "IC1201") (pin "10") (pinfunction "I0_10") (pintype "input"))
      (node (ref "IC1201") (pin "11") (pinfunction "O_11") (pintype "output"))
      (node (ref "IC1201") (pin "9") (pinfunction "I1_9") (pintype "input"))
    )
    (net (code "189") (name "Net-(IC1201D-I0)") (class "Default")
      (node (ref "IC1201") (pin "12") (pinfunction "I1_12") (pintype "input"))
      (node (ref "IC1201") (pin "13") (pinfunction "I0_13") (pintype "input"))
      (node (ref "RN1201") (pin "8") (pinfunction "2_8") (pintype "passive"))
      (node (ref "RN1203") (pin "1") (pinfunction "1_1") (pintype "passive"))
    )
    (net (code "190") (name "Net-(IC1202A-I0)") (class "Default")
      (node (ref "IC1202") (pin "1") (pinfunction "I0_1") (pintype "input"))
      (node (ref "IC1202") (pin "2") (pinfunction "I1_2") (pintype "input"))
      (node (ref "RN1202") (pin "4") (pinfunction "2_4") (pintype "passive"))
      (node (ref "RN1203") (pin "5") (pinfunction "1_5") (pintype "passive"))
    )
    (net (code "191") (name "Net-(IC1202A-O)") (class "Default")
      (node (ref "IC1202") (pin "3") (pinfunction "O_3") (pintype "output"))
      (node (ref "IC1202") (pin "4") (pinfunction "I0_4") (pintype "input"))
      (node (ref "IC1202") (pin "5") (pinfunction "I1_5") (pintype "input"))
    )
    (net (code "192") (name "Net-(IC1202C-I0)") (class "Default")
      (node (ref "IC1202") (pin "10") (pinfunction "I0_10") (pintype "input"))
      (node (ref "IC1202") (pin "11") (pinfunction "O_11") (pintype "output"))
      (node (ref "IC1202") (pin "9") (pinfunction "I1_9") (pintype "input"))
    )
    (net (code "193") (name "Net-(IC1202D-I0)") (class "Default")
      (node (ref "IC1202") (pin "12") (pinfunction "I1_12") (pintype "input"))
      (node (ref "IC1202") (pin "13") (pinfunction "I0_13") (pintype "input"))
      (node (ref "RN1202") (pin "8") (pinfunction "2_8") (pintype "passive"))
      (node (ref "RN1203") (pin "7") (pinfunction "1_7") (pintype "passive"))
    )
    (net (code "194") (name "Net-(IC1301A-I0)") (class "Default")
      (node (ref "IC1301") (pin "1") (pinfunction "I0_1") (pintype "input"))
      (node (ref "IC1301") (pin "2") (pinfunction "I1_2") (pintype "input"))
      (node (ref "RN1301") (pin "4") (pinfunction "2_4") (pintype "passive"))
      (node (ref "RN1303") (pin "3") (pinfunction "1_3") (pintype "passive"))
    )
    (net (code "195") (name "Net-(IC1301A-O)") (class "Default")
      (node (ref "IC1301") (pin "3") (pinfunction "O_3") (pintype "output"))
      (node (ref "IC1301") (pin "4") (pinfunction "I0_4") (pintype "input"))
      (node (ref "IC1301") (pin "5") (pinfunction "I1_5") (pintype "input"))
    )
    (net (code "196") (name "Net-(IC1301C-I0)") (class "Default")
      (node (ref "IC1301") (pin "10") (pinfunction "I0_10") (pintype "input"))
      (node (ref "IC1301") (pin "11") (pinfunction "O_11") (pintype "output"))
      (node (ref "IC1301") (pin "9") (pinfunction "I1_9") (pintype "input"))
    )
    (net (code "197") (name "Net-(IC1301D-I0)") (class "Default")
      (node (ref "IC1301") (pin "12") (pinfunction "I1_12") (pintype "input"))
      (node (ref "IC1301") (pin "13") (pinfunction "I0_13") (pintype "input"))
      (node (ref "RN1301") (pin "8") (pinfunction "2_8") (pintype "passive"))
      (node (ref "RN1303") (pin "1") (pinfunction "1_1") (pintype "passive"))
    )
    (net (code "198") (name "Net-(IC1302A-I0)") (class "Default")
      (node (ref "IC1302") (pin "1") (pinfunction "I0_1") (pintype "input"))
      (node (ref "IC1302") (pin "2") (pinfunction "I1_2") (pintype "input"))
      (node (ref "RN1302") (pin "4") (pinfunction "2_4") (pintype "passive"))
      (node (ref "RN1303") (pin "5") (pinfunction "1_5") (pintype "passive"))
    )
    (net (code "199") (name "Net-(IC1302A-O)") (class "Default")
      (node (ref "IC1302") (pin "3") (pinfunction "O_3") (pintype "output"))
      (node (ref "IC1302") (pin "4") (pinfunction "I0_4") (pintype "input"))
      (node (ref "IC1302") (pin "5") (pinfunction "I1_5") (pintype "input"))
    )
    (net (code "200") (name "Net-(IC1302C-I0)") (class "Default")
      (node (ref "IC1302") (pin "10") (pinfunction "I0_10") (pintype "input"))
      (node (ref "IC1302") (pin "11") (pinfunction "O_11") (pintype "output"))
      (node (ref "IC1302") (pin "9") (pinfunction "I1_9") (pintype "input"))
    )
    (net (code "201") (name "Net-(IC1302D-I0)") (class "Default")
      (node (ref "IC1302") (pin "12") (pinfunction "I1_12") (pintype "input"))
      (node (ref "IC1302") (pin "13") (pinfunction "I0_13") (pintype "input"))
      (node (ref "RN1302") (pin "8") (pinfunction "2_8") (pintype "passive"))
      (node (ref "RN1303") (pin "7") (pinfunction "1_7") (pintype "passive"))
    )
    (net (code "202") (name "Net-(IC1601-DSCHRG)") (class "Default")
      (node (ref "D1601") (pin "A") (pinfunction "A_A") (pintype "passive"))
      (node (ref "IC1601") (pin "7") (pinfunction "DSCHRG_7") (pintype "output"))
      (node (ref "R1601") (pin "2") (pinfunction "2_2") (pintype "passive"))
      (node (ref "R1602") (pin "1") (pinfunction "1_1") (pintype "passive"))
      (node (ref "TP1606") (pin "1") (pinfunction "TP_1") (pintype "passive"))
    )
    (net (code "203") (name "Net-(IC1601-OC)") (class "Default")
      (node (ref "C1604") (pin "1") (pinfunction "1_1") (pintype "passive"))
      (node (ref "IC1601") (pin "4") (pinfunction "RST#_4") (pintype "input"))
      (node (ref "IC1601") (pin "5") (pinfunction "OC_5") (pintype "passive"))
      (node (ref "TP1604") (pin "1") (pinfunction "TP_1") (pintype "passive"))
    )
    (net (code "204") (name "Net-(IC1601-TRG)") (class "Default")
      (node (ref "C1602") (pin "1") (pinfunction "1_1") (pintype "passive"))
      (node (ref "D1601") (pin "C") (pinfunction "C_C") (pintype "passive"))
      (node (ref "IC1601") (pin "2") (pinfunction "TRG_2") (pintype "passive"))
      (node (ref "IC1601") (pin "6") (pinfunction "TRSHLD_6") (pintype "passive"))
      (node (ref "R1601") (pin "1") (pinfunction "1_1") (pintype "passive"))
      (node (ref "TP1601") (pin "1") (pinfunction "TP_1") (pintype "passive"))
    )
    (net (code "205") (name "Net-(LED901-PadA)") (class "Default")
      (node (ref "LED901") (pin "A") (pinfunction "A_A") (pintype "passive"))
      (node (ref "LED911") (pin "C") (pinfunction "C_C") (pintype "passive"))
    )
    (net (code "206") (name "Net-(LED902-PadA)") (class "Default")
      (node (ref "LED902") (pin "A") (pinfunction "A_A") (pintype "passive"))
      (node (ref "LED912") (pin "C") (pinfunction "C_C") (pintype "passive"))
    )
    (net (code "207") (name "Net-(LED903-PadA)") (class "Default")
      (node (ref "LED903") (pin "A") (pinfunction "A_A") (pintype "passive"))
      (node (ref "LED913") (pin "C") (pinfunction "C_C") (pintype "passive"))
    )
    (net (code "208") (name "Net-(LED1401-PadC)") (class "Default")
      (node (ref "LED1401") (pin "C") (pinfunction "C_C") (pintype "passive"))
      (node (ref "R1401") (pin "2") (pinfunction "2_2") (pintype "passive"))
    )
    (net (code "209") (name "Net-(RN1201B-1)") (class "Default")
      (node (ref "C1201") (pin "+") (pinfunction "+_+") (pintype "passive"))
      (node (ref "RN1201") (pin "2") (pinfunction "2_2") (pintype "passive"))
      (node (ref "RN1201") (pin "3") (pinfunction "1_3") (pintype "passive"))
    )
    (net (code "210") (name "Net-(RN1201C-2)") (class "Default")
      (node (ref "C1202") (pin "+") (pinfunction "+_+") (pintype "passive"))
      (node (ref "RN1201") (pin "6") (pinfunction "2_6") (pintype "passive"))
      (node (ref "RN1201") (pin "7") (pinfunction "1_7") (pintype "passive"))
    )
    (net (code "211") (name "Net-(RN1202B-1)") (class "Default")
      (node (ref "C1203") (pin "+") (pinfunction "+_+") (pintype "passive"))
      (node (ref "RN1202") (pin "2") (pinfunction "2_2") (pintype "passive"))
      (node (ref "RN1202") (pin "3") (pinfunction "1_3") (pintype "passive"))
    )
    (net (code "212") (name "Net-(RN1202C-2)") (class "Default")
      (node (ref "C1204") (pin "+") (pinfunction "+_+") (pintype "passive"))
      (node (ref "RN1202") (pin "6") (pinfunction "2_6") (pintype "passive"))
      (node (ref "RN1202") (pin "7") (pinfunction "1_7") (pintype "passive"))
    )
    (net (code "213") (name "Net-(RN1301B-1)") (class "Default")
      (node (ref "C1301") (pin "+") (pinfunction "+_+") (pintype "passive"))
      (node (ref "RN1301") (pin "2") (pinfunction "2_2") (pintype "passive"))
      (node (ref "RN1301") (pin "3") (pinfunction "1_3") (pintype "passive"))
    )
    (net (code "214") (name "Net-(RN1301C-2)") (class "Default")
      (node (ref "C1302") (pin "+") (pinfunction "+_+") (pintype "passive"))
      (node (ref "RN1301") (pin "6") (pinfunction "2_6") (pintype "passive"))
      (node (ref "RN1301") (pin "7") (pinfunction "1_7") (pintype "passive"))
    )
    (net (code "215") (name "Net-(RN1302B-1)") (class "Default")
      (node (ref "C1303") (pin "+") (pinfunction "+_+") (pintype "passive"))
      (node (ref "RN1302") (pin "2") (pinfunction "2_2") (pintype "passive"))
      (node (ref "RN1302") (pin "3") (pinfunction "1_3") (pintype "passive"))
    )
    (net (code "216") (name "Net-(RN1302C-2)") (class "Default")
      (node (ref "C1304") (pin "+") (pinfunction "+_+") (pintype "passive"))
      (node (ref "RN1302") (pin "6") (pinfunction "2_6") (pintype "passive"))
      (node (ref "RN1302") (pin "7") (pinfunction "1_7") (pintype "passive"))
    )
    (net (code "217") (name "P5V") (class "Default")
      (node (ref "C1001") (pin "2") (pinfunction "2_2") (pintype "passive"))
      (node (ref "C101") (pin "2") (pinfunction "2_2") (pintype "passive"))
      (node (ref "C1205") (pin "1") (pinfunction "1_1") (pintype "passive"))
      (node (ref "C1206") (pin "1") (pinfunction "1_1") (pintype "passive"))
      (node (ref "C1305") (pin "1") (pinfunction "1_1") (pintype "passive"))
      (node (ref "C1306") (pin "1") (pinfunction "1_1") (pintype "passive"))
      (node (ref "C1401") (pin "+") (pinfunction "+_+") (pintype "passive"))
      (node (ref "C1402") (pin "+") (pinfunction "+_+") (pintype "passive"))
      (node (ref "C1601") (pin "1") (pinfunction "1_1") (pintype "passive"))
      (node (ref "C201") (pin "2") (pinfunction "2_2") (pintype "passive"))
      (node (ref "C301") (pin "2") (pinfunction "2_2") (pintype "passive"))
      (node (ref "C401") (pin "2") (pinfunction "2_2") (pintype "passive"))
      (node (ref "C501") (pin "2") (pinfunction "2_2") (pintype "passive"))
      (node (ref "C601") (pin "2") (pinfunction "2_2") (pintype "passive"))
      (node (ref "C701") (pin "2") (pinfunction "2_2") (pintype "passive"))
      (node (ref "C801") (pin "2") (pinfunction "2_2") (pintype "passive"))
      (node (ref "C901") (pin "2") (pinfunction "2_2") (pintype "passive"))
      (node (ref "D1401") (pin "C") (pinfunction "C_C") (pintype "passive"))
      (node (ref "IC1001") (pin "1") (pinfunction "A0_1") (pintype "input"))
      (node (ref "IC1001") (pin "16") (pinfunction "VDD_16") (pintype "power_in"))
      (node (ref "IC101") (pin "16") (pinfunction "VDD_16") (pintype "power_in"))
      (node (ref "IC1201") (pin "14") (pinfunction "VCC_14") (pintype "power_in"))
      (node (ref "IC1202") (pin "14") (pinfunction "VCC_14") (pintype "power_in"))
      (node (ref "IC1301") (pin "14") (pinfunction "VCC_14") (pintype "power_in"))
      (node (ref "IC1302") (pin "14") (pinfunction "VCC_14") (pintype "power_in"))
      (node (ref "IC1601") (pin "8") (pinfunction "VCC_8") (pintype "power_in"))
      (node (ref "IC201") (pin "1") (pinfunction "A0_1") (pintype "input"))
      (node (ref "IC201") (pin "16") (pinfunction "VDD_16") (pintype "power_in"))
      (node (ref "IC301") (pin "16") (pinfunction "VDD_16") (pintype "power_in"))
      (node (ref "IC301") (pin "2") (pinfunction "A1_2") (pintype "input"))
      (node (ref "IC401") (pin "1") (pinfunction "A0_1") (pintype "input"))
      (node (ref "IC401") (pin "16") (pinfunction "VDD_16") (pintype "power_in"))
      (node (ref "IC401") (pin "2") (pinfunction "A1_2") (pintype "input"))
      (node (ref "IC501") (pin "16") (pinfunction "VDD_16") (pintype "power_in"))
      (node (ref "IC501") (pin "3") (pinfunction "A2_3") (pintype "input"))
      (node (ref "IC601") (pin "1") (pinfunction "A0_1") (pintype "input"))
      (node (ref "IC601") (pin "16") (pinfunction "VDD_16") (pintype "power_in"))
      (node (ref "IC601") (pin "3") (pinfunction "A2_3") (pintype "input"))
      (node (ref "IC701") (pin "16") (pinfunction "VDD_16") (pintype "power_in"))
      (node (ref "IC701") (pin "2") (pinfunction "A1_2") (pintype "input"))
      (node (ref "IC701") (pin "3") (pinfunction "A2_3") (pintype "input"))
      (node (ref "IC801") (pin "1") (pinfunction "A0_1") (pintype "input"))
      (node (ref "IC801") (pin "16") (pinfunction "VDD_16") (pintype "power_in"))
      (node (ref "IC801") (pin "2") (pinfunction "A1_2") (pintype "input"))
      (node (ref "IC801") (pin "3") (pinfunction "A2_3") (pintype "input"))
      (node (ref "IC901") (pin "16") (pinfunction "VDD_16") (pintype "power_in"))
      (node (ref "R1602") (pin "2") (pinfunction "2_2") (pintype "passive"))
      (node (ref "R1603") (pin "2") (pinfunction "2_2") (pintype "passive"))
      (node (ref "RN1401") (pin "1") (pinfunction "1_1") (pintype "passive"))
      (node (ref "RN1402") (pin "1") (pinfunction "1_1") (pintype "passive"))
      (node (ref "T1601") (pin "2") (pinfunction "S_2") (pintype "passive"))
      (node (ref "T1602") (pin "2") (pinfunction "S_2") (pintype "passive"))
      (node (ref "TP1602") (pin "1") (pinfunction "TP_1") (pintype "passive"))
      (node (ref "TP1605") (pin "1") (pinfunction "TP_1") (pintype "passive"))
      (node (ref "X1401") (pin "1") (pinfunction "1_1") (pintype "passive"))
      (node (ref "X1401") (pin "2") (pinfunction "2_2") (pintype "passive"))
      (node (ref "X1403") (pin "3") (pinfunction "3_3") (pintype "passive"))
    )
    (net (code "218") (name "TIM_OUT") (class "Default")
      (node (ref "IC1601") (pin "3") (pinfunction "OUT_3") (pintype "output"))
      (node (ref "R1603") (pin "1") (pinfunction "1_1") (pintype "passive"))
      (node (ref "T1601") (pin "1") (pinfunction "G_1") (pintype "passive"))
      (node (ref "T1602") (pin "1") (pinfunction "G_1") (pintype "passive"))
      (node (ref "TP1607") (pin "1") (pinfunction "TP_1") (pintype "passive"))
    )
    (net (code "219") (name "unconnected-(FD1101-NC-Pad1)") (class "Default")
      (node (ref "FD1101") (pin "1") (pinfunction "NC_1") (pintype "no_connect"))
    )
    (net (code "220") (name "unconnected-(FD1102-NC-Pad1)") (class "Default")
      (node (ref "FD1102") (pin "1") (pinfunction "NC_1") (pintype "no_connect"))
    )
    (net (code "221") (name "unconnected-(IC101-~{INT}-Pad13)") (class "Default")
      (node (ref "IC101") (pin "13") (pinfunction "~{INT}_13") (pintype "output"))
    )
    (net (code "222") (name "unconnected-(IC201-~{INT}-Pad13)") (class "Default")
      (node (ref "IC201") (pin "13") (pinfunction "~{INT}_13") (pintype "output"))
    )
    (net (code "223") (name "unconnected-(IC301-~{INT}-Pad13)") (class "Default")
      (node (ref "IC301") (pin "13") (pinfunction "~{INT}_13") (pintype "output"))
    )
    (net (code "224") (name "unconnected-(IC401-~{INT}-Pad13)") (class "Default")
      (node (ref "IC401") (pin "13") (pinfunction "~{INT}_13") (pintype "output"))
    )
    (net (code "225") (name "unconnected-(IC501-~{INT}-Pad13)") (class "Default")
      (node (ref "IC501") (pin "13") (pinfunction "~{INT}_13") (pintype "output"))
    )
    (net (code "226") (name "unconnected-(IC601-~{INT}-Pad13)") (class "Default")
      (node (ref "IC601") (pin "13") (pinfunction "~{INT}_13") (pintype "output"))
    )
    (net (code "227") (name "unconnected-(IC701-~{INT}-Pad13)") (class "Default")
      (node (ref "IC701") (pin "13") (pinfunction "~{INT}_13") (pintype "output"))
    )
    (net (code "228") (name "unconnected-(IC801-~{INT}-Pad13)") (class "Default")
      (node (ref "IC801") (pin "13") (pinfunction "~{INT}_13") (pintype "output"))
    )
    (net (code "229") (name "unconnected-(IC901-~{INT}-Pad13)") (class "Default")
      (node (ref "IC901") (pin "13") (pinfunction "~{INT}_13") (pintype "output"))
    )
    (net (code "230") (name "unconnected-(IC1001-~{INT}-Pad13)") (class "Default")
      (node (ref "IC1001") (pin "13") (pinfunction "~{INT}_13") (pintype "output"))
    )
    (net (code "231") (name "unconnected-(RN1402-Pad5)") (class "Default")
      (node (ref "RN1402") (pin "5") (pinfunction "5_5") (pintype "passive"))
    )
    (net (code "232") (name "unconnected-(RN1402-Pad6)") (class "Default")
      (node (ref "RN1402") (pin "6") (pinfunction "6_6") (pintype "passive"))
    )
    (net (code "233") (name "unconnected-(RN1402-Pad7)") (class "Default")
      (node (ref "RN1402") (pin "7") (pinfunction "7_7") (pintype "passive"))
    )
    (net (code "234") (name "unconnected-(RN1402-Pad8)") (class "Default")
      (node (ref "RN1402") (pin "8") (pinfunction "8_8") (pintype "passive"))
    )
    (net (code "235") (name "unconnected-(RN1402-Pad9)") (class "Default")
      (node (ref "RN1402") (pin "9") (pinfunction "9_9") (pintype "passive"))
    )
    (net (code "236") (name "unconnected-(TP1101-TP-Pad1)") (class "Default")
      (node (ref "TP1101") (pin "1") (pinfunction "TP_1") (pintype "passive"))
    )
    (net (code "237") (name "unconnected-(TP1102-TP-Pad1)") (class "Default")
      (node (ref "TP1102") (pin "1") (pinfunction "TP_1") (pintype "passive"))
    )
    (net (code "238") (name "unconnected-(TP1103-TP-Pad1)") (class "Default")
      (node (ref "TP1103") (pin "1") (pinfunction "TP_1") (pintype "passive"))
    )
    (net (code "239") (name "unconnected-(TP1104-TP-Pad1)") (class "Default")
      (node (ref "TP1104") (pin "1") (pinfunction "TP_1") (pintype "passive"))
    )
    (net (code "240") (name "unconnected-(TP1105-TP-Pad1)") (class "Default")
      (node (ref "TP1105") (pin "1") (pinfunction "TP_1") (pintype "passive"))
    )
    (net (code "241") (name "unconnected-(TP1106-TP-Pad1)") (class "Default")
      (node (ref "TP1106") (pin "1") (pinfunction "TP_1") (pintype "passive"))
    )
    (net (code "242") (name "unconnected-(TP1107-TP-Pad1)") (class "Default")
      (node (ref "TP1107") (pin "1") (pinfunction "TP_1") (pintype "passive"))
    )
    (net (code "243") (name "unconnected-(TP1108-TP-Pad1)") (class "Default")
      (node (ref "TP1108") (pin "1") (pinfunction "TP_1") (pintype "passive"))
    )
    (net (code "244") (name "unconnected-(TP1109-TP-Pad1)") (class "Default")
      (node (ref "TP1109") (pin "1") (pinfunction "TP_1") (pintype "passive"))
    )
    (net (code "245") (name "unconnected-(TP1110-TP-Pad1)") (class "Default")
      (node (ref "TP1110") (pin "1") (pinfunction "TP_1") (pintype "passive"))
    )
    (net (code "246") (name "unconnected-(TP1111-TP-Pad1)") (class "Default")
      (node (ref "TP1111") (pin "1") (pinfunction "TP_1") (pintype "passive"))
    )
    (net (code "247") (name "unconnected-(TP1112-TP-Pad1)") (class "Default")
      (node (ref "TP1112") (pin "1") (pinfunction "TP_1") (pintype "passive"))
    )
    (net (code "248") (name "unconnected-(TP1113-TP-Pad1)") (class "Default")
      (node (ref "TP1113") (pin "1") (pinfunction "TP_1") (pintype "passive"))
    )
    (net (code "249") (name "unconnected-(TP1114-TP-Pad1)") (class "Default")
      (node (ref "TP1114") (pin "1") (pinfunction "TP_1") (pintype "passive"))
    )
    (net (code "250") (name "unconnected-(TP1115-TP-Pad1)") (class "Default")
      (node (ref "TP1115") (pin "1") (pinfunction "TP_1") (pintype "passive"))
    )
    (net (code "251") (name "unconnected-(TP1116-TP-Pad1)") (class "Default")
      (node (ref "TP1116") (pin "1") (pinfunction "TP_1") (pintype "passive"))
    )
    (net (code "252") (name "unconnected-(TP1117-TP-Pad1)") (class "Default")
      (node (ref "TP1117") (pin "1") (pinfunction "TP_1") (pintype "passive"))
    )
    (net (code "253") (name "unconnected-(TP1118-TP-Pad1)") (class "Default")
      (node (ref "TP1118") (pin "1") (pinfunction "TP_1") (pintype "passive"))
    )
    (net (code "254") (name "unconnected-(TP1119-TP-Pad1)") (class "Default")
      (node (ref "TP1119") (pin "1") (pinfunction "TP_1") (pintype "passive"))
    )
    (net (code "255") (name "unconnected-(TP1120-TP-Pad1)") (class "Default")
      (node (ref "TP1120") (pin "1") (pinfunction "TP_1") (pintype "passive"))
    )
    (net (code "256") (name "unconnected-(TP1121-TP-Pad1)") (class "Default")
      (node (ref "TP1121") (pin "1") (pinfunction "TP_1") (pintype "passive"))
    )
    (net (code "257") (name "unconnected-(TP1122-TP-Pad1)") (class "Default")
      (node (ref "TP1122") (pin "1") (pinfunction "TP_1") (pintype "passive"))
    )
    (net (code "258") (name "unconnected-(TP1123-TP-Pad1)") (class "Default")
      (node (ref "TP1123") (pin "1") (pinfunction "TP_1") (pintype "passive"))
    )
    (net (code "259") (name "unconnected-(TP1124-TP-Pad1)") (class "Default")
      (node (ref "TP1124") (pin "1") (pinfunction "TP_1") (pintype "passive"))
    )
    (net (code "260") (name "unconnected-(TP1125-TP-Pad1)") (class "Default")
      (node (ref "TP1125") (pin "1") (pinfunction "TP_1") (pintype "passive"))
    )
    (net (code "261") (name "unconnected-(TP1126-TP-Pad1)") (class "Default")
      (node (ref "TP1126") (pin "1") (pinfunction "TP_1") (pintype "passive"))
    )
    (net (code "262") (name "unconnected-(TP1127-TP-Pad1)") (class "Default")
      (node (ref "TP1127") (pin "1") (pinfunction "TP_1") (pintype "passive"))
    )
    (net (code "263") (name "unconnected-(X1402-Pad23)") (class "Default")
      (node (ref "X1402") (pin "23") (pinfunction "23_23") (pintype "passive"))
    )
    (net (code "264") (name "unconnected-(X1402-Pad25)") (class "Default")
      (node (ref "X1402") (pin "25") (pinfunction "25_25") (pintype "passive"))
    )
    (net (code "265") (name "unconnected-(X1403-Pad2)") (class "Default")
      (node (ref "X1403") (pin "2") (pinfunction "2_2") (pintype "passive"))
    )
    (net (code "266") (name "unconnected-(X1501-Pad1)") (class "Default")
      (node (ref "X1501") (pin "1") (pinfunction "1_1") (pintype "passive"))
    )
    (net (code "267") (name "unconnected-(X1501-Pad19)") (class "Default")
      (node (ref "X1501") (pin "19") (pinfunction "19_19") (pintype "passive"))
    )
    (net (code "268") (name "unconnected-(X1501-Pad21)") (class "Default")
      (node (ref "X1501") (pin "21") (pinfunction "21_21") (pintype "passive"))
    )
    (net (code "269") (name "unconnected-(X1501-Pad23)") (class "Default")
      (node (ref "X1501") (pin "23") (pinfunction "23_23") (pintype "passive"))
    )
    (net (code "270") (name "unconnected-(X1501-Pad25)") (class "Default")
      (node (ref "X1501") (pin "25") (pinfunction "25_25") (pintype "passive"))
    )
  )
)
